# 10125623A00.net
KiCad netlist of a schematic drawn in EAGLE
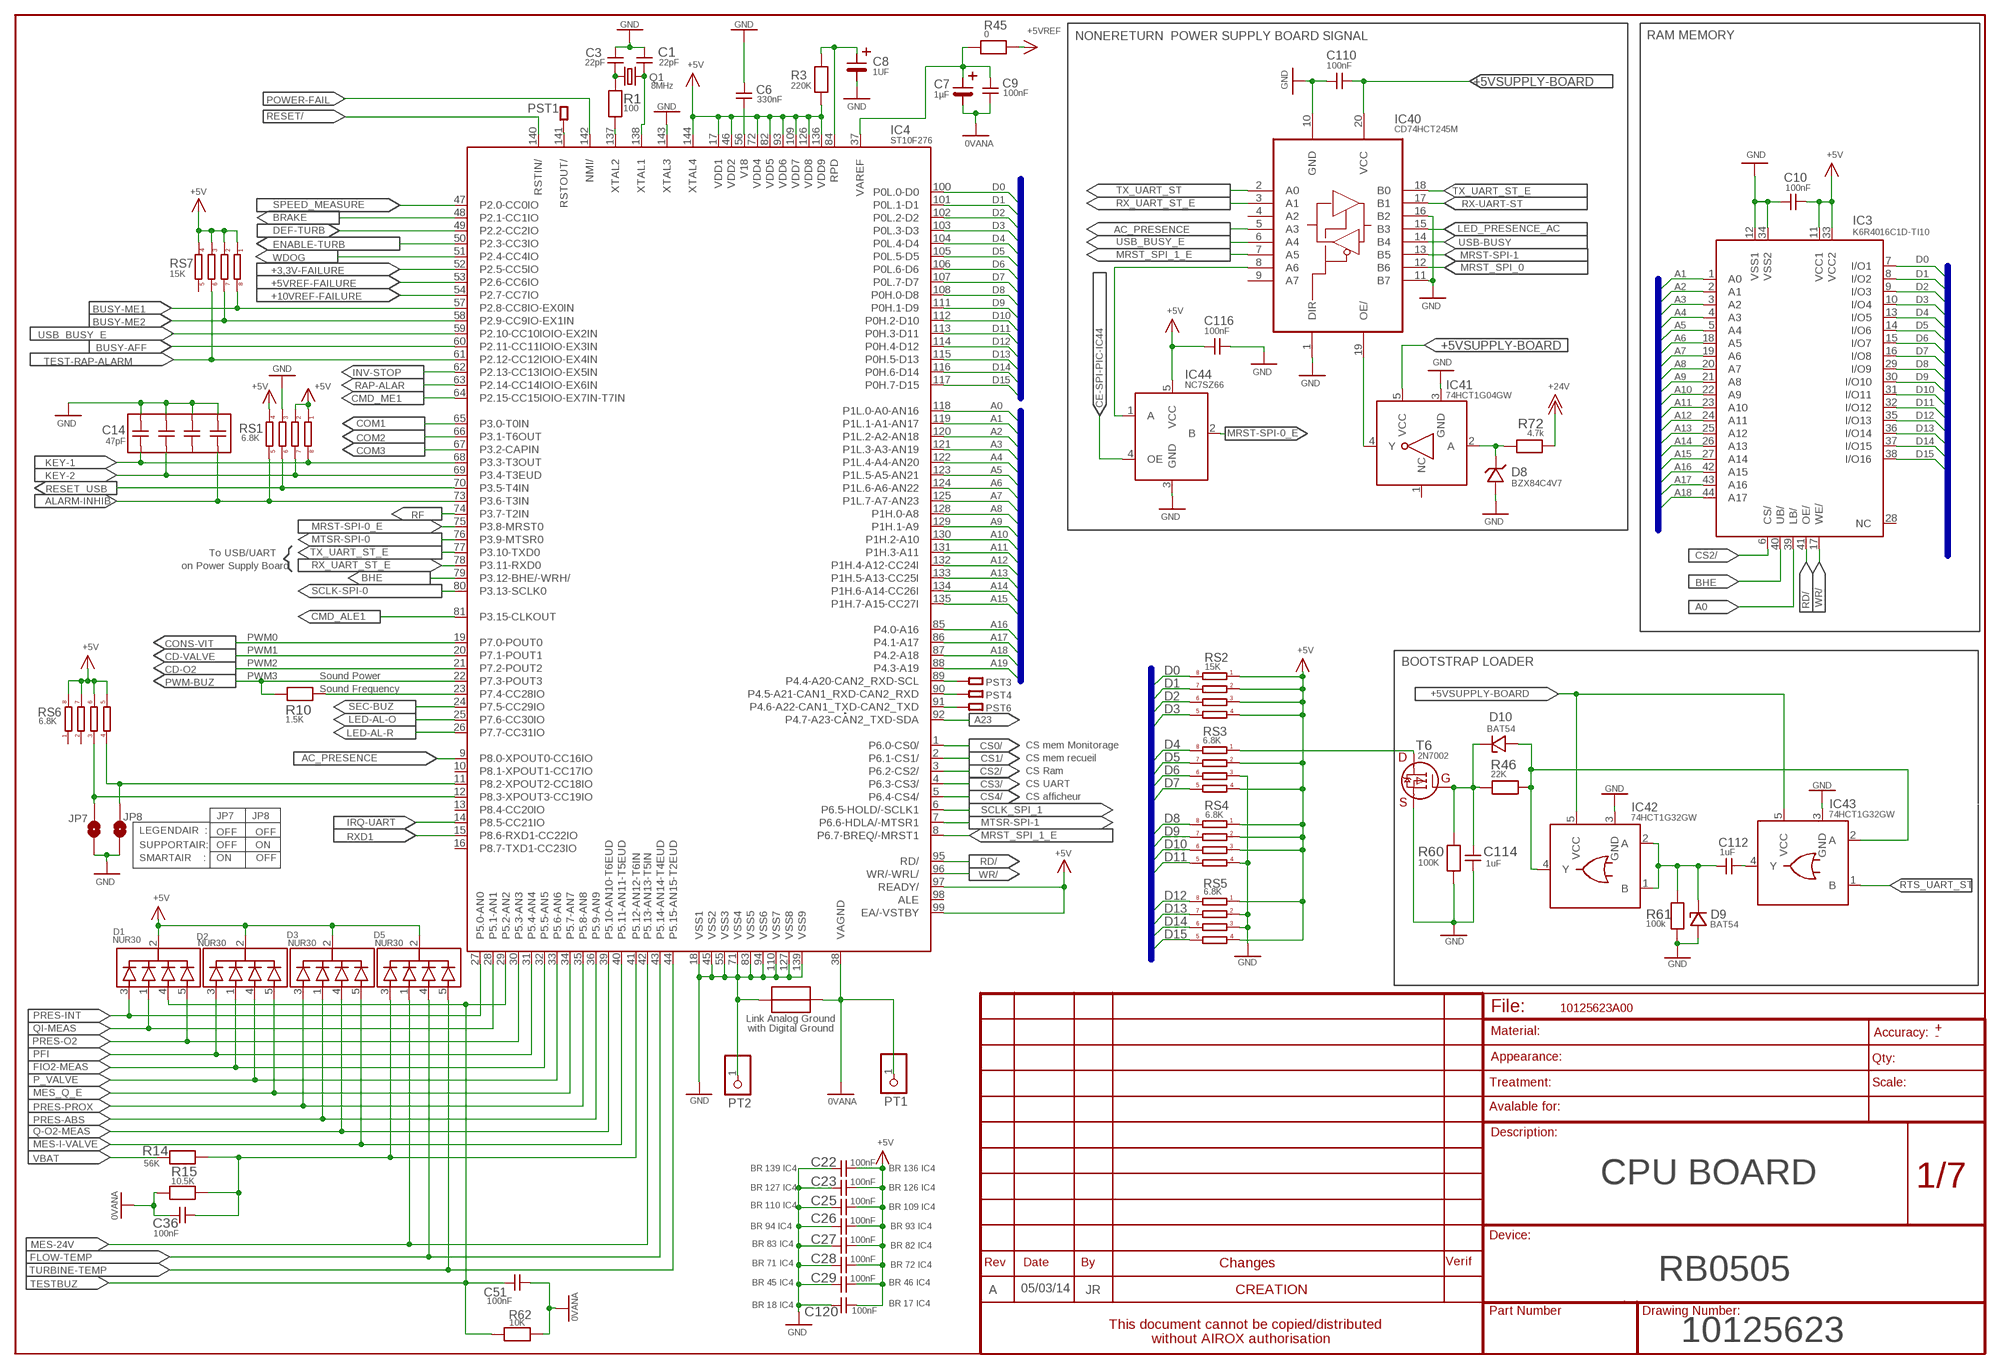
[diagram p0: schematic, sheet 1]
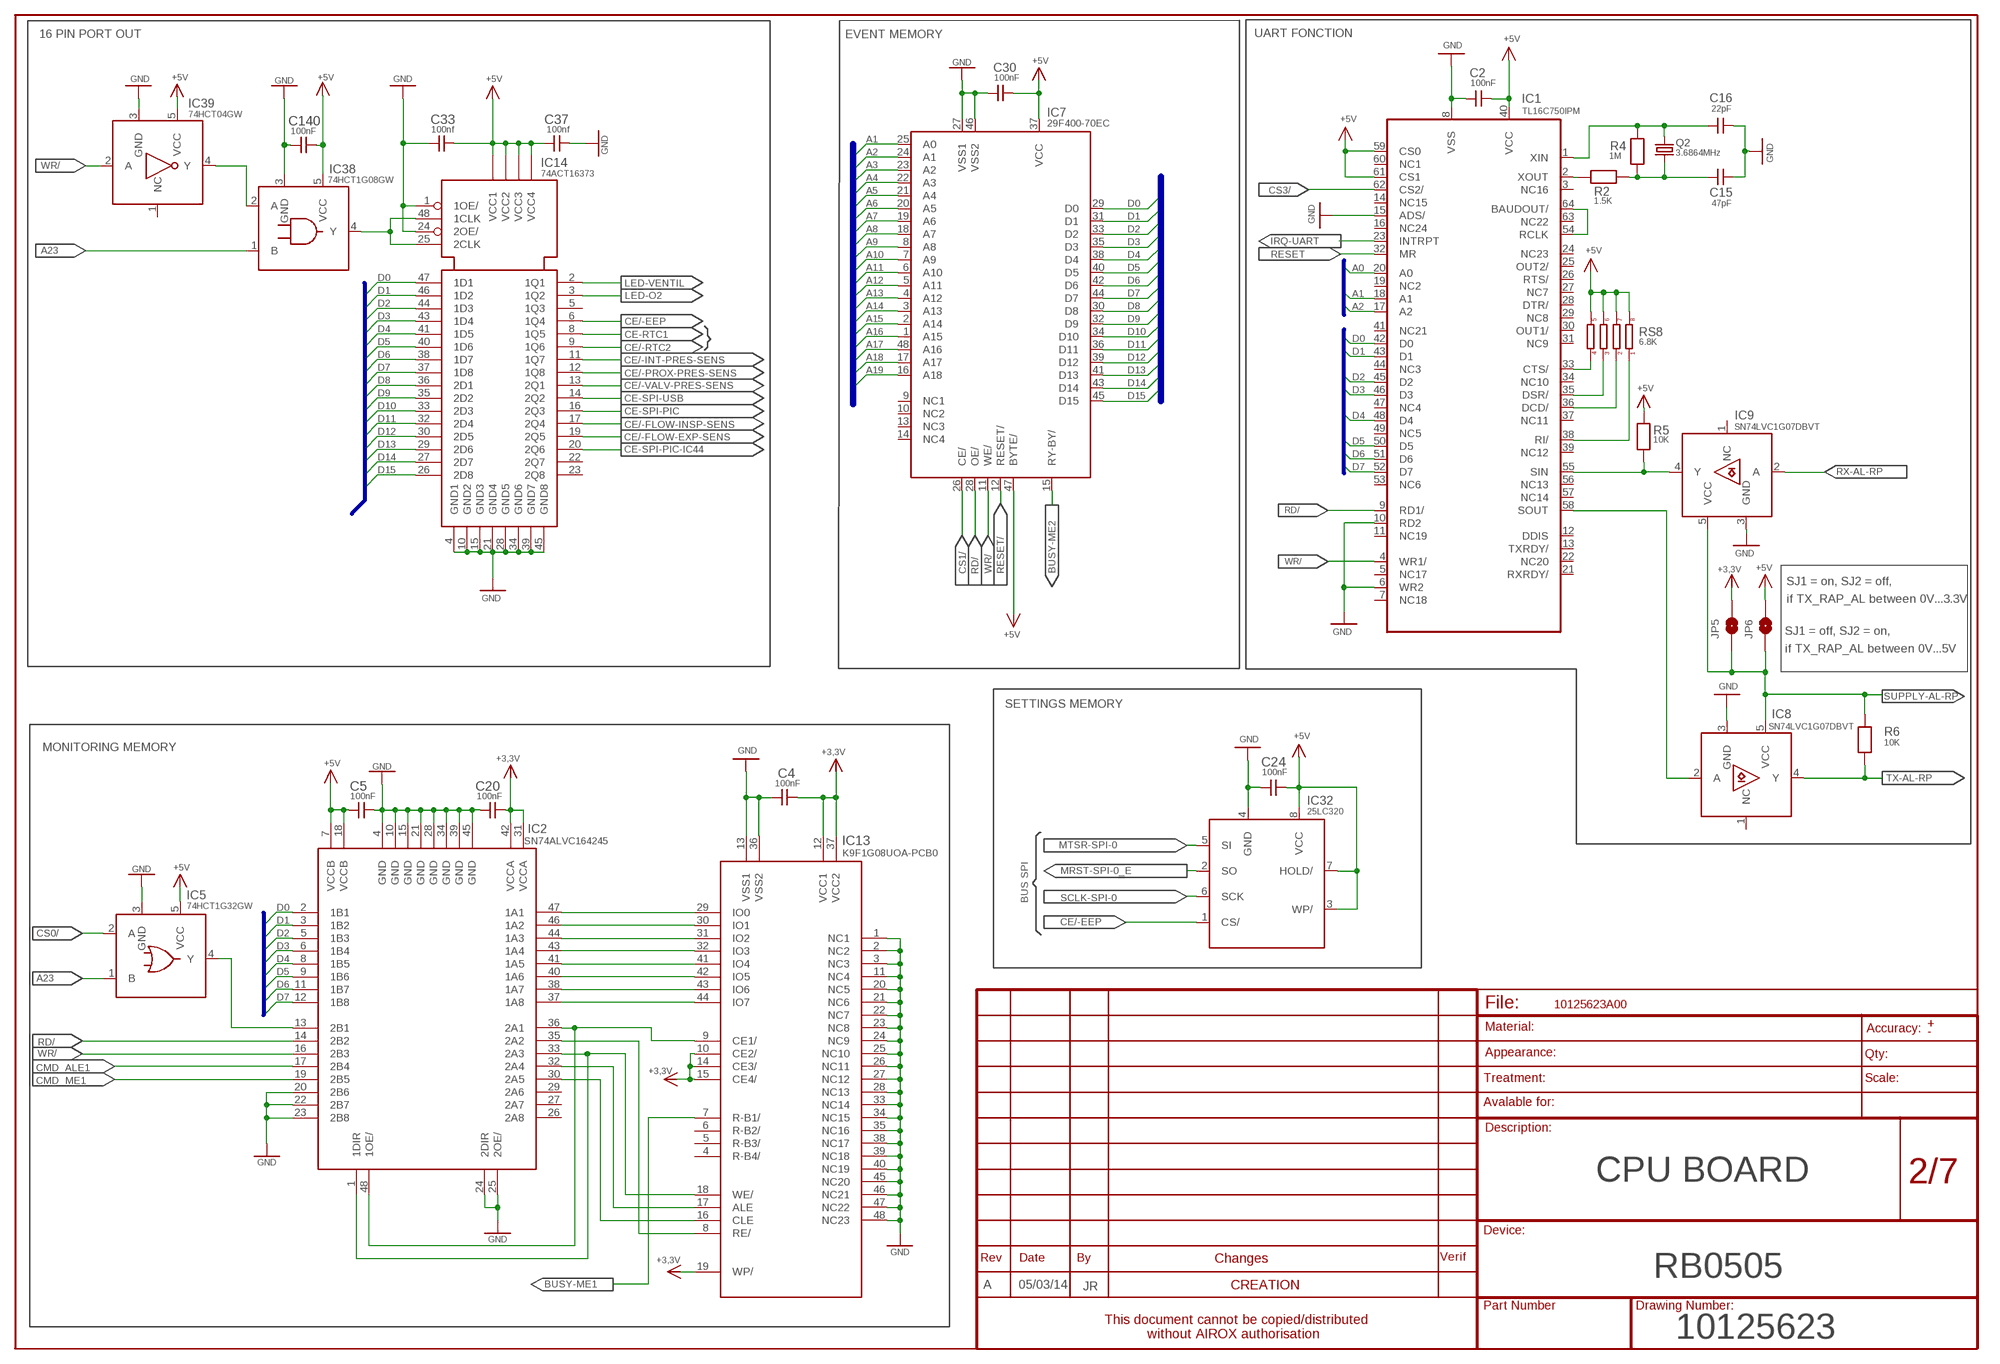
[diagram p1: schematic, sheet 2]
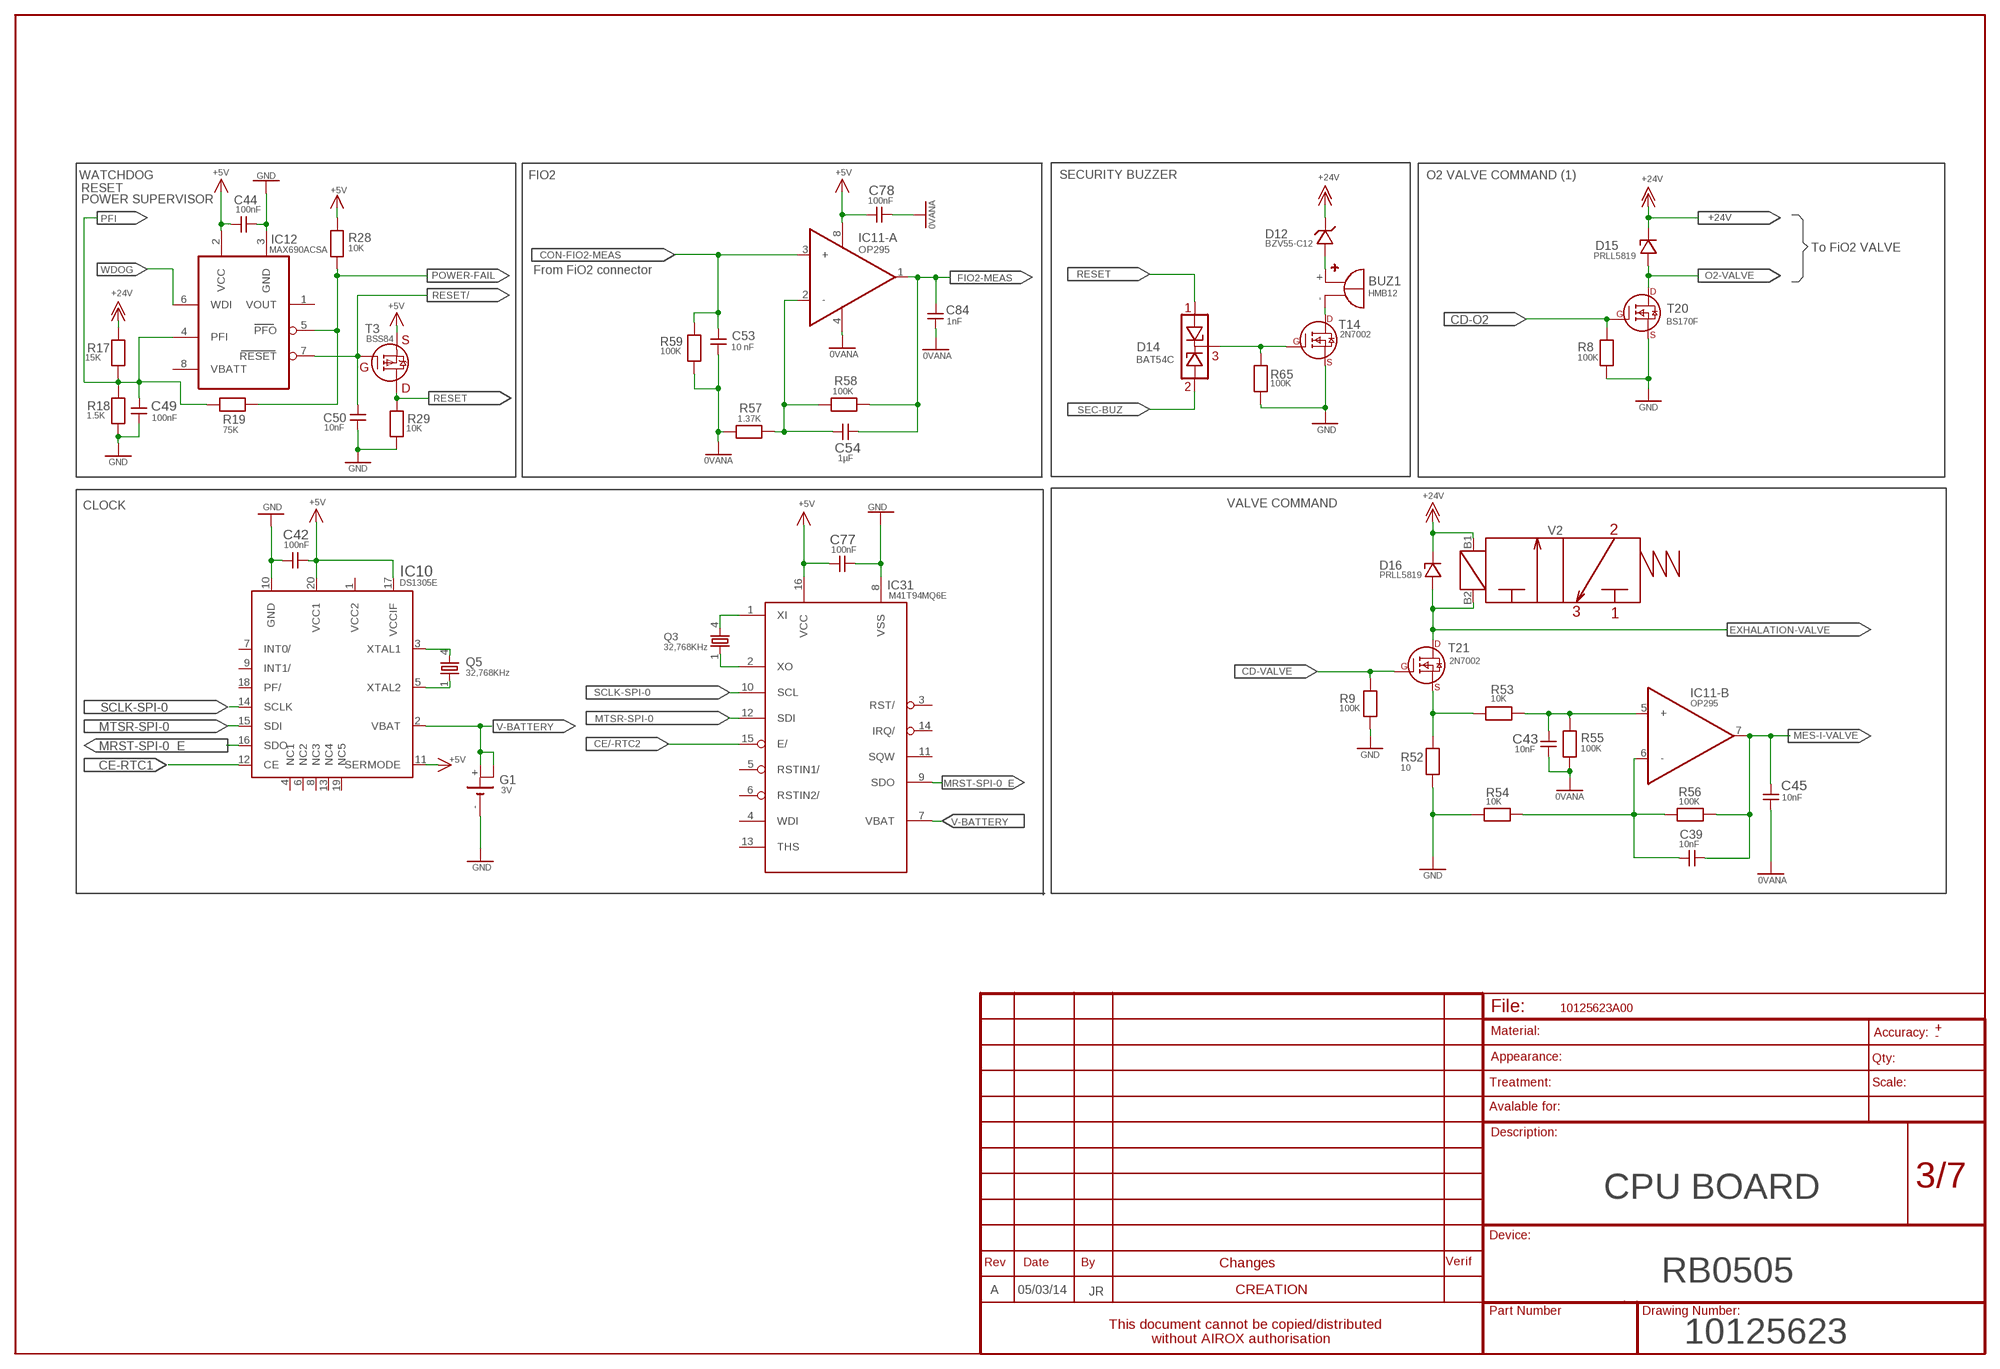
[diagram p2: schematic, sheet 3]
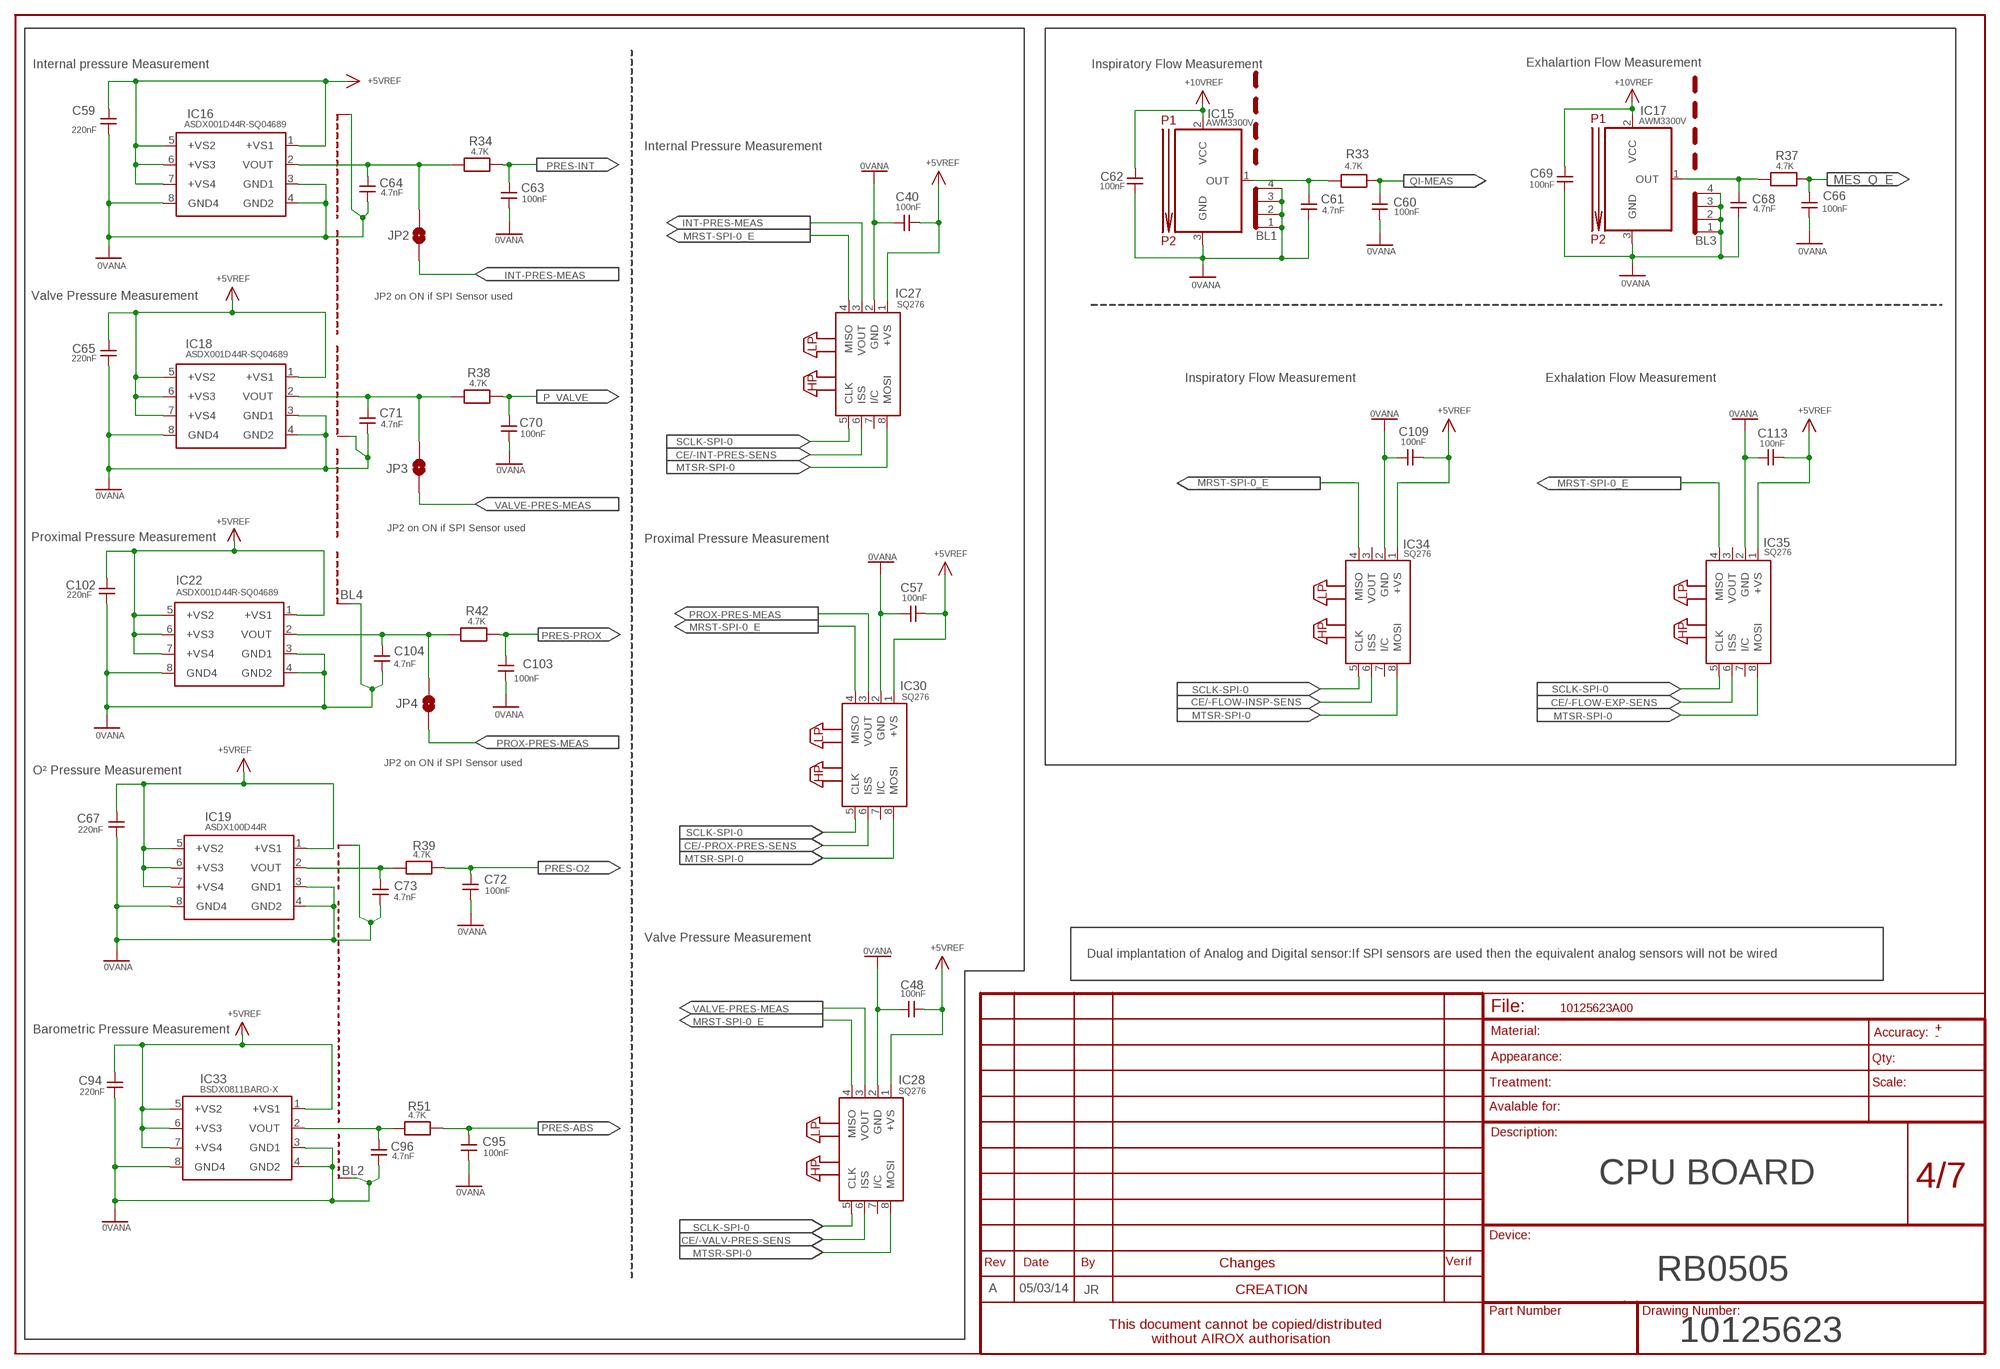
[diagram p3: schematic, sheet 4]
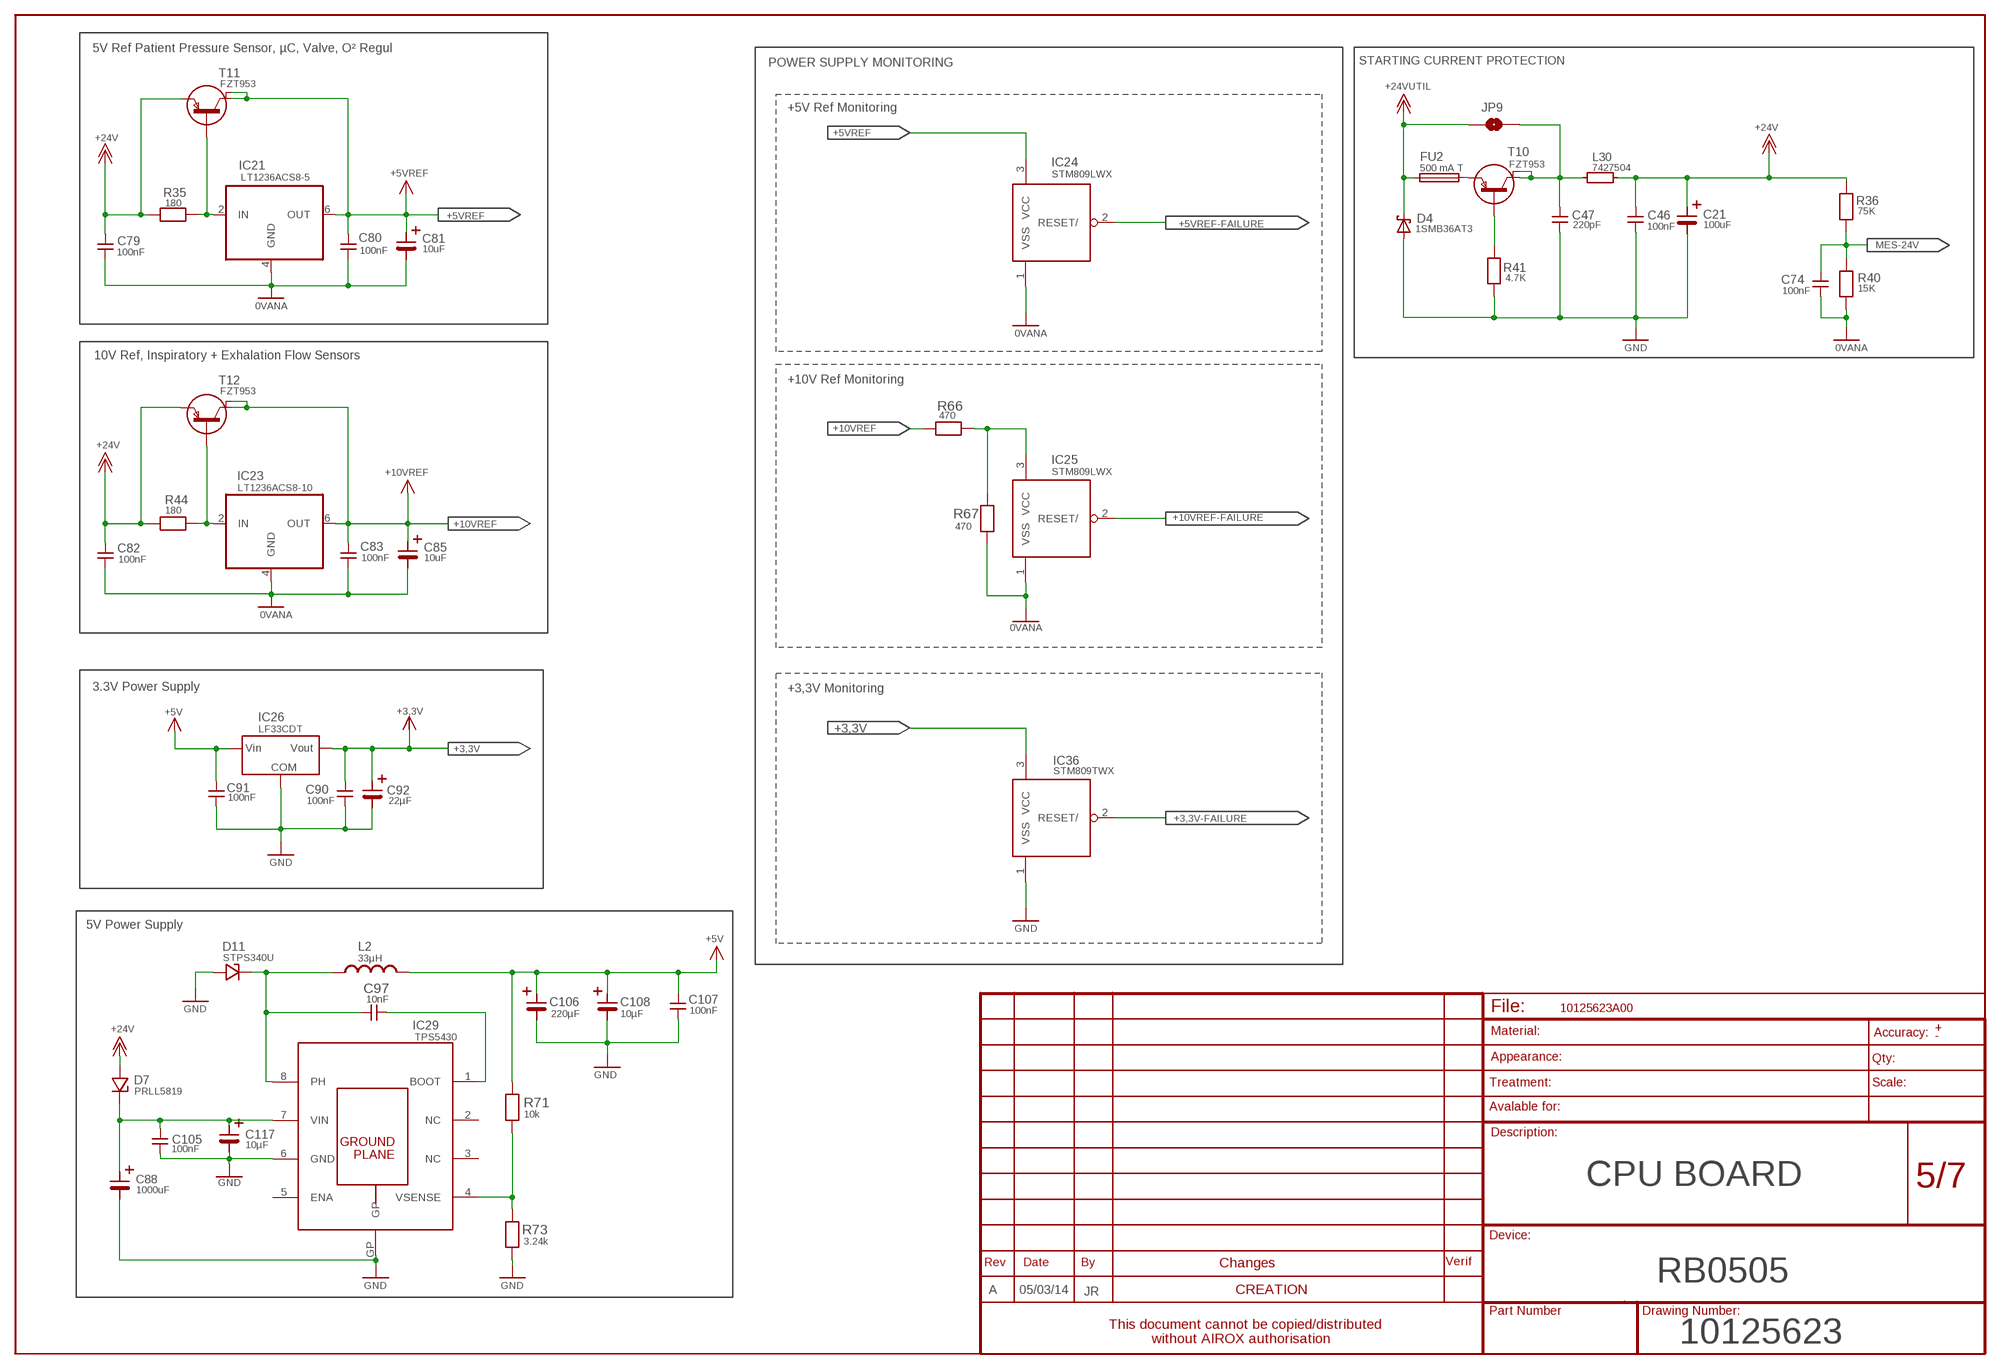
[diagram p4: schematic, sheet 5]
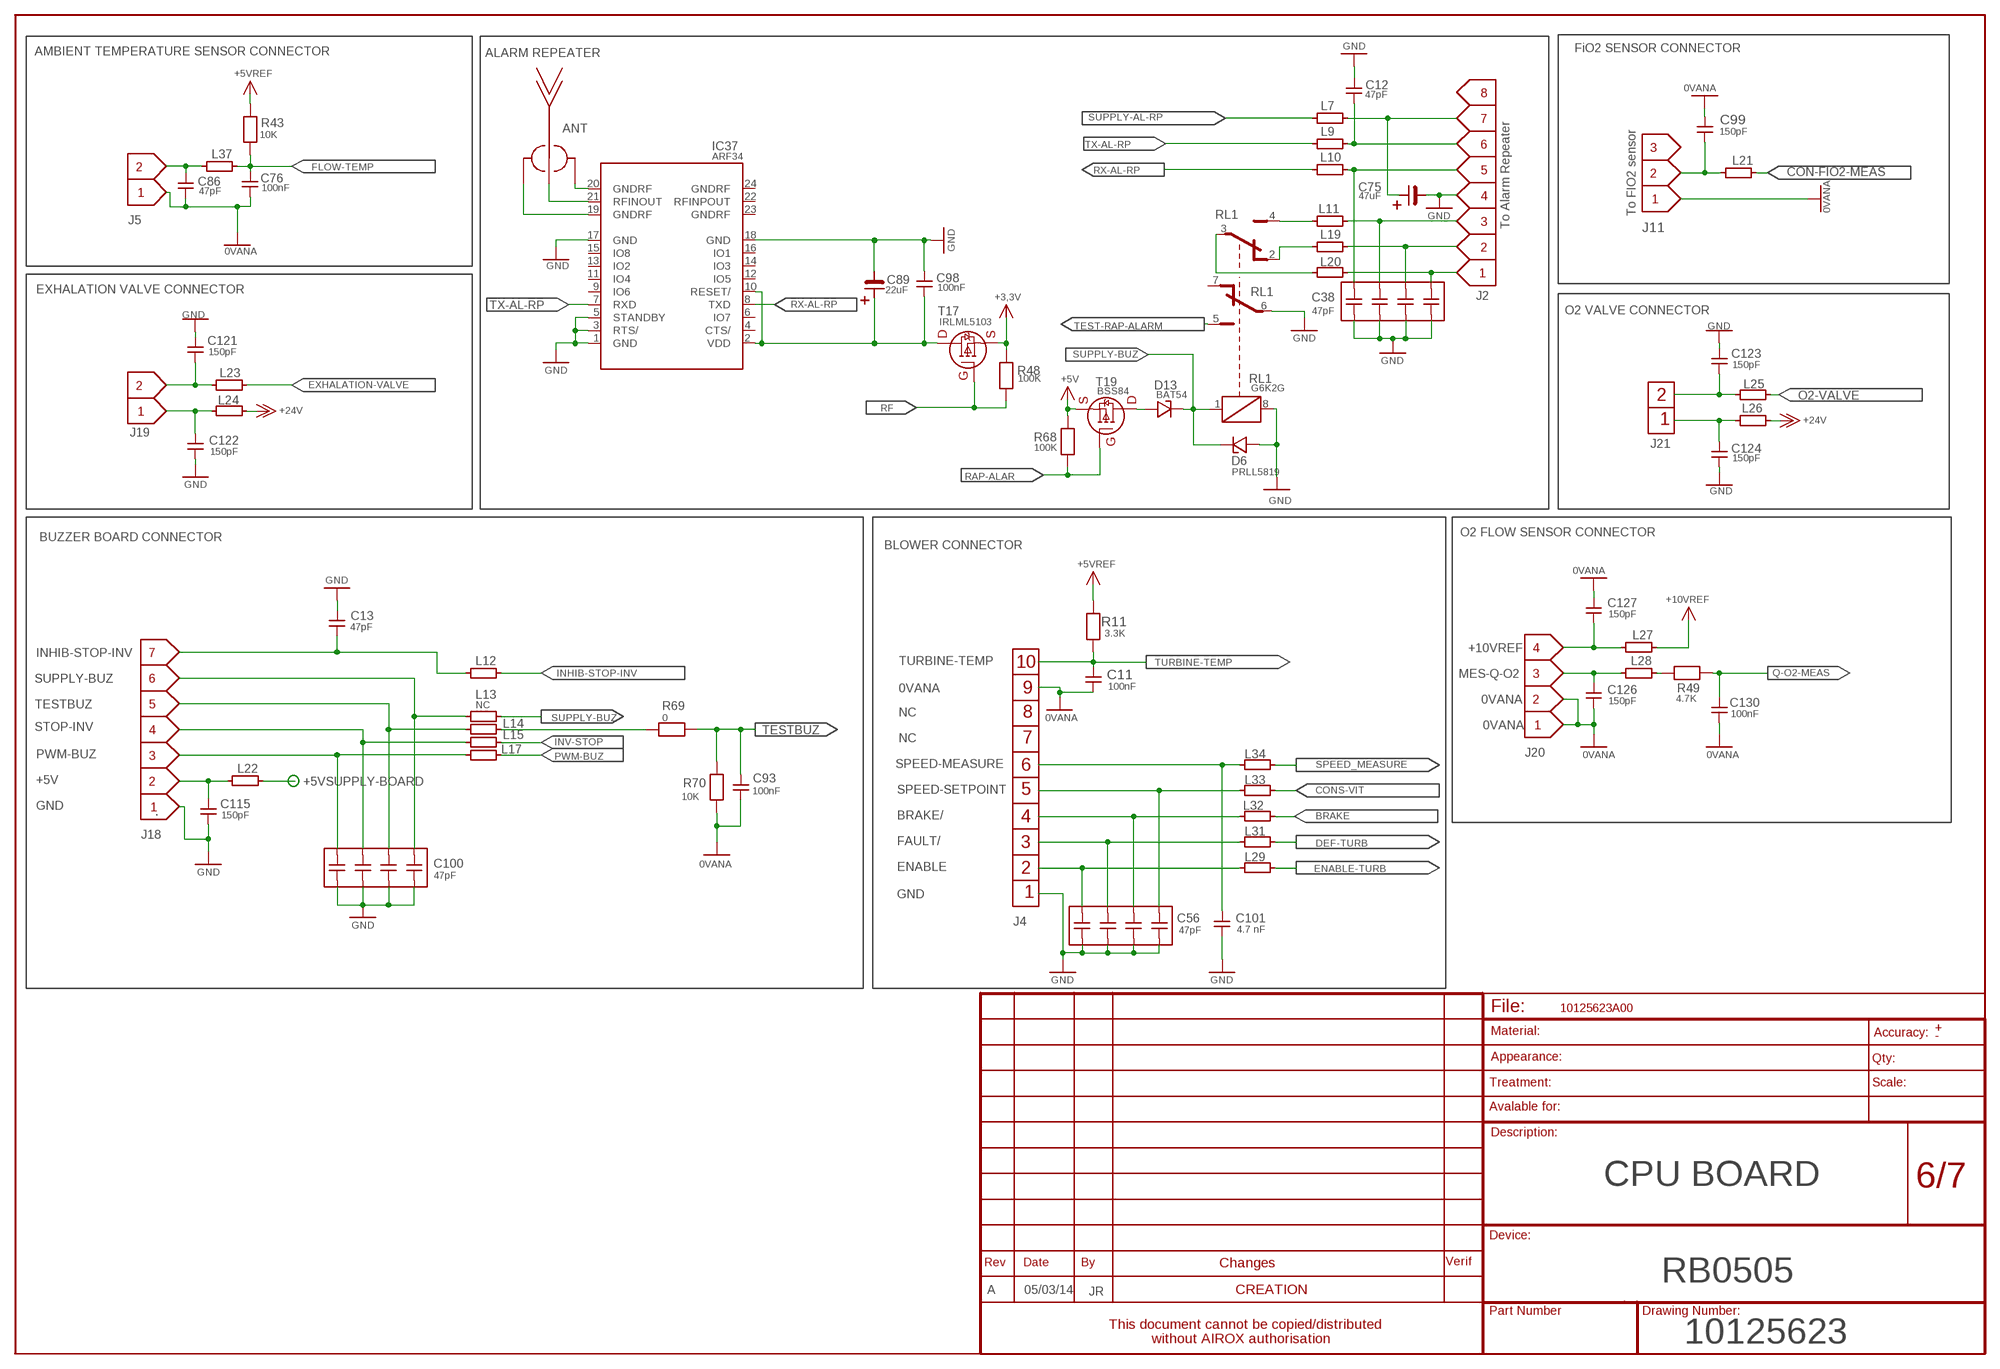
[diagram p5: schematic, sheet 6]
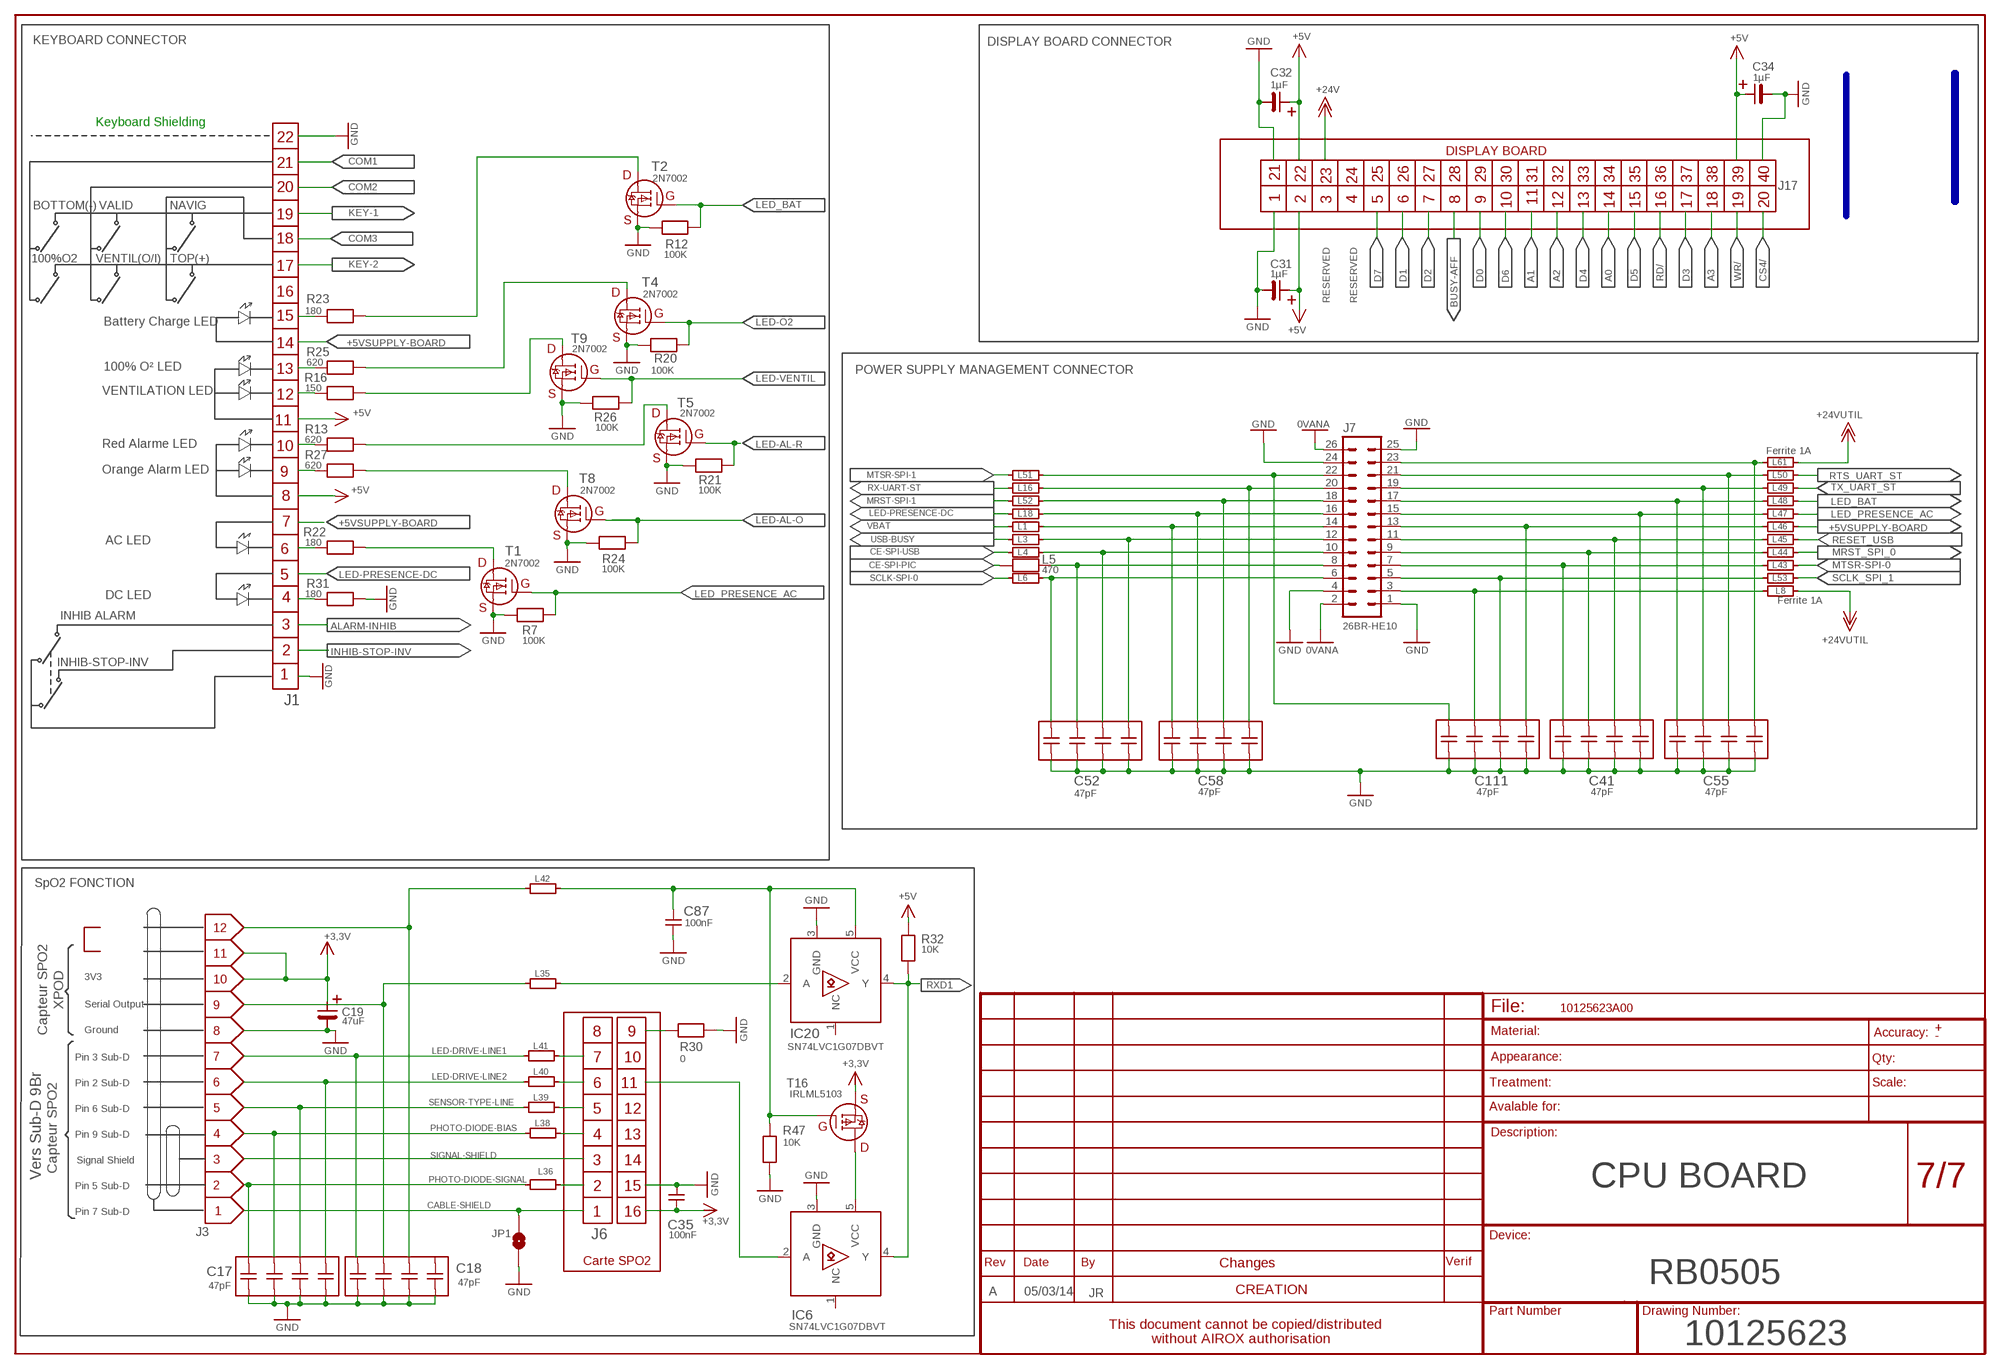
[diagram p6: schematic, sheet 7]

(export (version "E")
  (design (tool "Eeschema 10.0.6"))
  (components
    (comp (ref "C1")
      (value "22pF")
      (footprint "eagle-import:C0603")
      (libsource (lib "eagle-import") (part "CONDENSAT_CMS_C0603"))
    )
    (comp (ref "C3")
      (value "22pF")
      (footprint "eagle-import:C0603")
      (libsource (lib "eagle-import") (part "CONDENSAT_CMS_C0603"))
    )
    (comp (ref "C6")
      (value "330nF")
      (footprint "eagle-import:C0805")
      (libsource (lib "eagle-import") (part "CONDENSAT_CMS_C0805"))
    )
    (comp (ref "C7")
      (value "1µF")
      (footprint "eagle-import:TANTALB")
      (libsource (lib "eagle-import") (part "CONDENSAT_CMS_TANTALB"))
    )
    (comp (ref "C8")
      (value "1UF")
      (footprint "eagle-import:TANTALB")
      (libsource (lib "eagle-import") (part "CONDENSAT_CMS_TANTALB"))
    )
    (comp (ref "C9")
      (value "100nF")
      (footprint "eagle-import:C0805")
      (libsource (lib "eagle-import") (part "CONDENSAT_CMS_C0805"))
    )
    (comp (ref "C10")
      (value "100nF")
      (footprint "eagle-import:C0805")
      (libsource (lib "eagle-import") (part "C0805"))
    )
    (comp (ref "C14")
      (value "47pF")
      (footprint "eagle-import:RESEAU2")
      (libsource (lib "eagle-import") (part "RES_4CB"))
    )
    (comp (ref "C22")
      (value "100nF")
      (footprint "eagle-import:C0805")
      (libsource (lib "eagle-import") (part "C0805"))
    )
    (comp (ref "C23")
      (value "100nF")
      (footprint "eagle-import:C0805")
      (libsource (lib "eagle-import") (part "C0805"))
    )
    (comp (ref "C25")
      (value "100nF")
      (footprint "eagle-import:C0805")
      (libsource (lib "eagle-import") (part "C0805"))
    )
    (comp (ref "C26")
      (value "100nF")
      (footprint "eagle-import:C0805")
      (libsource (lib "eagle-import") (part "C0805"))
    )
    (comp (ref "C27")
      (value "100nF")
      (footprint "eagle-import:C0805")
      (libsource (lib "eagle-import") (part "C0805"))
    )
    (comp (ref "C28")
      (value "100nF")
      (footprint "eagle-import:C0805")
      (libsource (lib "eagle-import") (part "C0805"))
    )
    (comp (ref "C29")
      (value "100nF")
      (footprint "eagle-import:C0805")
      (libsource (lib "eagle-import") (part "C0805"))
    )
    (comp (ref "C36")
      (value "100nF")
      (footprint "eagle-import:C0805")
      (libsource (lib "eagle-import") (part "CONDENSAT_CMS_C0805"))
    )
    (comp (ref "C51")
      (value "100nF")
      (footprint "eagle-import:C0805")
      (libsource (lib "eagle-import") (part "CONDENSAT_CMS_C0805"))
    )
    (comp (ref "C110")
      (value "100nF")
      (footprint "eagle-import:C0805")
      (libsource (lib "eagle-import") (part "CONDENSAT_CMS_C0805"))
    )
    (comp (ref "C112")
      (value "1uF")
      (footprint "eagle-import:C0603")
      (libsource (lib "eagle-import") (part "CONDENSAT_CMS_C0603"))
    )
    (comp (ref "C114")
      (value "1uF")
      (footprint "eagle-import:C0603")
      (libsource (lib "eagle-import") (part "CONDENSAT_CMS_C0603"))
    )
    (comp (ref "C116")
      (value "100nF")
      (footprint "eagle-import:C0805")
      (libsource (lib "eagle-import") (part "CONDENSAT_CMS_C0805"))
    )
    (comp (ref "C120")
      (value "100nF")
      (footprint "eagle-import:C0805")
      (libsource (lib "eagle-import") (part "C0805"))
    )
    (comp (ref "D1")
      (value "NUR30")
      (footprint "eagle-import:5SOT23")
      (libsource (lib "eagle-import") (part "NUR30"))
    )
    (comp (ref "D2")
      (value "NUR30")
      (footprint "eagle-import:5SOT23")
      (libsource (lib "eagle-import") (part "NUR30"))
    )
    (comp (ref "D3")
      (value "NUR30")
      (footprint "eagle-import:5SOT23")
      (libsource (lib "eagle-import") (part "NUR30"))
    )
    (comp (ref "D5")
      (value "NUR30")
      (footprint "eagle-import:5SOT23")
      (libsource (lib "eagle-import") (part "NUR30"))
    )
    (comp (ref "D8")
      (value "BZX84C4V7")
      (footprint "eagle-import:SOT23DIO")
      (libsource (lib "eagle-import") (part "BZX84CXX"))
    )
    (comp (ref "D9")
      (value "BAT54")
      (footprint "eagle-import:SOT23DIO")
      (libsource (lib "eagle-import") (part "BAT54"))
    )
    (comp (ref "D10")
      (value "BAT54")
      (footprint "eagle-import:SOT23DIO")
      (libsource (lib "eagle-import") (part "BAT54"))
    )
    (comp (ref "IC3")
      (value "K6R4016C1D-TI10")
      (footprint "eagle-import:TSOPIIZ4")
      (libsource (lib "eagle-import") (part "K6R4016C1DTCT000(256KX16)"))
    )
    (comp (ref "IC4")
      (value "ST10F276")
      (footprint "eagle-import:TQFP144")
      (libsource (lib "eagle-import") (part "ST10F269-273-276"))
    )
    (comp (ref "IC40")
      (value "CD74HCT245M")
      (footprint "eagle-import:SO20")
      (libsource (lib "eagle-import") (part "CD74HCT245M"))
    )
    (comp (ref "IC41")
      (value "74HCT1G04GW")
      (footprint "eagle-import:SOT23-5")
      (libsource (lib "eagle-import") (part "74HCT1G04GW"))
    )
    (comp (ref "IC42")
      (value "74HCT1G32GW")
      (footprint "eagle-import:SOT23-5")
      (libsource (lib "eagle-import") (part "74HCT1G32GW"))
    )
    (comp (ref "IC43")
      (value "74HCT1G32GW")
      (footprint "eagle-import:SOT23-5")
      (libsource (lib "eagle-import") (part "74HCT1G32GW"))
    )
    (comp (ref "IC44")
      (value "NC7SZ66")
      (footprint "eagle-import:SOT23-5")
      (libsource (lib "eagle-import") (part "NC7SZ66"))
    )
    (comp (ref "JP7")
      (value "JUMP_0U")
      (footprint "eagle-import:0805")
      (libsource (lib "eagle-import") (part "JUMP_0U"))
    )
    (comp (ref "JP8")
      (value "JUMP_0U")
      (footprint "eagle-import:0805")
      (libsource (lib "eagle-import") (part "JUMP_0U"))
    )
    (comp (ref "JPL1")
      (value "LIAISON_MASSES")
      (footprint "eagle-import:LIAISONS_MASSES")
      (libsource (lib "eagle-import") (part "LIAISON_MASSES"))
    )
    (comp (ref "PST1")
      (value "PAST01")
      (footprint "eagle-import:1X01")
      (libsource (lib "eagle-import") (part "PAST01"))
    )
    (comp (ref "PST3")
      (value "PAST01")
      (footprint "eagle-import:1X01")
      (libsource (lib "eagle-import") (part "PAST01"))
    )
    (comp (ref "PST4")
      (value "PAST01")
      (footprint "eagle-import:1X01")
      (libsource (lib "eagle-import") (part "PAST01"))
    )
    (comp (ref "PST6")
      (value "PAST01")
      (footprint "eagle-import:1X01")
      (libsource (lib "eagle-import") (part "PAST01"))
    )
    (comp (ref "PT1")
      (value "PINHD-1X1")
      (footprint "eagle-import:1X01")
      (libsource (lib "eagle-import") (part "PINHD-1X1"))
    )
    (comp (ref "PT2")
      (value "PINHD-1X1")
      (footprint "eagle-import:1X01")
      (libsource (lib "eagle-import") (part "PINHD-1X1"))
    )
    (comp (ref "Q1")
      (value "8MHz")
      (footprint "eagle-import:SM49")
      (libsource (lib "eagle-import") (part "SM49"))
    )
    (comp (ref "R1")
      (value "100")
      (footprint "eagle-import:R0805")
      (libsource (lib "eagle-import") (part "RESIST_CMS_R0805"))
    )
    (comp (ref "R3")
      (value "220K")
      (footprint "eagle-import:R0805")
      (libsource (lib "eagle-import") (part "RESIST_CMS_R0805"))
    )
    (comp (ref "R10")
      (value "1.5K")
      (footprint "eagle-import:R0805")
      (libsource (lib "eagle-import") (part "RESIST_CMS_R0805"))
    )
    (comp (ref "R14")
      (value "56K")
      (footprint "eagle-import:R0805")
      (libsource (lib "eagle-import") (part "RESIST_CMS_R0805"))
    )
    (comp (ref "R15")
      (value "10.5K")
      (footprint "eagle-import:R0805")
      (libsource (lib "eagle-import") (part "RESIST_CMS_R0805"))
    )
    (comp (ref "R45")
      (value "0")
      (footprint "eagle-import:R0805")
      (libsource (lib "eagle-import") (part "RESIST_CMS_R0805"))
    )
    (comp (ref "R46")
      (value "22K")
      (footprint "eagle-import:R0805")
      (libsource (lib "eagle-import") (part "RESIST_CMS_R0805"))
    )
    (comp (ref "R60")
      (value "100K")
      (footprint "eagle-import:R0805")
      (libsource (lib "eagle-import") (part "RESIST_CMS_R0805"))
    )
    (comp (ref "R61")
      (value "100k")
      (footprint "eagle-import:R0805")
      (libsource (lib "eagle-import") (part "RESIST_CMS_R0805"))
    )
    (comp (ref "R62")
      (value "10K")
      (footprint "eagle-import:R0805")
      (libsource (lib "eagle-import") (part "RESIST_CMS_R0805"))
    )
    (comp (ref "R72")
      (value "4.7k")
      (footprint "eagle-import:R0805")
      (libsource (lib "eagle-import") (part "RESIST_CMS_R0805"))
    )
    (comp (ref "RS1")
      (value "6.8K")
      (footprint "eagle-import:BCN16_4_")
      (libsource (lib "eagle-import") (part "RESIST_CMS_RES_4R_BCN"))
    )
    (comp (ref "RS2")
      (value "15K")
      (footprint "eagle-import:BCN16_4_")
      (libsource (lib "eagle-import") (part "RES_4R_BCN"))
    )
    (comp (ref "RS3")
      (value "6.8K")
      (footprint "eagle-import:BCN16_4_")
      (libsource (lib "eagle-import") (part "RES_4R_BCN"))
    )
    (comp (ref "RS4")
      (value "6.8K")
      (footprint "eagle-import:BCN16_4_")
      (libsource (lib "eagle-import") (part "RES_4R_BCN"))
    )
    (comp (ref "RS5")
      (value "6.8K")
      (footprint "eagle-import:BCN16_4_")
      (libsource (lib "eagle-import") (part "RES_4R_BCN"))
    )
    (comp (ref "RS6")
      (value "6.8K")
      (footprint "eagle-import:BCN16_4_")
      (libsource (lib "eagle-import") (part "RESIST_CMS_RES_4R_BCN"))
    )
    (comp (ref "RS7")
      (value "15K")
      (footprint "eagle-import:BCN16_4_")
      (libsource (lib "eagle-import") (part "RESIST_CMS_RES_4R_BCN"))
    )
    (comp (ref "T6")
      (value "2N7002")
      (footprint "eagle-import:SOT23MOS")
      (libsource (lib "eagle-import") (part "2N7002"))
    )
    (comp (ref "C17")
      (value "47pF")
      (footprint "eagle-import:RESEAU_1")
      (libsource (lib "eagle-import") (part "RESEAU_4C"))
    )
    (comp (ref "C18")
      (value "47pF")
      (footprint "eagle-import:RESEAU_1")
      (libsource (lib "eagle-import") (part "RESEAU_4C"))
    )
    (comp (ref "C19")
      (value "47uF")
      (footprint "eagle-import:TANTALB")
      (libsource (lib "eagle-import") (part "CONDENSAT_CMS_TANTALB"))
    )
    (comp (ref "C31")
      (value "1µF")
      (footprint "eagle-import:TANTALB")
      (libsource (lib "eagle-import") (part "TANTALB"))
    )
    (comp (ref "C32")
      (value "1µF")
      (footprint "eagle-import:TANTALB")
      (libsource (lib "eagle-import") (part "TANTALB"))
    )
    (comp (ref "C34")
      (value "1µF")
      (footprint "eagle-import:TANTALB")
      (libsource (lib "eagle-import") (part "TANTALB"))
    )
    (comp (ref "C35")
      (value "100nF")
      (footprint "eagle-import:C0805")
      (libsource (lib "eagle-import") (part "CONDENSAT_CMS_C0805"))
    )
    (comp (ref "C41")
      (value "47pF")
      (footprint "eagle-import:RESEAU_1")
      (libsource (lib "eagle-import") (part "RESEAU_4C"))
    )
    (comp (ref "C52")
      (value "47pF")
      (footprint "eagle-import:RESEAU_1")
      (libsource (lib "eagle-import") (part "RESEAU_4C"))
    )
    (comp (ref "C55")
      (value "47pF")
      (footprint "eagle-import:RESEAU_1")
      (libsource (lib "eagle-import") (part "RESEAU_4C"))
    )
    (comp (ref "C58")
      (value "47pF")
      (footprint "eagle-import:RESEAU_1")
      (libsource (lib "eagle-import") (part "RESEAU_4C"))
    )
    (comp (ref "C87")
      (value "100nF")
      (footprint "eagle-import:C0603")
      (libsource (lib "eagle-import") (part "CONDENSAT_CMS_C0603"))
    )
    (comp (ref "C111")
      (value "47pF")
      (footprint "eagle-import:RESEAU_1")
      (libsource (lib "eagle-import") (part "RESEAU_4C"))
    )
    (comp (ref "IC6")
      (value "SN74LVC1G07DBVT")
      (footprint "eagle-import:SOT753_DBV")
      (libsource (lib "eagle-import") (part "LVC1G07DBVT"))
    )
    (comp (ref "IC20")
      (value "SN74LVC1G07DBVT")
      (footprint "eagle-import:SOT753_DBV")
      (libsource (lib "eagle-import") (part "LVC1G07DBVT"))
    )
    (comp (ref "J1")
      (value "ZIF-52610-2290")
      (footprint "eagle-import:ZIF-52610-2290")
      (libsource (lib "eagle-import") (part "ZIF-52610-2290"))
    )
    (comp (ref "J3")
      (value "B12B-ZR")
      (footprint "eagle-import:12BR")
      (libsource (lib "eagle-import") (part "B12B-ZR"))
    )
    (comp (ref "J6")
      (value "87606-408")
      (footprint "eagle-import:2X16BR")
      (libsource (lib "eagle-import") (part "87606-408"))
    )
    (comp (ref "J7")
      (value "26BR-HE10")
      (footprint "eagle-import:26BR-HE10")
      (libsource (lib "eagle-import") (part "26BR-HE10"))
    )
    (comp (ref "J17")
      (value "FH_40BR")
      (footprint "eagle-import:FH_SERIE")
      (libsource (lib "eagle-import") (part "FH_40BR"))
    )
    (comp (ref "JP1")
      (value "JUMP_0U")
      (footprint "eagle-import:0805")
      (libsource (lib "eagle-import") (part "JUMP_0U"))
    )
    (comp (ref "L1")
      (value "Ferrite 200mA")
      (footprint "eagle-import:0603")
      (libsource (lib "eagle-import") (part "74279263"))
    )
    (comp (ref "L3")
      (value "Ferrite 200mA")
      (footprint "eagle-import:0603")
      (libsource (lib "eagle-import") (part "74279263"))
    )
    (comp (ref "L4")
      (value "Ferrite 200mA")
      (footprint "eagle-import:0603")
      (libsource (lib "eagle-import") (part "74279263"))
    )
    (comp (ref "L5")
      (value "470")
      (footprint "eagle-import:R0805")
      (libsource (lib "eagle-import") (part "RESIST_CMS_R0805"))
    )
    (comp (ref "L6")
      (value "Ferrite 200mA")
      (footprint "eagle-import:0603")
      (libsource (lib "eagle-import") (part "74279263"))
    )
    (comp (ref "L8")
      (value "Ferrite 1A")
      (footprint "eagle-import:PERL-FER")
      (libsource (lib "eagle-import") (part "7427504"))
    )
    (comp (ref "L16")
      (value "Ferrite 200mA")
      (footprint "eagle-import:0603")
      (libsource (lib "eagle-import") (part "74279263"))
    )
    (comp (ref "L18")
      (value "Ferrite 200mA")
      (footprint "eagle-import:0603")
      (libsource (lib "eagle-import") (part "74279263"))
    )
    (comp (ref "L35")
      (value "Ferrite 200mA")
      (footprint "eagle-import:0603")
      (libsource (lib "eagle-import") (part "74279263"))
    )
    (comp (ref "L36")
      (value "Ferrite 200mA")
      (footprint "eagle-import:0603")
      (libsource (lib "eagle-import") (part "74279263"))
    )
    (comp (ref "L38")
      (value "Ferrite 200mA")
      (footprint "eagle-import:0603")
      (libsource (lib "eagle-import") (part "74279263"))
    )
    (comp (ref "L39")
      (value "Ferrite 200mA")
      (footprint "eagle-import:0603")
      (libsource (lib "eagle-import") (part "74279263"))
    )
    (comp (ref "L40")
      (value "Ferrite 200mA")
      (footprint "eagle-import:0603")
      (libsource (lib "eagle-import") (part "74279263"))
    )
    (comp (ref "L41")
      (value "Ferrite 200mA")
      (footprint "eagle-import:0603")
      (libsource (lib "eagle-import") (part "74279263"))
    )
    (comp (ref "L42")
      (value "Ferrite 200mA")
      (footprint "eagle-import:0603")
      (libsource (lib "eagle-import") (part "74279263"))
    )
    (comp (ref "L43")
      (value "Ferrite 200mA")
      (footprint "eagle-import:0603")
      (libsource (lib "eagle-import") (part "74279263"))
    )
    (comp (ref "L44")
      (value "Ferrite 200mA")
      (footprint "eagle-import:0603")
      (libsource (lib "eagle-import") (part "74279263"))
    )
    (comp (ref "L45")
      (value "Ferrite 200mA")
      (footprint "eagle-import:0603")
      (libsource (lib "eagle-import") (part "74279263"))
    )
    (comp (ref "L46")
      (value "Ferrite 200mA")
      (footprint "eagle-import:0603")
      (libsource (lib "eagle-import") (part "74279263"))
    )
    (comp (ref "L47")
      (value "Ferrite 200mA")
      (footprint "eagle-import:0603")
      (libsource (lib "eagle-import") (part "74279263"))
    )
    (comp (ref "L48")
      (value "Ferrite 200mA")
      (footprint "eagle-import:0603")
      (libsource (lib "eagle-import") (part "74279263"))
    )
    (comp (ref "L49")
      (value "Ferrite 200mA")
      (footprint "eagle-import:0603")
      (libsource (lib "eagle-import") (part "74279263"))
    )
    (comp (ref "L50")
      (value "Ferrite 200mA")
      (footprint "eagle-import:0603")
      (libsource (lib "eagle-import") (part "74279263"))
    )
    (comp (ref "L51")
      (value "Ferrite 200mA")
      (footprint "eagle-import:0603")
      (libsource (lib "eagle-import") (part "74279263"))
    )
    (comp (ref "L52")
      (value "Ferrite 200mA")
      (footprint "eagle-import:0603")
      (libsource (lib "eagle-import") (part "74279263"))
    )
    (comp (ref "L53")
      (value "Ferrite 200mA")
      (footprint "eagle-import:0603")
      (libsource (lib "eagle-import") (part "74279263"))
    )
    (comp (ref "L61")
      (value "Ferrite 1A")
      (footprint "eagle-import:PERL-FER")
      (libsource (lib "eagle-import") (part "7427504"))
    )
    (comp (ref "R7")
      (value "100K")
      (footprint "eagle-import:R0805")
      (libsource (lib "eagle-import") (part "R0805"))
    )
    (comp (ref "R12")
      (value "100K")
      (footprint "eagle-import:R0805")
      (libsource (lib "eagle-import") (part "R0805"))
    )
    (comp (ref "R13")
      (value "620")
      (footprint "eagle-import:R0805")
      (libsource (lib "eagle-import") (part "R0805"))
    )
    (comp (ref "R16")
      (value "150")
      (footprint "eagle-import:R1206")
      (libsource (lib "eagle-import") (part "R1206"))
    )
    (comp (ref "R20")
      (value "100K")
      (footprint "eagle-import:R0805")
      (libsource (lib "eagle-import") (part "R0805"))
    )
    (comp (ref "R21")
      (value "100K")
      (footprint "eagle-import:R0805")
      (libsource (lib "eagle-import") (part "R0805"))
    )
    (comp (ref "R22")
      (value "180")
      (footprint "eagle-import:R1206")
      (libsource (lib "eagle-import") (part "R1206"))
    )
    (comp (ref "R23")
      (value "180")
      (footprint "eagle-import:R1206")
      (libsource (lib "eagle-import") (part "R1206"))
    )
    (comp (ref "R24")
      (value "100K")
      (footprint "eagle-import:R0805")
      (libsource (lib "eagle-import") (part "R0805"))
    )
    (comp (ref "R25")
      (value "620")
      (footprint "eagle-import:R0805")
      (libsource (lib "eagle-import") (part "R0805"))
    )
    (comp (ref "R26")
      (value "100K")
      (footprint "eagle-import:R0805")
      (libsource (lib "eagle-import") (part "R0805"))
    )
    (comp (ref "R27")
      (value "620")
      (footprint "eagle-import:R0805")
      (libsource (lib "eagle-import") (part "R0805"))
    )
    (comp (ref "R30")
      (value "0")
      (footprint "eagle-import:R0805")
      (libsource (lib "eagle-import") (part "RESIST_CMS_R0805"))
    )
    (comp (ref "R31")
      (value "180")
      (footprint "eagle-import:R1206")
      (libsource (lib "eagle-import") (part "R1206"))
    )
    (comp (ref "R32")
      (value "10K")
      (footprint "eagle-import:R0805")
      (libsource (lib "eagle-import") (part "R0805"))
    )
    (comp (ref "R47")
      (value "10K")
      (footprint "eagle-import:R0805")
      (libsource (lib "eagle-import") (part "R0805"))
    )
    (comp (ref "T1")
      (value "2N7002")
      (footprint "eagle-import:SOT23MOS")
      (libsource (lib "eagle-import") (part "IRLML2803"))
    )
    (comp (ref "T2")
      (value "2N7002")
      (footprint "eagle-import:SOT23MOS")
      (libsource (lib "eagle-import") (part "IRLML2803"))
    )
    (comp (ref "T4")
      (value "2N7002")
      (footprint "eagle-import:SOT23MOS")
      (libsource (lib "eagle-import") (part "IRLML2803"))
    )
    (comp (ref "T5")
      (value "2N7002")
      (footprint "eagle-import:SOT23MOS")
      (libsource (lib "eagle-import") (part "IRLML2803"))
    )
    (comp (ref "T8")
      (value "2N7002")
      (footprint "eagle-import:SOT23MOS")
      (libsource (lib "eagle-import") (part "IRLML2803@2"))
    )
    (comp (ref "T9")
      (value "2N7002")
      (footprint "eagle-import:SOT23MOS")
      (libsource (lib "eagle-import") (part "IRLML2803@2"))
    )
    (comp (ref "T16")
      (value "IRLML5103")
      (footprint "eagle-import:SOT23MOS")
      (libsource (lib "eagle-import") (part "IRLML5103"))
    )
    (comp (ref "BUZ1")
      (value "HMB12")
      (footprint "eagle-import:F_HMB")
      (libsource (lib "eagle-import") (part "F/HMB"))
    )
    (comp (ref "C39")
      (value "10nF")
      (footprint "eagle-import:C0805")
      (libsource (lib "eagle-import") (part "CONDENSAT_CMS_C0805"))
    )
    (comp (ref "C42")
      (value "100nF")
      (footprint "eagle-import:C0805")
      (libsource (lib "eagle-import") (part "C0805"))
    )
    (comp (ref "C43")
      (value "10nF")
      (footprint "eagle-import:C0805")
      (libsource (lib "eagle-import") (part "CONDENSAT_CMS_C0805"))
    )
    (comp (ref "C44")
      (value "100nF")
      (footprint "eagle-import:C0805")
      (libsource (lib "eagle-import") (part "CONDENSA@2_C0805"))
    )
    (comp (ref "C45")
      (value "10nF")
      (footprint "eagle-import:C0805")
      (libsource (lib "eagle-import") (part "CONDENSAT_CMS_C0805"))
    )
    (comp (ref "C49")
      (value "100nF")
      (footprint "eagle-import:C0805")
      (libsource (lib "eagle-import") (part "C0805"))
    )
    (comp (ref "C50")
      (value "10nF")
      (footprint "eagle-import:C0805")
      (libsource (lib "eagle-import") (part "C0805"))
    )
    (comp (ref "C53")
      (value "10 nF")
      (footprint "eagle-import:C0805")
      (libsource (lib "eagle-import") (part "C0805"))
    )
    (comp (ref "C54")
      (value "1µF")
      (footprint "eagle-import:C0805")
      (libsource (lib "eagle-import") (part "C0805"))
    )
    (comp (ref "C77")
      (value "100nF")
      (footprint "eagle-import:C0805")
      (libsource (lib "eagle-import") (part "CONDENSAT_CMS_C0805"))
    )
    (comp (ref "C78")
      (value "100nF")
      (footprint "eagle-import:C0805")
      (libsource (lib "eagle-import") (part "C0805"))
    )
    (comp (ref "C84")
      (value "1nF")
      (footprint "eagle-import:C0805")
      (libsource (lib "eagle-import") (part "C0805"))
    )
    (comp (ref "D12")
      (value "BZV55-C12")
      (footprint "eagle-import:SOT23DIO")
      (libsource (lib "eagle-import") (part "BZX84CXX"))
    )
    (comp (ref "D14")
      (value "BAT54C")
      (footprint "eagle-import:SOT23_DI")
      (libsource (lib "eagle-import") (part "BAT54C"))
    )
    (comp (ref "D15")
      (value "PRLL5819")
      (footprint "eagle-import:SOD87")
      (libsource (lib "eagle-import") (part "PRLL5819"))
    )
    (comp (ref "D16")
      (value "PRLL5819")
      (footprint "eagle-import:SOD87")
      (libsource (lib "eagle-import") (part "PRLL5819"))
    )
    (comp (ref "G1")
      (value "3V")
      (footprint "eagle-import:KEY_3000")
      (libsource (lib "eagle-import") (part "KEY_3000"))
    )
    (comp (ref "IC10")
      (value "DS1305E")
      (footprint "eagle-import:TSSOP20")
      (libsource (lib "eagle-import") (part "DS1305E"))
    )
    (comp (ref "IC11")
      (value "OP295")
      (footprint "eagle-import:SO8")
      (libsource (lib "eagle-import") (part "LM358"))
    )
    (comp (ref "IC12")
      (value "MAX690ACSA")
      (footprint "eagle-import:SO08")
      (libsource (lib "eagle-import") (part "MAX690ACSA"))
    )
    (comp (ref "IC31")
      (value "M41T94MQ6E")
      (footprint "eagle-import:SO16")
      (libsource (lib "eagle-import") (part "M41T94MQ6E"))
    )
    (comp (ref "Q3")
      (value "32,768KHz")
      (footprint "eagle-import:86SMX")
      (libsource (lib "eagle-import") (part "86SMX"))
    )
    (comp (ref "Q5")
      (value "32,768KHz")
      (footprint "eagle-import:86SMX")
      (libsource (lib "eagle-import") (part "86SMX"))
    )
    (comp (ref "R8")
      (value "100K")
      (footprint "eagle-import:R0805")
      (libsource (lib "eagle-import") (part "R0805"))
    )
    (comp (ref "R9")
      (value "100K")
      (footprint "eagle-import:R0805")
      (libsource (lib "eagle-import") (part "R0805"))
    )
    (comp (ref "R17")
      (value "15K")
      (footprint "eagle-import:R0805")
      (libsource (lib "eagle-import") (part "R0805"))
    )
    (comp (ref "R18")
      (value "1.5K")
      (footprint "eagle-import:R0805")
      (libsource (lib "eagle-import") (part "R0805"))
    )
    (comp (ref "R19")
      (value "75K")
      (footprint "eagle-import:R0805")
      (libsource (lib "eagle-import") (part "R0805"))
    )
    (comp (ref "R28")
      (value "10K")
      (footprint "eagle-import:R0805")
      (libsource (lib "eagle-import") (part "R0805"))
    )
    (comp (ref "R29")
      (value "10K")
      (footprint "eagle-import:R0805")
      (libsource (lib "eagle-import") (part "R0805"))
    )
    (comp (ref "R52")
      (value "10")
      (footprint "eagle-import:R0805")
      (libsource (lib "eagle-import") (part "RESIST_CMS_R0805"))
    )
    (comp (ref "R53")
      (value "10K")
      (footprint "eagle-import:R0805")
      (libsource (lib "eagle-import") (part "RESIST_CMS_R0805"))
    )
    (comp (ref "R54")
      (value "10K")
      (footprint "eagle-import:R0805")
      (libsource (lib "eagle-import") (part "RESIST_CMS_R0805"))
    )
    (comp (ref "R55")
      (value "100K")
      (footprint "eagle-import:R0805")
      (libsource (lib "eagle-import") (part "RESIST_CMS_R0805"))
    )
    (comp (ref "R56")
      (value "100K")
      (footprint "eagle-import:R0805")
      (libsource (lib "eagle-import") (part "RESIST_CMS_R0805"))
    )
    (comp (ref "R57")
      (value "1.37K")
      (footprint "eagle-import:R0805")
      (libsource (lib "eagle-import") (part "R0805"))
    )
    (comp (ref "R58")
      (value "100K")
      (footprint "eagle-import:R0805")
      (libsource (lib "eagle-import") (part "R0805"))
    )
    (comp (ref "R59")
      (value "100K")
      (footprint "eagle-import:R0805")
      (libsource (lib "eagle-import") (part "R0805"))
    )
    (comp (ref "R65")
      (value "100K")
      (footprint "eagle-import:R0805")
      (libsource (lib "eagle-import") (part "R0805"))
    )
    (comp (ref "T3")
      (value "BSS84")
      (footprint "eagle-import:SOT23MOS")
      (libsource (lib "eagle-import") (part "IRLML5103"))
    )
    (comp (ref "T14")
      (value "2N7002")
      (footprint "eagle-import:DPAK")
      (libsource (lib "eagle-import") (part "MTD3055"))
    )
    (comp (ref "T20")
      (value "BS170F")
      (footprint "eagle-import:DPAK")
      (libsource (lib "eagle-import") (part "MTD3055"))
    )
    (comp (ref "T21")
      (value "2N7002")
      (footprint "eagle-import:DPAK")
      (libsource (lib "eagle-import") (part "MTD3055"))
    )
    (comp (ref "V2")
      (value "FAS-PPS-1P-3NIP-INJ")
      (footprint "eagle-import:FAS-PPS-1P-3NIP-INJ")
      (libsource (lib "eagle-import") (part "FAS-PPS-1P-3NIP-INJ"))
    )
    (comp (ref "ANT")
      (value "ANTENNE")
      (footprint "eagle-import:ANTENNE")
      (libsource (lib "eagle-import") (part "ANTENNE"))
    )
    (comp (ref "C11")
      (value "100nF")
      (footprint "eagle-import:C0805")
      (libsource (lib "eagle-import") (part "CONDENSAT_CMS_C0805"))
    )
    (comp (ref "C12")
      (value "47pF")
      (footprint "eagle-import:C0603")
      (libsource (lib "eagle-import") (part "CONDENSAT_CMS_C0603"))
    )
    (comp (ref "C13")
      (value "47pF")
      (footprint "eagle-import:C0603")
      (libsource (lib "eagle-import") (part "CONDENSAT_CMS_C0603"))
    )
    (comp (ref "C38")
      (value "47pF")
      (footprint "eagle-import:RESEAU_1")
      (libsource (lib "eagle-import") (part "RESEAU_4C"))
    )
    (comp (ref "C56")
      (value "47pF")
      (footprint "eagle-import:RESEAU_1")
      (libsource (lib "eagle-import") (part "RESEAU_4C"))
    )
    (comp (ref "C75")
      (value "47uF")
      (footprint "eagle-import:TANTALB")
      (libsource (lib "eagle-import") (part "CONDENSAT_CMS_TANTALB"))
    )
    (comp (ref "C76")
      (value "100nF")
      (footprint "eagle-import:C0603")
      (libsource (lib "eagle-import") (part "CONDENSAT_CMS_C0603"))
    )
    (comp (ref "C86")
      (value "47pF")
      (footprint "eagle-import:C0805")
      (libsource (lib "eagle-import") (part "CONDENSAT_CMS_C0805"))
    )
    (comp (ref "C89")
      (value "22uF")
      (footprint "eagle-import:TANTALB")
      (libsource (lib "eagle-import") (part "CONDENSAT_CMS_TANTALB"))
    )
    (comp (ref "C93")
      (value "100nF")
      (footprint "eagle-import:C0805")
      (libsource (lib "eagle-import") (part "CONDENSAT_CMS_C0805"))
    )
    (comp (ref "C98")
      (value "100nF")
      (footprint "eagle-import:C0805")
      (libsource (lib "eagle-import") (part "CONDENSAT_CMS_C0805"))
    )
    (comp (ref "C99")
      (value "150pF")
      (footprint "eagle-import:C0603")
      (libsource (lib "eagle-import") (part "C0603"))
    )
    (comp (ref "C100")
      (value "47pF")
      (footprint "eagle-import:RESEAU_1")
      (libsource (lib "eagle-import") (part "RESEAU_4C"))
    )
    (comp (ref "C101")
      (value "4.7 nF")
      (footprint "eagle-import:C0805")
      (libsource (lib "eagle-import") (part "CONDENSAT_CMS_C0805"))
    )
    (comp (ref "C115")
      (value "150pF")
      (footprint "eagle-import:C0603")
      (libsource (lib "eagle-import") (part "C0603"))
    )
    (comp (ref "C121")
      (value "150pF")
      (footprint "eagle-import:C0603")
      (libsource (lib "eagle-import") (part "C0603"))
    )
    (comp (ref "C122")
      (value "150pF")
      (footprint "eagle-import:C0603")
      (libsource (lib "eagle-import") (part "C0603"))
    )
    (comp (ref "C123")
      (value "150pF")
      (footprint "eagle-import:C0603")
      (libsource (lib "eagle-import") (part "C0603"))
    )
    (comp (ref "C124")
      (value "150pF")
      (footprint "eagle-import:C0603")
      (libsource (lib "eagle-import") (part "C0603"))
    )
    (comp (ref "C126")
      (value "150pF")
      (footprint "eagle-import:C0603")
      (libsource (lib "eagle-import") (part "C0603"))
    )
    (comp (ref "C127")
      (value "150pF")
      (footprint "eagle-import:C0603")
      (libsource (lib "eagle-import") (part "C0603"))
    )
    (comp (ref "C130")
      (value "100nF")
      (footprint "eagle-import:C0805")
      (libsource (lib "eagle-import") (part "CONDENSAT_CMS_C0805"))
    )
    (comp (ref "D6")
      (value "PRLL5819")
      (footprint "eagle-import:SOD87")
      (libsource (lib "eagle-import") (part "PRLL5819"))
    )
    (comp (ref "D13")
      (value "BAT54")
      (footprint "eagle-import:SOT23DIO")
      (libsource (lib "eagle-import") (part "BAT54"))
    )
    (comp (ref "IC37")
      (value "ARF34")
      (footprint "eagle-import:ARF34")
      (libsource (lib "eagle-import") (part "ARF34"))
    )
    (comp (ref "J2")
      (value "B8B_ZR")
      (footprint "eagle-import:8BR")
      (libsource (lib "eagle-import") (part "B8B_ZR"))
    )
    (comp (ref "J4")
      (value "10BRMF")
      (footprint "eagle-import:MF10BR")
      (libsource (lib "eagle-import") (part "10BRMF"))
    )
    (comp (ref "J5")
      (value "B2B_ZR")
      (footprint "eagle-import:2BR")
      (libsource (lib "eagle-import") (part "B2B_ZR"))
    )
    (comp (ref "J11")
      (value "B3B_ZR")
      (footprint "eagle-import:3BR")
      (libsource (lib "eagle-import") (part "B3B_ZR"))
    )
    (comp (ref "J18")
      (value "B7B_ZR_SM3_TF")
      (footprint "eagle-import:7B_ZR_SM3_TF")
      (libsource (lib "eagle-import") (part "B7B_ZR_SM3_TF"))
    )
    (comp (ref "J19")
      (value "B2B_ZR")
      (footprint "eagle-import:2BR")
      (libsource (lib "eagle-import") (part "B2B_ZR"))
    )
    (comp (ref "J20")
      (value "B4B_ZR")
      (footprint "eagle-import:4BR")
      (libsource (lib "eagle-import") (part "B4B_ZR"))
    )
    (comp (ref "J21")
      (value "2BR254C")
      (footprint "eagle-import:2BR254C")
      (libsource (lib "eagle-import") (part "2BR254C"))
    )
    (comp (ref "L7")
      (value "74279263")
      (footprint "eagle-import:0603")
      (libsource (lib "eagle-import") (part "74279263"))
    )
    (comp (ref "L9")
      (value "74279263")
      (footprint "eagle-import:0603")
      (libsource (lib "eagle-import") (part "74279263"))
    )
    (comp (ref "L10")
      (value "74279263")
      (footprint "eagle-import:0603")
      (libsource (lib "eagle-import") (part "74279263"))
    )
    (comp (ref "L11")
      (value "74279263")
      (footprint "eagle-import:0603")
      (libsource (lib "eagle-import") (part "74279263"))
    )
    (comp (ref "L12")
      (value "74279263")
      (footprint "eagle-import:0603")
      (libsource (lib "eagle-import") (part "74279263"))
    )
    (comp (ref "L13")
      (value "74279263")
      (footprint "eagle-import:0603")
      (libsource (lib "eagle-import") (part "74279263"))
    )
    (comp (ref "L14")
      (value "74279263")
      (footprint "eagle-import:0603")
      (libsource (lib "eagle-import") (part "74279263"))
    )
    (comp (ref "L15")
      (value "74279263")
      (footprint "eagle-import:0603")
      (libsource (lib "eagle-import") (part "74279263"))
    )
    (comp (ref "L17")
      (value "74279263")
      (footprint "eagle-import:0603")
      (libsource (lib "eagle-import") (part "74279263"))
    )
    (comp (ref "L19")
      (value "74279263")
      (footprint "eagle-import:0603")
      (libsource (lib "eagle-import") (part "74279263"))
    )
    (comp (ref "L20")
      (value "74279263")
      (footprint "eagle-import:0603")
      (libsource (lib "eagle-import") (part "74279263"))
    )
    (comp (ref "L21")
      (value "74279263")
      (footprint "eagle-import:0603")
      (libsource (lib "eagle-import") (part "74279263"))
    )
    (comp (ref "L22")
      (value "74279263")
      (footprint "eagle-import:0603")
      (libsource (lib "eagle-import") (part "74279263"))
    )
    (comp (ref "L23")
      (value "74279263")
      (footprint "eagle-import:0603")
      (libsource (lib "eagle-import") (part "74279263"))
    )
    (comp (ref "L24")
      (value "74279263")
      (footprint "eagle-import:0603")
      (libsource (lib "eagle-import") (part "74279263"))
    )
    (comp (ref "L25")
      (value "74279263")
      (footprint "eagle-import:0603")
      (libsource (lib "eagle-import") (part "74279263"))
    )
    (comp (ref "L26")
      (value "74279263")
      (footprint "eagle-import:0603")
      (libsource (lib "eagle-import") (part "74279263"))
    )
    (comp (ref "L27")
      (value "74279263")
      (footprint "eagle-import:0603")
      (libsource (lib "eagle-import") (part "74279263"))
    )
    (comp (ref "L28")
      (value "74279263")
      (footprint "eagle-import:0603")
      (libsource (lib "eagle-import") (part "74279263"))
    )
    (comp (ref "L29")
      (value "74279263")
      (footprint "eagle-import:0603")
      (libsource (lib "eagle-import") (part "74279263"))
    )
    (comp (ref "L31")
      (value "74279263")
      (footprint "eagle-import:0603")
      (libsource (lib "eagle-import") (part "74279263"))
    )
    (comp (ref "L32")
      (value "74279263")
      (footprint "eagle-import:0603")
      (libsource (lib "eagle-import") (part "74279263"))
    )
    (comp (ref "L33")
      (value "74279263")
      (footprint "eagle-import:0603")
      (libsource (lib "eagle-import") (part "74279263"))
    )
    (comp (ref "L34")
      (value "74279263")
      (footprint "eagle-import:0603")
      (libsource (lib "eagle-import") (part "74279263"))
    )
    (comp (ref "L37")
      (value "74279263")
      (footprint "eagle-import:0603")
      (libsource (lib "eagle-import") (part "74279263"))
    )
    (comp (ref "R11")
      (value "3.3K")
      (footprint "eagle-import:R0805")
      (libsource (lib "eagle-import") (part "RESIST_CMS_R0805"))
    )
    (comp (ref "R43")
      (value "10K")
      (footprint "eagle-import:R0805")
      (libsource (lib "eagle-import") (part "RESIST_CMS_R0805"))
    )
    (comp (ref "R48")
      (value "100K")
      (footprint "eagle-import:R0805")
      (libsource (lib "eagle-import") (part "RESIST_CMS_R0805"))
    )
    (comp (ref "R49")
      (value "4.7K")
      (footprint "eagle-import:R0805")
      (libsource (lib "eagle-import") (part "R0805"))
    )
    (comp (ref "R68")
      (value "100K")
      (footprint "eagle-import:R0805")
      (libsource (lib "eagle-import") (part "RESIST_CMS_R0805"))
    )
    (comp (ref "R69")
      (value "0")
      (footprint "eagle-import:R0805")
      (libsource (lib "eagle-import") (part "RESIST_CMS_R0805"))
    )
    (comp (ref "R70")
      (value "10K")
      (footprint "eagle-import:R0805")
      (libsource (lib "eagle-import") (part "RESIST_CMS_R0805"))
    )
    (comp (ref "RL1")
      (value "G6K2G")
      (footprint "eagle-import:G6K2G")
      (libsource (lib "eagle-import") (part "G6K2G"))
    )
    (comp (ref "T17")
      (value "IRLML5103")
      (footprint "eagle-import:SOT23MOS")
      (libsource (lib "eagle-import") (part "IRLML5103"))
    )
    (comp (ref "T19")
      (value "BSS84")
      (footprint "eagle-import:SOT23MOS")
      (libsource (lib "eagle-import") (part "IRLML5103"))
    )
    (comp (ref "C21")
      (value "100uF")
      (footprint "eagle-import:MV100_F")
      (libsource (lib "eagle-import") (part "MV100?F50V"))
    )
    (comp (ref "C46")
      (value "100nF")
      (footprint "eagle-import:C0805")
      (libsource (lib "eagle-import") (part "CONDENSAT_CMS_C0805"))
    )
    (comp (ref "C47")
      (value "220pF")
      (footprint "eagle-import:C0805")
      (libsource (lib "eagle-import") (part "CONDENSAT_CMS_C0805"))
    )
    (comp (ref "C74")
      (value "100nF")
      (footprint "eagle-import:C0805")
      (libsource (lib "eagle-import") (part "CONDENSAT_CMS_C0805"))
    )
    (comp (ref "C79")
      (value "100nF")
      (footprint "eagle-import:C0805")
      (libsource (lib "eagle-import") (part "C0805"))
    )
    (comp (ref "C80")
      (value "100nF")
      (footprint "eagle-import:C0805")
      (libsource (lib "eagle-import") (part "C0805"))
    )
    (comp (ref "C81")
      (value "10uF")
      (footprint "eagle-import:TANTALD")
      (libsource (lib "eagle-import") (part "TANTALD"))
    )
    (comp (ref "C82")
      (value "100nF")
      (footprint "eagle-import:C0805")
      (libsource (lib "eagle-import") (part "C0805"))
    )
    (comp (ref "C83")
      (value "100nF")
      (footprint "eagle-import:C0805")
      (libsource (lib "eagle-import") (part "C0805"))
    )
    (comp (ref "C85")
      (value "10uF")
      (footprint "eagle-import:TANTALD")
      (libsource (lib "eagle-import") (part "TANTALD"))
    )
    (comp (ref "C88")
      (value "1000uF")
      (footprint "eagle-import:MV100_F")
      (libsource (lib "eagle-import") (part "MV100?F50V"))
    )
    (comp (ref "C90")
      (value "100nF")
      (footprint "eagle-import:C0805")
      (libsource (lib "eagle-import") (part "CONDENSAT_CMS_C0805"))
    )
    (comp (ref "C91")
      (value "100nF")
      (footprint "eagle-import:C0805")
      (libsource (lib "eagle-import") (part "CONDENSAT_CMS_C0805"))
    )
    (comp (ref "C92")
      (value "22µF")
      (footprint "eagle-import:TANTALB")
      (libsource (lib "eagle-import") (part "CONDENSAT_CMS_TANTALB"))
    )
    (comp (ref "C97")
      (value "10nF")
      (footprint "eagle-import:C0805")
      (libsource (lib "eagle-import") (part "CONDENSAT_CMS_C0805"))
    )
    (comp (ref "C105")
      (value "100nF")
      (footprint "eagle-import:C0805")
      (libsource (lib "eagle-import") (part "CONDENSAT_CMS_C0805"))
    )
    (comp (ref "C106")
      (value "220µF")
      (footprint "eagle-import:CHCMS_D8")
      (libsource (lib "eagle-import") (part "CHCMS_D8"))
    )
    (comp (ref "C107")
      (value "100nF")
      (footprint "eagle-import:C0805")
      (libsource (lib "eagle-import") (part "CONDENSAT_CMS_C0805"))
    )
    (comp (ref "C108")
      (value "10µF")
      (footprint "eagle-import:TANTALB")
      (libsource (lib "eagle-import") (part "CONDENSAT_CMS_TANTALB"))
    )
    (comp (ref "C117")
      (value "10µF")
      (footprint "eagle-import:TANTALB")
      (libsource (lib "eagle-import") (part "CONDENSAT_CMS_TANTALB"))
    )
    (comp (ref "D4")
      (value "1SMB36AT3")
      (footprint "eagle-import:C4111-15")
      (libsource (lib "eagle-import") (part "ICTE5"))
    )
    (comp (ref "D7")
      (value "PRLL5819")
      (footprint "eagle-import:SOD87")
      (libsource (lib "eagle-import") (part "TRANSIST_DIOD_CMS_PRLL5819"))
    )
    (comp (ref "D11")
      (value "STPS340U")
      (footprint "eagle-import:SOT23DIO")
      (libsource (lib "eagle-import") (part "BAT54"))
    )
    (comp (ref "FU2")
      (value "500 mA T")
      (footprint "eagle-import:SLOBLO")
      (libsource (lib "eagle-import") (part "SLOBLO"))
    )
    (comp (ref "IC21")
      (value "LT1236ACS8-5")
      (footprint "eagle-import:SO8")
      (libsource (lib "eagle-import") (part "LT1236"))
    )
    (comp (ref "IC23")
      (value "LT1236ACS8-10")
      (footprint "eagle-import:SO8")
      (libsource (lib "eagle-import") (part "LT1236"))
    )
    (comp (ref "IC24")
      (value "STM809LWX")
      (footprint "eagle-import:SOT23")
      (libsource (lib "eagle-import") (part "STM809"))
    )
    (comp (ref "IC25")
      (value "STM809LWX")
      (footprint "eagle-import:SOT23")
      (libsource (lib "eagle-import") (part "STM809"))
    )
    (comp (ref "IC26")
      (value "LF33CDT")
      (footprint "eagle-import:REGUL-DPAK")
      (libsource (lib "eagle-import") (part "LF33CDT"))
    )
    (comp (ref "IC29")
      (value "TPS5430")
      (footprint "eagle-import:SO8POWERPAD")
      (libsource (lib "eagle-import") (part "TPS5430DDA"))
    )
    (comp (ref "IC36")
      (value "STM809TWX")
      (footprint "eagle-import:SOT23")
      (libsource (lib "eagle-import") (part "STM809"))
    )
    (comp (ref "JP9")
      (value "JUMP_0U")
      (footprint "eagle-import:0805")
      (libsource (lib "eagle-import") (part "JUMP_0U"))
    )
    (comp (ref "L2")
      (value "33µH")
      (footprint "eagle-import:WE-TPC-MH")
      (libsource (lib "eagle-import") (part "WE-TPC-MH"))
    )
    (comp (ref "L30")
      (value "7427504")
      (footprint "eagle-import:PERL-FER")
      (libsource (lib "eagle-import") (part "7427504"))
    )
    (comp (ref "R35")
      (value "180")
      (footprint "eagle-import:R0805")
      (libsource (lib "eagle-import") (part "RESIST_CMS_R0805"))
    )
    (comp (ref "R36")
      (value "75K")
      (footprint "eagle-import:R0805")
      (libsource (lib "eagle-import") (part "RESIST_CMS_R0805"))
    )
    (comp (ref "R40")
      (value "15K")
      (footprint "eagle-import:R0805")
      (libsource (lib "eagle-import") (part "RESIST_CMS_R0805"))
    )
    (comp (ref "R41")
      (value "4.7K")
      (footprint "eagle-import:R1206")
      (libsource (lib "eagle-import") (part "RESIST_CMS_R1206"))
    )
    (comp (ref "R44")
      (value "180")
      (footprint "eagle-import:R0805")
      (libsource (lib "eagle-import") (part "RESIST_CMS_R0805"))
    )
    (comp (ref "R66")
      (value "470")
      (footprint "eagle-import:R0805")
      (libsource (lib "eagle-import") (part "RESIST_CMS_R0805"))
    )
    (comp (ref "R67")
      (value "470")
      (footprint "eagle-import:R0805")
      (libsource (lib "eagle-import") (part "RESIST_CMS_R0805"))
    )
    (comp (ref "R71")
      (value "10k")
      (footprint "eagle-import:R0805")
      (libsource (lib "eagle-import") (part "RESIST_CMS_R0805"))
    )
    (comp (ref "R73")
      (value "3.24k")
      (footprint "eagle-import:R0805")
      (libsource (lib "eagle-import") (part "RESIST_CMS_R0805"))
    )
    (comp (ref "T10")
      (value "FZT953")
      (footprint "eagle-import:SOT223")
      (libsource (lib "eagle-import") (part "BCP51"))
    )
    (comp (ref "T11")
      (value "FZT953")
      (footprint "eagle-import:SOT223")
      (libsource (lib "eagle-import") (part "BCP51"))
    )
    (comp (ref "T12")
      (value "FZT953")
      (footprint "eagle-import:SOT223")
      (libsource (lib "eagle-import") (part "BCP51"))
    )
    (comp (ref "BL1")
      (value "BLIN-AWM33")
      (footprint "eagle-import:BLIN-AWM")
      (libsource (lib "eagle-import") (part "BLIN-AWM33"))
    )
    (comp (ref "BL2")
      (value "2XBL-AWM")
      (footprint "eagle-import:2XBL-AWM")
      (libsource (lib "eagle-import") (part "2XBL-AWM"))
    )
    (comp (ref "BL3")
      (value "BLIN-AWM33")
      (footprint "eagle-import:BLIN-AWM")
      (libsource (lib "eagle-import") (part "BLIN-AWM33"))
    )
    (comp (ref "BL4")
      (value "3XBL-ADSX")
      (footprint "eagle-import:3XBL-AWM")
      (libsource (lib "eagle-import") (part "3XBL-ADSX"))
    )
    (comp (ref "C40")
      (value "100nF")
      (footprint "eagle-import:C0805")
      (libsource (lib "eagle-import") (part "C0805"))
    )
    (comp (ref "C48")
      (value "100nF")
      (footprint "eagle-import:C0805")
      (libsource (lib "eagle-import") (part "C0805"))
    )
    (comp (ref "C57")
      (value "100nF")
      (footprint "eagle-import:C0805")
      (libsource (lib "eagle-import") (part "C0805"))
    )
    (comp (ref "C59")
      (value "220nF")
      (footprint "eagle-import:C1206")
      (libsource (lib "eagle-import") (part "C1206"))
    )
    (comp (ref "C60")
      (value "100nF")
      (footprint "eagle-import:C0805")
      (libsource (lib "eagle-import") (part "C0805"))
    )
    (comp (ref "C61")
      (value "4.7nF")
      (footprint "eagle-import:C0805")
      (libsource (lib "eagle-import") (part "C0805"))
    )
    (comp (ref "C62")
      (value "100nF")
      (footprint "eagle-import:C0805")
      (libsource (lib "eagle-import") (part "C0805"))
    )
    (comp (ref "C63")
      (value "100nF")
      (footprint "eagle-import:C0805")
      (libsource (lib "eagle-import") (part "C0805"))
    )
    (comp (ref "C64")
      (value "4.7nF")
      (footprint "eagle-import:C0805")
      (libsource (lib "eagle-import") (part "C0805"))
    )
    (comp (ref "C65")
      (value "220nF")
      (footprint "eagle-import:C1206")
      (libsource (lib "eagle-import") (part "C1206"))
    )
    (comp (ref "C66")
      (value "100nF")
      (footprint "eagle-import:C0805")
      (libsource (lib "eagle-import") (part "C0805"))
    )
    (comp (ref "C67")
      (value "220nF")
      (footprint "eagle-import:C1206")
      (libsource (lib "eagle-import") (part "C1206"))
    )
    (comp (ref "C68")
      (value "4.7nF")
      (footprint "eagle-import:C0805")
      (libsource (lib "eagle-import") (part "C0805"))
    )
    (comp (ref "C69")
      (value "100nF")
      (footprint "eagle-import:C0805")
      (libsource (lib "eagle-import") (part "C0805"))
    )
    (comp (ref "C70")
      (value "100nF")
      (footprint "eagle-import:C0805")
      (libsource (lib "eagle-import") (part "C0805"))
    )
    (comp (ref "C71")
      (value "4.7nF")
      (footprint "eagle-import:C0805")
      (libsource (lib "eagle-import") (part "C0805"))
    )
    (comp (ref "C72")
      (value "100nF")
      (footprint "eagle-import:C0805")
      (libsource (lib "eagle-import") (part "C0805"))
    )
    (comp (ref "C73")
      (value "4.7nF")
      (footprint "eagle-import:C0805")
      (libsource (lib "eagle-import") (part "C0805"))
    )
    (comp (ref "C94")
      (value "220nF")
      (footprint "eagle-import:C1206")
      (libsource (lib "eagle-import") (part "C1206"))
    )
    (comp (ref "C95")
      (value "100nF")
      (footprint "eagle-import:C0805")
      (libsource (lib "eagle-import") (part "C0805"))
    )
    (comp (ref "C96")
      (value "4.7nF")
      (footprint "eagle-import:C0805")
      (libsource (lib "eagle-import") (part "C0805"))
    )
    (comp (ref "C102")
      (value "220nF")
      (footprint "eagle-import:C1206")
      (libsource (lib "eagle-import") (part "C1206"))
    )
    (comp (ref "C103")
      (value "100nF")
      (footprint "eagle-import:C0805")
      (libsource (lib "eagle-import") (part "C0805"))
    )
    (comp (ref "C104")
      (value "4.7nF")
      (footprint "eagle-import:C0805")
      (libsource (lib "eagle-import") (part "C0805"))
    )
    (comp (ref "C109")
      (value "100nF")
      (footprint "eagle-import:C0805")
      (libsource (lib "eagle-import") (part "C0805"))
    )
    (comp (ref "C113")
      (value "100nF")
      (footprint "eagle-import:C0805")
      (libsource (lib "eagle-import") (part "C0805"))
    )
    (comp (ref "IC15")
      (value "AWM3300V")
      (footprint "eagle-import:AWM3300V")
      (libsource (lib "eagle-import") (part "AWM3300V"))
    )
    (comp (ref "IC16")
      (value "ASDX001D44R-SQ04689")
      (footprint "eagle-import:ASDX")
      (libsource (lib "eagle-import") (part "ASDX"))
    )
    (comp (ref "IC17")
      (value "AWM3300V")
      (footprint "eagle-import:AWM3300V")
      (libsource (lib "eagle-import") (part "AWM3300V"))
    )
    (comp (ref "IC18")
      (value "ASDX001D44R-SQ04689")
      (footprint "eagle-import:ASDX")
      (libsource (lib "eagle-import") (part "ASDX"))
    )
    (comp (ref "IC19")
      (value "ASDX100D44R")
      (footprint "eagle-import:ASDX")
      (libsource (lib "eagle-import") (part "ASDX"))
    )
    (comp (ref "IC22")
      (value "ASDX001D44R-SQ04689")
      (footprint "eagle-import:ASDX")
      (libsource (lib "eagle-import") (part "ASDX"))
    )
    (comp (ref "IC27")
      (value "SQ276")
      (footprint "eagle-import:SQ276")
      (libsource (lib "eagle-import") (part "SQ276"))
    )
    (comp (ref "IC28")
      (value "SQ276")
      (footprint "eagle-import:SQ276")
      (libsource (lib "eagle-import") (part "SQ276"))
    )
    (comp (ref "IC30")
      (value "SQ276")
      (footprint "eagle-import:SQ276")
      (libsource (lib "eagle-import") (part "SQ276"))
    )
    (comp (ref "IC33")
      (value "BSDX0811BARO-X")
      (footprint "eagle-import:ASDX")
      (libsource (lib "eagle-import") (part "ASDX"))
    )
    (comp (ref "IC34")
      (value "SQ276")
      (footprint "eagle-import:SQ276")
      (libsource (lib "eagle-import") (part "SQ276"))
    )
    (comp (ref "IC35")
      (value "SQ276")
      (footprint "eagle-import:SQ276")
      (libsource (lib "eagle-import") (part "SQ276"))
    )
    (comp (ref "JP2")
      (value "JUMP_0U")
      (footprint "eagle-import:0805")
      (libsource (lib "eagle-import") (part "JUMP_0U"))
    )
    (comp (ref "JP3")
      (value "JUMP_0U")
      (footprint "eagle-import:0805")
      (libsource (lib "eagle-import") (part "JUMP_0U"))
    )
    (comp (ref "JP4")
      (value "JUMP_0U")
      (footprint "eagle-import:0805")
      (libsource (lib "eagle-import") (part "JUMP_0U"))
    )
    (comp (ref "R33")
      (value "4.7K")
      (footprint "eagle-import:R0805")
      (libsource (lib "eagle-import") (part "R0805"))
    )
    (comp (ref "R34")
      (value "4.7K")
      (footprint "eagle-import:R0805")
      (libsource (lib "eagle-import") (part "R0805"))
    )
    (comp (ref "R37")
      (value "4.7K")
      (footprint "eagle-import:R0805")
      (libsource (lib "eagle-import") (part "R0805"))
    )
    (comp (ref "R38")
      (value "4.7K")
      (footprint "eagle-import:R0805")
      (libsource (lib "eagle-import") (part "R0805"))
    )
    (comp (ref "R39")
      (value "4.7K")
      (footprint "eagle-import:R0805")
      (libsource (lib "eagle-import") (part "R0805"))
    )
    (comp (ref "R42")
      (value "4.7K")
      (footprint "eagle-import:R0805")
      (libsource (lib "eagle-import") (part "R0805"))
    )
    (comp (ref "R51")
      (value "4.7K")
      (footprint "eagle-import:R0805")
      (libsource (lib "eagle-import") (part "R0805"))
    )
    (comp (ref "C2")
      (value "100nF")
      (footprint "eagle-import:C0805")
      (libsource (lib "eagle-import") (part "C0805"))
    )
    (comp (ref "C4")
      (value "100nF")
      (footprint "eagle-import:C0805")
      (libsource (lib "eagle-import") (part "CONDENSAT_CMS_C0805"))
    )
    (comp (ref "C5")
      (value "100nF")
      (footprint "eagle-import:C0603")
      (libsource (lib "eagle-import") (part "CONDENSAT_CMS_C0603"))
    )
    (comp (ref "C15")
      (value "47pF")
      (footprint "eagle-import:C0805")
      (libsource (lib "eagle-import") (part "CONDENSAT_CMS_C0805"))
    )
    (comp (ref "C16")
      (value "22pF")
      (footprint "eagle-import:C0805")
      (libsource (lib "eagle-import") (part "CONDENSAT_CMS_C0805"))
    )
    (comp (ref "C20")
      (value "100nF")
      (footprint "eagle-import:C0603")
      (libsource (lib "eagle-import") (part "CONDENSAT_CMS_C0603"))
    )
    (comp (ref "C24")
      (value "100nF")
      (footprint "eagle-import:C0805")
      (libsource (lib "eagle-import") (part "C0805"))
    )
    (comp (ref "C30")
      (value "100nF")
      (footprint "eagle-import:C0805")
      (libsource (lib "eagle-import") (part "C0805"))
    )
    (comp (ref "C33")
      (value "100nf")
      (footprint "eagle-import:C0805")
      (libsource (lib "eagle-import") (part "CONDENSAT_CMS_C0805"))
    )
    (comp (ref "C37")
      (value "100nf")
      (footprint "eagle-import:C0805")
      (libsource (lib "eagle-import") (part "CONDENSAT_CMS_C0805"))
    )
    (comp (ref "C140")
      (value "100nF")
      (footprint "eagle-import:C0805")
      (libsource (lib "eagle-import") (part "CONDENSAT_CMS_C0805"))
    )
    (comp (ref "IC1")
      (value "TL16C750IPM")
      (footprint "eagle-import:TQFP64")
      (libsource (lib "eagle-import") (part "TL16C750IPM"))
    )
    (comp (ref "IC2")
      (value "SN74ALVC164245")
      (footprint "eagle-import:TSSOP48")
      (libsource (lib "eagle-import") (part "SN74ALVC164245"))
    )
    (comp (ref "IC5")
      (value "74HCT1G32GW")
      (footprint "eagle-import:SOT23-5")
      (libsource (lib "eagle-import") (part "74HCT1G32GW"))
    )
    (comp (ref "IC7")
      (value "Am29F400-EC")
      (footprint "eagle-import:TS048")
      (libsource (lib "eagle-import") (part "29F800"))
    )
    (comp (ref "IC8")
      (value "SN74LVC1G07DBVT")
      (footprint "eagle-import:SOT753_DBV")
      (libsource (lib "eagle-import") (part "LVC1G07DBVT"))
    )
    (comp (ref "IC9")
      (value "SN74LVC1G07DBVT")
      (footprint "eagle-import:SOT753_DBV")
      (libsource (lib "eagle-import") (part "LVC1G07DBVT"))
    )
    (comp (ref "IC13")
      (value "K9F1G08UOA-PCB0")
      (footprint "eagle-import:TS048")
      (libsource (lib "eagle-import") (part "K9F4G08U0M-PCB000"))
    )
    (comp (ref "IC14")
      (value "74ACT16373")
      (footprint "eagle-import:TSSOP48")
      (libsource (lib "eagle-import") (part "74ACT16373"))
    )
    (comp (ref "IC32")
      (value "25LC320")
      (footprint "eagle-import:SOIC8")
      (libsource (lib "eagle-import") (part "AT25---"))
    )
    (comp (ref "IC38")
      (value "74HCT1G08GW")
      (footprint "eagle-import:SOT23-5")
      (libsource (lib "eagle-import") (part "74HCT1G08GW"))
    )
    (comp (ref "IC39")
      (value "74HCT04GW")
      (footprint "eagle-import:SOT23-5")
      (libsource (lib "eagle-import") (part "74HCT1G04GW"))
    )
    (comp (ref "JP5")
      (value "JUMP_0U")
      (footprint "eagle-import:0805")
      (libsource (lib "eagle-import") (part "JUMP_0U"))
    )
    (comp (ref "JP6")
      (value "JUMP_0U")
      (footprint "eagle-import:0805")
      (libsource (lib "eagle-import") (part "JUMP_0U"))
    )
    (comp (ref "Q2")
      (value "3.6864MHz")
      (footprint "eagle-import:HC49UP")
      (libsource (lib "eagle-import") (part "HC49UP"))
    )
    (comp (ref "R2")
      (value "1.5K")
      (footprint "eagle-import:R0805")
      (libsource (lib "eagle-import") (part "R0805"))
    )
    (comp (ref "R4")
      (value "1M")
      (footprint "eagle-import:R0805")
      (libsource (lib "eagle-import") (part "R0805"))
    )
    (comp (ref "R5")
      (value "10K")
      (footprint "eagle-import:R0805")
      (libsource (lib "eagle-import") (part "R0805"))
    )
    (comp (ref "R6")
      (value "10K")
      (footprint "eagle-import:R0805")
      (libsource (lib "eagle-import") (part "R0805"))
    )
    (comp (ref "RS8")
      (value "6.8K")
      (footprint "eagle-import:BCN16_4_")
      (libsource (lib "eagle-import") (part "RESIST_CMS_RES_4R_BCN"))
    )
  )
  (nets
    (net (code "15") (name "+3,3V") (class "Default")
      (node (ref "C19") (pin "+") (pinfunction "+_+") (pintype "passive"))
      (node (ref "C20") (pin "1") (pinfunction "1_1") (pintype "passive"))
      (node (ref "C35") (pin "1") (pinfunction "1_1") (pintype "passive"))
      (node (ref "C4") (pin "1") (pinfunction "1_1") (pintype "passive"))
      (node (ref "C90") (pin "2") (pinfunction "2_2") (pintype "passive"))
      (node (ref "C92") (pin "+") (pinfunction "+_+") (pintype "passive"))
      (node (ref "IC13") (pin "10") (pinfunction "CE2/_10") (pintype "bidirectional"))
      (node (ref "IC13") (pin "12") (pinfunction "VCC1_12") (pintype "bidirectional"))
      (node (ref "IC13") (pin "14") (pinfunction "CE3/_14") (pintype "bidirectional"))
      (node (ref "IC13") (pin "15") (pinfunction "CE4/_15") (pintype "bidirectional"))
      (node (ref "IC13") (pin "19") (pinfunction "WP/_19") (pintype "bidirectional"))
      (node (ref "IC13") (pin "37") (pinfunction "VCC2_37") (pintype "bidirectional"))
      (node (ref "IC2") (pin "31") (pinfunction "VCCA_31") (pintype "bidirectional"))
      (node (ref "IC2") (pin "42") (pinfunction "VCCA_42") (pintype "bidirectional"))
      (node (ref "IC26") (pin "OUTPUT") (pinfunction "VOUT_OUTPUT") (pintype "bidirectional"))
      (node (ref "IC36") (pin "3") (pinfunction "VCC_3") (pintype "bidirectional"))
      (node (ref "J3") (pin "10") (pinfunction "10_10") (pintype "bidirectional"))
      (node (ref "J3") (pin "11") (pinfunction "11_11") (pintype "bidirectional"))
      (node (ref "J6") (pin "16") (pinfunction "16_16") (pintype "bidirectional"))
      (node (ref "JP5") (pin "2") (pinfunction "2_2") (pintype "passive"))
      (node (ref "R48") (pin "1") (pinfunction "1_1") (pintype "bidirectional"))
      (node (ref "T16") (pin "S") (pinfunction "S_S") (pintype "passive"))
      (node (ref "T17") (pin "S") (pinfunction "S_S") (pintype "passive"))
    )
    (net (code "16") (name "+3,3V-FAILURE") (class "Default")
      (node (ref "IC36") (pin "2") (pinfunction "RESET/_2") (pintype "bidirectional"))
      (node (ref "IC4") (pin "52") (pinfunction "P2.5-CC5IO_52") (pintype "bidirectional"))
    )
    (net (code "17") (name "+5V") (class "Default")
      (node (ref "C10") (pin "1") (pinfunction "1_1") (pintype "passive"))
      (node (ref "C106") (pin "+") (pinfunction "+_+") (pintype "passive"))
      (node (ref "C107") (pin "2") (pinfunction "2_2") (pintype "passive"))
      (node (ref "C108") (pin "+") (pinfunction "+_+") (pintype "passive"))
      (node (ref "C116") (pin "2") (pinfunction "2_2") (pintype "passive"))
      (node (ref "C120") (pin "2") (pinfunction "2_2") (pintype "passive"))
      (node (ref "C140") (pin "2") (pinfunction "2_2") (pintype "passive"))
      (node (ref "C2") (pin "1") (pinfunction "1_1") (pintype "passive"))
      (node (ref "C22") (pin "2") (pinfunction "2_2") (pintype "passive"))
      (node (ref "C23") (pin "2") (pinfunction "2_2") (pintype "passive"))
      (node (ref "C24") (pin "1") (pinfunction "1_1") (pintype "passive"))
      (node (ref "C25") (pin "2") (pinfunction "2_2") (pintype "passive"))
      (node (ref "C26") (pin "2") (pinfunction "2_2") (pintype "passive"))
      (node (ref "C27") (pin "2") (pinfunction "2_2") (pintype "passive"))
      (node (ref "C28") (pin "2") (pinfunction "2_2") (pintype "passive"))
      (node (ref "C29") (pin "2") (pinfunction "2_2") (pintype "passive"))
      (node (ref "C30") (pin "1") (pinfunction "1_1") (pintype "passive"))
      (node (ref "C31") (pin "+") (pinfunction "+_+") (pintype "passive"))
      (node (ref "C32") (pin "+") (pinfunction "+_+") (pintype "passive"))
      (node (ref "C33") (pin "1") (pinfunction "1_1") (pintype "passive"))
      (node (ref "C34") (pin "+") (pinfunction "+_+") (pintype "passive"))
      (node (ref "C37") (pin "2") (pinfunction "2_2") (pintype "passive"))
      (node (ref "C42") (pin "1") (pinfunction "1_1") (pintype "passive"))
      (node (ref "C44") (pin "1") (pinfunction "1_1") (pintype "passive"))
      (node (ref "C5") (pin "2") (pinfunction "2_2") (pintype "passive"))
      (node (ref "C77") (pin "2") (pinfunction "2_2") (pintype "passive"))
      (node (ref "C78") (pin "2") (pinfunction "2_2") (pintype "passive"))
      (node (ref "C91") (pin "2") (pinfunction "2_2") (pintype "passive"))
      (node (ref "D1") (pin "2") (pinfunction "2_2") (pintype "bidirectional"))
      (node (ref "D2") (pin "2") (pinfunction "2_2") (pintype "bidirectional"))
      (node (ref "D3") (pin "2") (pinfunction "2_2") (pintype "bidirectional"))
      (node (ref "D5") (pin "2") (pinfunction "2_2") (pintype "bidirectional"))
      (node (ref "IC1") (pin "40") (pinfunction "VCC_40") (pintype "bidirectional"))
      (node (ref "IC1") (pin "59") (pinfunction "CS0_59") (pintype "input"))
      (node (ref "IC1") (pin "61") (pinfunction "CS1_61") (pintype "input"))
      (node (ref "IC10") (pin "11") (pinfunction "SERMODE_11") (pintype "input"))
      (node (ref "IC10") (pin "17") (pinfunction "VCCIF_17") (pintype "bidirectional"))
      (node (ref "IC10") (pin "20") (pinfunction "VCC1_20") (pintype "bidirectional"))
      (node (ref "IC11") (pin "8") (pinfunction "VCC_8") (pintype "bidirectional"))
      (node (ref "IC12") (pin "2") (pinfunction "VCC_2") (pintype "bidirectional"))
      (node (ref "IC14") (pin "18") (pinfunction "VCC2_18") (pintype "bidirectional"))
      (node (ref "IC14") (pin "31") (pinfunction "VCC3_31") (pintype "bidirectional"))
      (node (ref "IC14") (pin "42") (pinfunction "VCC4_42") (pintype "bidirectional"))
      (node (ref "IC14") (pin "7") (pinfunction "VCC1_7") (pintype "bidirectional"))
      (node (ref "IC2") (pin "18") (pinfunction "VCCB_18") (pintype "bidirectional"))
      (node (ref "IC2") (pin "7") (pinfunction "VCCB_7") (pintype "bidirectional"))
      (node (ref "IC26") (pin "INPUT") (pinfunction "VIN_INPUT") (pintype "bidirectional"))
      (node (ref "IC3") (pin "11") (pinfunction "VCC1_11") (pintype "bidirectional"))
      (node (ref "IC3") (pin "33") (pinfunction "VCC2_33") (pintype "bidirectional"))
      (node (ref "IC31") (pin "16") (pinfunction "VCC_16") (pintype "bidirectional"))
      (node (ref "IC32") (pin "3") (pinfunction "WP/_3") (pintype "input"))
      (node (ref "IC32") (pin "7") (pinfunction "HOLD/_7") (pintype "input"))
      (node (ref "IC32") (pin "8") (pinfunction "VCC_8") (pintype "bidirectional"))
      (node (ref "IC38") (pin "5") (pinfunction "VCC_5") (pintype "bidirectional"))
      (node (ref "IC39") (pin "5") (pinfunction "VCC_5") (pintype "bidirectional"))
      (node (ref "IC4") (pin "109") (pinfunction "VDD7_109") (pintype "bidirectional"))
      (node (ref "IC4") (pin "126") (pinfunction "VDD8_126") (pintype "bidirectional"))
      (node (ref "IC4") (pin "136") (pinfunction "VDD9_136") (pintype "bidirectional"))
      (node (ref "IC4") (pin "144") (pinfunction "XTAL4_144") (pintype "bidirectional"))
      (node (ref "IC4") (pin "17") (pinfunction "VDD1_17") (pintype "bidirectional"))
      (node (ref "IC4") (pin "46") (pinfunction "VDD2_46") (pintype "bidirectional"))
      (node (ref "IC4") (pin "72") (pinfunction "VDD4_72") (pintype "bidirectional"))
      (node (ref "IC4") (pin "82") (pinfunction "VDD5_82") (pintype "bidirectional"))
      (node (ref "IC4") (pin "93") (pinfunction "VDD6_93") (pintype "bidirectional"))
      (node (ref "IC4") (pin "97") (pinfunction "READY/_97") (pintype "bidirectional"))
      (node (ref "IC4") (pin "99") (pinfunction "EA/-VSTBY_99") (pintype "input"))
      (node (ref "IC44") (pin "5") (pinfunction "VCC_5") (pintype "bidirectional"))
      (node (ref "IC5") (pin "5") (pinfunction "VCC_5") (pintype "bidirectional"))
      (node (ref "IC7") (pin "37") (pinfunction "VCC_37") (pintype "bidirectional"))
      (node (ref "IC7") (pin "47") (pinfunction "BYTE/_47") (pintype "input"))
      (node (ref "J1") (pin "11B") (pinfunction "11B_11B") (pintype "bidirectional"))
      (node (ref "J1") (pin "8B") (pinfunction "8B_8B") (pintype "bidirectional"))
      (node (ref "J17") (pin "2") (pinfunction "P$2_2") (pintype "bidirectional"))
      (node (ref "J17") (pin "22") (pinfunction "P$22_22") (pintype "bidirectional"))
      (node (ref "J17") (pin "39") (pinfunction "P$39_39") (pintype "bidirectional"))
      (node (ref "JP6") (pin "2") (pinfunction "2_2") (pintype "passive"))
      (node (ref "L2") (pin "1") (pinfunction "1_1") (pintype "bidirectional"))
      (node (ref "R28") (pin "2") (pinfunction "2_2") (pintype "bidirectional"))
      (node (ref "R3") (pin "2") (pinfunction "2_2") (pintype "bidirectional"))
      (node (ref "R32") (pin "2") (pinfunction "2_2") (pintype "bidirectional"))
      (node (ref "R5") (pin "2") (pinfunction "2_2") (pintype "bidirectional"))
      (node (ref "R68") (pin "2") (pinfunction "2_2") (pintype "bidirectional"))
      (node (ref "R71") (pin "1") (pinfunction "1_1") (pintype "bidirectional"))
      (node (ref "RS1") (pin "1") (pinfunction "1_1") (pintype "bidirectional"))
      (node (ref "RS1") (pin "2") (pinfunction "2_2") (pintype "bidirectional"))
      (node (ref "RS1") (pin "4") (pinfunction "4_4") (pintype "bidirectional"))
      (node (ref "RS2") (pin "1") (pinfunction "1_1") (pintype "bidirectional"))
      (node (ref "RS2") (pin "2") (pinfunction "2_2") (pintype "bidirectional"))
      (node (ref "RS2") (pin "3") (pinfunction "3_3") (pintype "bidirectional"))
      (node (ref "RS2") (pin "4") (pinfunction "4_4") (pintype "bidirectional"))
      (node (ref "RS3") (pin "2") (pinfunction "2_2") (pintype "bidirectional"))
      (node (ref "RS3") (pin "4") (pinfunction "4_4") (pintype "bidirectional"))
      (node (ref "RS4") (pin "1") (pinfunction "1_1") (pintype "bidirectional"))
      (node (ref "RS4") (pin "2") (pinfunction "2_2") (pintype "bidirectional"))
      (node (ref "RS4") (pin "3") (pinfunction "3_3") (pintype "bidirectional"))
      (node (ref "RS5") (pin "1") (pinfunction "1_1") (pintype "bidirectional"))
      (node (ref "RS5") (pin "4") (pinfunction "4_4") (pintype "bidirectional"))
      (node (ref "RS6") (pin "5") (pinfunction "5_5") (pintype "bidirectional"))
      (node (ref "RS6") (pin "6") (pinfunction "6_6") (pintype "bidirectional"))
      (node (ref "RS6") (pin "7") (pinfunction "7_7") (pintype "bidirectional"))
      (node (ref "RS6") (pin "8") (pinfunction "8_8") (pintype "bidirectional"))
      (node (ref "RS7") (pin "1") (pinfunction "1_1") (pintype "bidirectional"))
      (node (ref "RS7") (pin "2") (pinfunction "2_2") (pintype "bidirectional"))
      (node (ref "RS7") (pin "3") (pinfunction "3_3") (pintype "bidirectional"))
      (node (ref "RS7") (pin "4") (pinfunction "4_4") (pintype "bidirectional"))
      (node (ref "RS8") (pin "5") (pinfunction "5_5") (pintype "bidirectional"))
      (node (ref "RS8") (pin "6") (pinfunction "6_6") (pintype "bidirectional"))
      (node (ref "RS8") (pin "7") (pinfunction "7_7") (pintype "bidirectional"))
      (node (ref "RS8") (pin "8") (pinfunction "8_8") (pintype "bidirectional"))
      (node (ref "T19") (pin "S") (pinfunction "S_S") (pintype "passive"))
      (node (ref "T3") (pin "S") (pinfunction "S_S") (pintype "passive"))
    )
    (net (code "18") (name "+5VREF") (class "Default")
      (node (ref "C102") (pin "2") (pinfunction "2_2") (pintype "passive"))
      (node (ref "C109") (pin "1") (pinfunction "1_1") (pintype "passive"))
      (node (ref "C113") (pin "1") (pinfunction "1_1") (pintype "passive"))
      (node (ref "C40") (pin "1") (pinfunction "1_1") (pintype "passive"))
      (node (ref "C48") (pin "1") (pinfunction "1_1") (pintype "passive"))
      (node (ref "C57") (pin "1") (pinfunction "1_1") (pintype "passive"))
      (node (ref "C59") (pin "2") (pinfunction "2_2") (pintype "passive"))
      (node (ref "C65") (pin "2") (pinfunction "2_2") (pintype "passive"))
      (node (ref "C67") (pin "2") (pinfunction "2_2") (pintype "passive"))
      (node (ref "C80") (pin "2") (pinfunction "2_2") (pintype "passive"))
      (node (ref "C81") (pin "+") (pinfunction "+_+") (pintype "passive"))
      (node (ref "C94") (pin "2") (pinfunction "2_2") (pintype "passive"))
      (node (ref "IC16") (pin "1") (pinfunction "+VS1_1") (pintype "bidirectional"))
      (node (ref "IC16") (pin "5") (pinfunction "+VS2_5") (pintype "bidirectional"))
      (node (ref "IC16") (pin "6") (pinfunction "+VS3_6") (pintype "bidirectional"))
      (node (ref "IC16") (pin "7") (pinfunction "+VS4_7") (pintype "bidirectional"))
      (node (ref "IC18") (pin "1") (pinfunction "+VS1_1") (pintype "bidirectional"))
      (node (ref "IC18") (pin "5") (pinfunction "+VS2_5") (pintype "bidirectional"))
      (node (ref "IC18") (pin "6") (pinfunction "+VS3_6") (pintype "bidirectional"))
      (node (ref "IC18") (pin "7") (pinfunction "+VS4_7") (pintype "bidirectional"))
      (node (ref "IC19") (pin "1") (pinfunction "+VS1_1") (pintype "bidirectional"))
      (node (ref "IC19") (pin "5") (pinfunction "+VS2_5") (pintype "bidirectional"))
      (node (ref "IC19") (pin "6") (pinfunction "+VS3_6") (pintype "bidirectional"))
      (node (ref "IC19") (pin "7") (pinfunction "+VS4_7") (pintype "bidirectional"))
      (node (ref "IC21") (pin "6") (pinfunction "OUT_6") (pintype "bidirectional"))
      (node (ref "IC22") (pin "1") (pinfunction "+VS1_1") (pintype "bidirectional"))
      (node (ref "IC22") (pin "5") (pinfunction "+VS2_5") (pintype "bidirectional"))
      (node (ref "IC22") (pin "6") (pinfunction "+VS3_6") (pintype "bidirectional"))
      (node (ref "IC22") (pin "7") (pinfunction "+VS4_7") (pintype "bidirectional"))
      (node (ref "IC24") (pin "3") (pinfunction "VCC_3") (pintype "bidirectional"))
      (node (ref "IC27") (pin "1") (pinfunction "+VS_1") (pintype "bidirectional"))
      (node (ref "IC28") (pin "1") (pinfunction "+VS_1") (pintype "bidirectional"))
      (node (ref "IC30") (pin "1") (pinfunction "+VS_1") (pintype "bidirectional"))
      (node (ref "IC33") (pin "1") (pinfunction "+VS1_1") (pintype "bidirectional"))
      (node (ref "IC33") (pin "5") (pinfunction "+VS2_5") (pintype "bidirectional"))
      (node (ref "IC33") (pin "6") (pinfunction "+VS3_6") (pintype "bidirectional"))
      (node (ref "IC33") (pin "7") (pinfunction "+VS4_7") (pintype "bidirectional"))
      (node (ref "IC34") (pin "1") (pinfunction "+VS_1") (pintype "bidirectional"))
      (node (ref "IC35") (pin "1") (pinfunction "+VS_1") (pintype "bidirectional"))
      (node (ref "R11") (pin "2") (pinfunction "2_2") (pintype "bidirectional"))
      (node (ref "R43") (pin "2") (pinfunction "2_2") (pintype "bidirectional"))
      (node (ref "R45") (pin "2") (pinfunction "2_2") (pintype "bidirectional"))
      (node (ref "T11") (pin "2") (pinfunction "C_2") (pintype "passive"))
      (node (ref "T11") (pin "4") (pinfunction "C2_4") (pintype "passive"))
    )
    (net (code "19") (name "+5VREF-FAILURE") (class "Default")
      (node (ref "IC24") (pin "2") (pinfunction "RESET/_2") (pintype "bidirectional"))
      (node (ref "IC4") (pin "53") (pinfunction "P2.6-CC6IO_53") (pintype "bidirectional"))
    )
    (net (code "20") (name "+5VSUPPLY-BOARD") (class "Default")
      (node (ref "C110") (pin "1") (pinfunction "1_1") (pintype "passive"))
      (node (ref "IC40") (pin "20") (pinfunction "VCC_20") (pintype "bidirectional"))
      (node (ref "IC41") (pin "5") (pinfunction "VCC_5") (pintype "bidirectional"))
      (node (ref "IC42") (pin "5") (pinfunction "VCC_5") (pintype "bidirectional"))
      (node (ref "IC43") (pin "5") (pinfunction "VCC_5") (pintype "bidirectional"))
      (node (ref "J1") (pin "14B") (pinfunction "14B_14B") (pintype "bidirectional"))
      (node (ref "J1") (pin "7B") (pinfunction "7B_7B") (pintype "bidirectional"))
      (node (ref "L22") (pin "2") (pinfunction "2_2") (pintype "bidirectional"))
      (node (ref "L46") (pin "2") (pinfunction "2_2") (pintype "bidirectional"))
    )
    (net (code "21") (name "+10VREF") (class "Default")
      (node (ref "C62") (pin "2") (pinfunction "2_2") (pintype "passive"))
      (node (ref "C69") (pin "2") (pinfunction "2_2") (pintype "passive"))
      (node (ref "C83") (pin "2") (pinfunction "2_2") (pintype "passive"))
      (node (ref "C85") (pin "+") (pinfunction "+_+") (pintype "passive"))
      (node (ref "IC15") (pin "2") (pinfunction "VCC_2") (pintype "bidirectional"))
      (node (ref "IC17") (pin "2") (pinfunction "VCC_2") (pintype "bidirectional"))
      (node (ref "IC23") (pin "6") (pinfunction "OUT_6") (pintype "bidirectional"))
      (node (ref "L27") (pin "2") (pinfunction "2_2") (pintype "bidirectional"))
      (node (ref "R66") (pin "1") (pinfunction "1_1") (pintype "bidirectional"))
      (node (ref "T12") (pin "2") (pinfunction "C_2") (pintype "passive"))
      (node (ref "T12") (pin "4") (pinfunction "C2_4") (pintype "passive"))
    )
    (net (code "22") (name "+10VREF-FAILURE") (class "Default")
      (node (ref "IC25") (pin "2") (pinfunction "RESET/_2") (pintype "bidirectional"))
      (node (ref "IC4") (pin "54") (pinfunction "P2.7-CC7IO_54") (pintype "bidirectional"))
    )
    (net (code "23") (name "+24V") (class "Default")
      (node (ref "C21") (pin "+") (pinfunction "+_+") (pintype "passive"))
      (node (ref "C46") (pin "2") (pinfunction "2_2") (pintype "passive"))
      (node (ref "C79") (pin "2") (pinfunction "2_2") (pintype "passive"))
      (node (ref "C82") (pin "2") (pinfunction "2_2") (pintype "passive"))
      (node (ref "D12") (pin "3") (pinfunction "K_3") (pintype "passive"))
      (node (ref "D15") (pin "K") (pinfunction "K_K") (pintype "passive"))
      (node (ref "D16") (pin "K") (pinfunction "K_K") (pintype "passive"))
      (node (ref "D7") (pin "A") (pinfunction "A_A") (pintype "passive"))
      (node (ref "J17") (pin "23") (pinfunction "P$23_23") (pintype "bidirectional"))
      (node (ref "L24") (pin "2") (pinfunction "2_2") (pintype "bidirectional"))
      (node (ref "L26") (pin "2") (pinfunction "2_2") (pintype "bidirectional"))
      (node (ref "L30") (pin "2") (pinfunction "2_2") (pintype "bidirectional"))
      (node (ref "R17") (pin "2") (pinfunction "2_2") (pintype "bidirectional"))
      (node (ref "R35") (pin "1") (pinfunction "1_1") (pintype "bidirectional"))
      (node (ref "R36") (pin "1") (pinfunction "1_1") (pintype "bidirectional"))
      (node (ref "R44") (pin "1") (pinfunction "1_1") (pintype "bidirectional"))
      (node (ref "R72") (pin "1") (pinfunction "1_1") (pintype "bidirectional"))
      (node (ref "T11") (pin "3") (pinfunction "E_3") (pintype "passive"))
      (node (ref "T12") (pin "3") (pinfunction "E_3") (pintype "passive"))
      (node (ref "V2") (pin "B1") (pinfunction "B1_B1") (pintype "bidirectional"))
    )
    (net (code "24") (name "+24VUTIL") (class "Default")
      (node (ref "D4") (pin "K") (pinfunction "K_K") (pintype "passive"))
      (node (ref "FU2") (pin "1") (pinfunction "1_1") (pintype "bidirectional"))
      (node (ref "JP9") (pin "1") (pinfunction "1_1") (pintype "passive"))
      (node (ref "L61") (pin "2") (pinfunction "2_2") (pintype "bidirectional"))
      (node (ref "L8") (pin "2") (pinfunction "2_2") (pintype "bidirectional"))
    )
    (net (code "30") (name "0VANA") (class "Default")
      (node (ref "BL1") (pin "1") (pinfunction "1_1") (pintype "bidirectional"))
      (node (ref "BL1") (pin "2") (pinfunction "2_2") (pintype "bidirectional"))
      (node (ref "BL1") (pin "3") (pinfunction "3_3") (pintype "bidirectional"))
      (node (ref "BL1") (pin "4") (pinfunction "4_4") (pintype "bidirectional"))
      (node (ref "BL2") (pin "1") (pinfunction "OUT1_1") (pintype "bidirectional"))
      (node (ref "BL2") (pin "2") (pinfunction "OUT2_2") (pintype "bidirectional"))
      (node (ref "BL3") (pin "1") (pinfunction "1_1") (pintype "bidirectional"))
      (node (ref "BL3") (pin "2") (pinfunction "2_2") (pintype "bidirectional"))
      (node (ref "BL3") (pin "3") (pinfunction "3_3") (pintype "bidirectional"))
      (node (ref "BL3") (pin "4") (pinfunction "4_4") (pintype "bidirectional"))
      (node (ref "BL4") (pin "1") (pinfunction "P$1_1") (pintype "bidirectional"))
      (node (ref "BL4") (pin "3") (pinfunction "P$4_3") (pintype "bidirectional"))
      (node (ref "BL4") (pin "4") (pinfunction "P$5_4") (pintype "bidirectional"))
      (node (ref "C102") (pin "1") (pinfunction "1_1") (pintype "passive"))
      (node (ref "C103") (pin "1") (pinfunction "1_1") (pintype "passive"))
      (node (ref "C104") (pin "1") (pinfunction "1_1") (pintype "passive"))
      (node (ref "C109") (pin "2") (pinfunction "2_2") (pintype "passive"))
      (node (ref "C11") (pin "1") (pinfunction "1_1") (pintype "passive"))
      (node (ref "C113") (pin "2") (pinfunction "2_2") (pintype "passive"))
      (node (ref "C126") (pin "1") (pinfunction "1_1") (pintype "passive"))
      (node (ref "C127") (pin "2") (pinfunction "2_2") (pintype "passive"))
      (node (ref "C130") (pin "1") (pinfunction "1_1") (pintype "passive"))
      (node (ref "C36") (pin "2") (pinfunction "2_2") (pintype "passive"))
      (node (ref "C40") (pin "2") (pinfunction "2_2") (pintype "passive"))
      (node (ref "C43") (pin "1") (pinfunction "1_1") (pintype "passive"))
      (node (ref "C45") (pin "1") (pinfunction "1_1") (pintype "passive"))
      (node (ref "C48") (pin "2") (pinfunction "2_2") (pintype "passive"))
      (node (ref "C51") (pin "2") (pinfunction "2_2") (pintype "passive"))
      (node (ref "C53") (pin "1") (pinfunction "1_1") (pintype "passive"))
      (node (ref "C57") (pin "2") (pinfunction "2_2") (pintype "passive"))
      (node (ref "C59") (pin "1") (pinfunction "1_1") (pintype "passive"))
      (node (ref "C60") (pin "1") (pinfunction "1_1") (pintype "passive"))
      (node (ref "C61") (pin "1") (pinfunction "1_1") (pintype "passive"))
      (node (ref "C62") (pin "1") (pinfunction "1_1") (pintype "passive"))
      (node (ref "C63") (pin "1") (pinfunction "1_1") (pintype "passive"))
      (node (ref "C64") (pin "1") (pinfunction "1_1") (pintype "passive"))
      (node (ref "C65") (pin "1") (pinfunction "1_1") (pintype "passive"))
      (node (ref "C66") (pin "1") (pinfunction "1_1") (pintype "passive"))
      (node (ref "C67") (pin "1") (pinfunction "1_1") (pintype "passive"))
      (node (ref "C68") (pin "1") (pinfunction "1_1") (pintype "passive"))
      (node (ref "C69") (pin "1") (pinfunction "1_1") (pintype "passive"))
      (node (ref "C7") (pin "-") (pinfunction "-_-") (pintype "passive"))
      (node (ref "C70") (pin "1") (pinfunction "1_1") (pintype "passive"))
      (node (ref "C71") (pin "1") (pinfunction "1_1") (pintype "passive"))
      (node (ref "C72") (pin "1") (pinfunction "1_1") (pintype "passive"))
      (node (ref "C73") (pin "1") (pinfunction "1_1") (pintype "passive"))
      (node (ref "C74") (pin "1") (pinfunction "1_1") (pintype "passive"))
      (node (ref "C76") (pin "1") (pinfunction "1_1") (pintype "passive"))
      (node (ref "C78") (pin "1") (pinfunction "1_1") (pintype "passive"))
      (node (ref "C79") (pin "1") (pinfunction "1_1") (pintype "passive"))
      (node (ref "C80") (pin "1") (pinfunction "1_1") (pintype "passive"))
      (node (ref "C81") (pin "-") (pinfunction "-_-") (pintype "passive"))
      (node (ref "C82") (pin "1") (pinfunction "1_1") (pintype "passive"))
      (node (ref "C83") (pin "1") (pinfunction "1_1") (pintype "passive"))
      (node (ref "C84") (pin "1") (pinfunction "1_1") (pintype "passive"))
      (node (ref "C85") (pin "-") (pinfunction "-_-") (pintype "passive"))
      (node (ref "C86") (pin "1") (pinfunction "1_1") (pintype "passive"))
      (node (ref "C9") (pin "1") (pinfunction "1_1") (pintype "passive"))
      (node (ref "C93") (pin "1") (pinfunction "1_1") (pintype "passive"))
      (node (ref "C94") (pin "1") (pinfunction "1_1") (pintype "passive"))
      (node (ref "C95") (pin "1") (pinfunction "1_1") (pintype "passive"))
      (node (ref "C96") (pin "1") (pinfunction "1_1") (pintype "passive"))
      (node (ref "C99") (pin "2") (pinfunction "2_2") (pintype "passive"))
      (node (ref "IC11") (pin "4") (pinfunction "GND_4") (pintype "bidirectional"))
      (node (ref "IC15") (pin "3") (pinfunction "GND_3") (pintype "bidirectional"))
      (node (ref "IC16") (pin "3") (pinfunction "GND1_3") (pintype "bidirectional"))
      (node (ref "IC16") (pin "4") (pinfunction "GND2_4") (pintype "bidirectional"))
      (node (ref "IC16") (pin "8") (pinfunction "GND4_8") (pintype "bidirectional"))
      (node (ref "IC17") (pin "3") (pinfunction "GND_3") (pintype "bidirectional"))
      (node (ref "IC18") (pin "3") (pinfunction "GND1_3") (pintype "bidirectional"))
      (node (ref "IC18") (pin "4") (pinfunction "GND2_4") (pintype "bidirectional"))
      (node (ref "IC18") (pin "8") (pinfunction "GND4_8") (pintype "bidirectional"))
      (node (ref "IC19") (pin "3") (pinfunction "GND1_3") (pintype "bidirectional"))
      (node (ref "IC19") (pin "4") (pinfunction "GND2_4") (pintype "bidirectional"))
      (node (ref "IC19") (pin "8") (pinfunction "GND4_8") (pintype "bidirectional"))
      (node (ref "IC21") (pin "4") (pinfunction "GND_4") (pintype "bidirectional"))
      (node (ref "IC22") (pin "3") (pinfunction "GND1_3") (pintype "bidirectional"))
      (node (ref "IC22") (pin "4") (pinfunction "GND2_4") (pintype "bidirectional"))
      (node (ref "IC22") (pin "8") (pinfunction "GND4_8") (pintype "bidirectional"))
      (node (ref "IC23") (pin "4") (pinfunction "GND_4") (pintype "bidirectional"))
      (node (ref "IC24") (pin "1") (pinfunction "VSS_1") (pintype "bidirectional"))
      (node (ref "IC25") (pin "1") (pinfunction "VSS_1") (pintype "bidirectional"))
      (node (ref "IC27") (pin "2") (pinfunction "GND_2") (pintype "bidirectional"))
      (node (ref "IC28") (pin "2") (pinfunction "GND_2") (pintype "bidirectional"))
      (node (ref "IC30") (pin "2") (pinfunction "GND_2") (pintype "bidirectional"))
      (node (ref "IC33") (pin "3") (pinfunction "GND1_3") (pintype "bidirectional"))
      (node (ref "IC33") (pin "4") (pinfunction "GND2_4") (pintype "bidirectional"))
      (node (ref "IC33") (pin "8") (pinfunction "GND4_8") (pintype "bidirectional"))
      (node (ref "IC34") (pin "2") (pinfunction "GND_2") (pintype "bidirectional"))
      (node (ref "IC35") (pin "2") (pinfunction "GND_2") (pintype "bidirectional"))
      (node (ref "IC4") (pin "38") (pinfunction "VAGND_38") (pintype "bidirectional"))
      (node (ref "J11") (pin "1") (pinfunction "1_1") (pintype "bidirectional"))
      (node (ref "J20") (pin "1") (pinfunction "1_1") (pintype "bidirectional"))
      (node (ref "J20") (pin "2") (pinfunction "2_2") (pintype "bidirectional"))
      (node (ref "J4") (pin "9") (pinfunction "9_9") (pintype "bidirectional"))
      (node (ref "J5") (pin "1") (pinfunction "1_1") (pintype "bidirectional"))
      (node (ref "J7") (pin "2") (pinfunction "2_2") (pintype "passive"))
      (node (ref "J7") (pin "26") (pinfunction "26_26") (pintype "passive"))
      (node (ref "JPL1") (pin "2") (pinfunction "2_2") (pintype "passive"))
      (node (ref "PT1") (pin "1") (pinfunction "1_1") (pintype "passive"))
      (node (ref "R15") (pin "1") (pinfunction "1_1") (pintype "bidirectional"))
      (node (ref "R40") (pin "2") (pinfunction "2_2") (pintype "bidirectional"))
      (node (ref "R55") (pin "1") (pinfunction "1_1") (pintype "bidirectional"))
      (node (ref "R57") (pin "1") (pinfunction "1_1") (pintype "bidirectional"))
      (node (ref "R59") (pin "1") (pinfunction "1_1") (pintype "bidirectional"))
      (node (ref "R62") (pin "1") (pinfunction "1_1") (pintype "bidirectional"))
      (node (ref "R67") (pin "1") (pinfunction "1_1") (pintype "bidirectional"))
      (node (ref "R70") (pin "1") (pinfunction "1_1") (pintype "bidirectional"))
    )
    (net (code "31") (name "A0") (class "Default")
      (node (ref "IC1") (pin "20") (pinfunction "A0_20") (pintype "input"))
      (node (ref "IC3") (pin "39") (pinfunction "LB/_39") (pintype "bidirectional"))
      (node (ref "IC4") (pin "118") (pinfunction "P1L.0-A0-AN16_118") (pintype "bidirectional"))
      (node (ref "J17") (pin "14") (pinfunction "P$14_14") (pintype "bidirectional"))
    )
    (net (code "32") (name "A1") (class "Default")
      (node (ref "IC1") (pin "18") (pinfunction "A1_18") (pintype "input"))
      (node (ref "IC3") (pin "1") (pinfunction "A0_1") (pintype "input"))
      (node (ref "IC4") (pin "119") (pinfunction "P1L.1-A1-AN17_119") (pintype "bidirectional"))
      (node (ref "IC7") (pin "25") (pinfunction "A0_25") (pintype "input"))
      (node (ref "J17") (pin "11") (pinfunction "P$11_11") (pintype "bidirectional"))
    )
    (net (code "33") (name "A2") (class "Default")
      (node (ref "IC1") (pin "17") (pinfunction "A2_17") (pintype "input"))
      (node (ref "IC3") (pin "2") (pinfunction "A1_2") (pintype "input"))
      (node (ref "IC4") (pin "120") (pinfunction "P1L.2-A2-AN18_120") (pintype "bidirectional"))
      (node (ref "IC7") (pin "24") (pinfunction "A1_24") (pintype "input"))
      (node (ref "J17") (pin "12") (pinfunction "P$12_12") (pintype "bidirectional"))
    )
    (net (code "34") (name "A3") (class "Default")
      (node (ref "IC3") (pin "3") (pinfunction "A2_3") (pintype "input"))
      (node (ref "IC4") (pin "121") (pinfunction "P1L.3-A3-AN19_121") (pintype "bidirectional"))
      (node (ref "IC7") (pin "23") (pinfunction "A2_23") (pintype "input"))
      (node (ref "J17") (pin "18") (pinfunction "P$18_18") (pintype "bidirectional"))
    )
    (net (code "35") (name "A4") (class "Default")
      (node (ref "IC3") (pin "4") (pinfunction "A3_4") (pintype "input"))
      (node (ref "IC4") (pin "122") (pinfunction "P1L.4-A4-AN20_122") (pintype "bidirectional"))
      (node (ref "IC7") (pin "22") (pinfunction "A3_22") (pintype "input"))
    )
    (net (code "36") (name "A5") (class "Default")
      (node (ref "IC3") (pin "5") (pinfunction "A4_5") (pintype "input"))
      (node (ref "IC4") (pin "123") (pinfunction "P1L.5-A5-AN21_123") (pintype "bidirectional"))
      (node (ref "IC7") (pin "21") (pinfunction "A4_21") (pintype "input"))
    )
    (net (code "37") (name "A6") (class "Default")
      (node (ref "IC3") (pin "18") (pinfunction "A5_18") (pintype "input"))
      (node (ref "IC4") (pin "124") (pinfunction "P1L.6-A6-AN22_124") (pintype "bidirectional"))
      (node (ref "IC7") (pin "20") (pinfunction "A5_20") (pintype "input"))
    )
    (net (code "38") (name "A7") (class "Default")
      (node (ref "IC3") (pin "19") (pinfunction "A6_19") (pintype "input"))
      (node (ref "IC4") (pin "125") (pinfunction "P1L.7-A7-AN23_125") (pintype "bidirectional"))
      (node (ref "IC7") (pin "19") (pinfunction "A6_19") (pintype "input"))
    )
    (net (code "39") (name "A8") (class "Default")
      (node (ref "IC3") (pin "20") (pinfunction "A7_20") (pintype "input"))
      (node (ref "IC4") (pin "128") (pinfunction "P1H.0-A8_128") (pintype "bidirectional"))
      (node (ref "IC7") (pin "18") (pinfunction "A7_18") (pintype "input"))
    )
    (net (code "40") (name "A9") (class "Default")
      (node (ref "IC3") (pin "21") (pinfunction "A8_21") (pintype "input"))
      (node (ref "IC4") (pin "129") (pinfunction "P1H.1-A9_129") (pintype "bidirectional"))
      (node (ref "IC7") (pin "8") (pinfunction "A8_8") (pintype "input"))
    )
    (net (code "41") (name "A10") (class "Default")
      (node (ref "IC3") (pin "22") (pinfunction "A9_22") (pintype "input"))
      (node (ref "IC4") (pin "130") (pinfunction "P1H.2-A10_130") (pintype "bidirectional"))
      (node (ref "IC7") (pin "7") (pinfunction "A9_7") (pintype "input"))
    )
    (net (code "42") (name "A11") (class "Default")
      (node (ref "IC3") (pin "23") (pinfunction "A10_23") (pintype "input"))
      (node (ref "IC4") (pin "131") (pinfunction "P1H.3-A11_131") (pintype "bidirectional"))
      (node (ref "IC7") (pin "6") (pinfunction "A10_6") (pintype "input"))
    )
    (net (code "43") (name "A12") (class "Default")
      (node (ref "IC3") (pin "24") (pinfunction "A11_24") (pintype "input"))
      (node (ref "IC4") (pin "132") (pinfunction "P1H.4-A12-CC24I_132") (pintype "bidirectional"))
      (node (ref "IC7") (pin "5") (pinfunction "A11_5") (pintype "input"))
    )
    (net (code "44") (name "A13") (class "Default")
      (node (ref "IC3") (pin "25") (pinfunction "A12_25") (pintype "input"))
      (node (ref "IC4") (pin "133") (pinfunction "P1H.5-A13-CC25I_133") (pintype "bidirectional"))
      (node (ref "IC7") (pin "4") (pinfunction "A12_4") (pintype "input"))
    )
    (net (code "45") (name "A14") (class "Default")
      (node (ref "IC3") (pin "26") (pinfunction "A13_26") (pintype "input"))
      (node (ref "IC4") (pin "134") (pinfunction "P1H.6-A14-CC26I_134") (pintype "bidirectional"))
      (node (ref "IC7") (pin "3") (pinfunction "A13_3") (pintype "input"))
    )
    (net (code "46") (name "A15") (class "Default")
      (node (ref "IC3") (pin "27") (pinfunction "A14_27") (pintype "input"))
      (node (ref "IC4") (pin "135") (pinfunction "P1H.7-A15-CC27I_135") (pintype "bidirectional"))
      (node (ref "IC7") (pin "2") (pinfunction "A14_2") (pintype "input"))
    )
    (net (code "47") (name "A16") (class "Default")
      (node (ref "IC3") (pin "42") (pinfunction "A15_42") (pintype "input"))
      (node (ref "IC4") (pin "85") (pinfunction "P4.0-A16_85") (pintype "bidirectional"))
      (node (ref "IC7") (pin "1") (pinfunction "A15_1") (pintype "input"))
    )
    (net (code "48") (name "A17") (class "Default")
      (node (ref "IC3") (pin "43") (pinfunction "A16_43") (pintype "input"))
      (node (ref "IC4") (pin "86") (pinfunction "P4.1-A17_86") (pintype "bidirectional"))
      (node (ref "IC7") (pin "48") (pinfunction "A16_48") (pintype "input"))
    )
    (net (code "49") (name "A18") (class "Default")
      (node (ref "IC3") (pin "44") (pinfunction "A17_44") (pintype "input"))
      (node (ref "IC4") (pin "87") (pinfunction "P4.2-A18_87") (pintype "bidirectional"))
      (node (ref "IC7") (pin "17") (pinfunction "A17_17") (pintype "input"))
    )
    (net (code "50") (name "A19") (class "Default")
      (node (ref "IC4") (pin "88") (pinfunction "P4.3-A19_88") (pintype "bidirectional"))
      (node (ref "IC7") (pin "16") (pinfunction "A18_16") (pintype "input"))
    )
    (net (code "51") (name "A23") (class "Default")
      (node (ref "IC38") (pin "1") (pinfunction "B_1") (pintype "input"))
      (node (ref "IC4") (pin "92") (pinfunction "P4.7-A23-CAN2_TXD-SDA_92") (pintype "bidirectional"))
      (node (ref "IC5") (pin "1") (pinfunction "B_1") (pintype "input"))
    )
    (net (code "52") (name "AC_PRESENCE") (class "Default")
      (node (ref "IC4") (pin "9") (pinfunction "P8.0-XPOUT0-CC16IO_9") (pintype "bidirectional"))
      (node (ref "IC40") (pin "5") (pinfunction "A3_5") (pintype "bidirectional"))
    )
    (net (code "53") (name "ALARM-INHIB") (class "Default")
      (node (ref "C14") (pin "8") (pinfunction "8_8") (pintype "passive"))
      (node (ref "IC4") (pin "73") (pinfunction "P3.6-T3IN_73") (pintype "bidirectional"))
      (node (ref "J1") (pin "3B") (pinfunction "3B_3B") (pintype "bidirectional"))
      (node (ref "RS1") (pin "5") (pinfunction "5_5") (pintype "bidirectional"))
    )
    (net (code "54") (name "BHE") (class "Default")
      (node (ref "IC3") (pin "40") (pinfunction "UB/_40") (pintype "bidirectional"))
      (node (ref "IC4") (pin "79") (pinfunction "P3.12-BHE/-WRH/_79") (pintype "bidirectional"))
    )
    (net (code "55") (name "BRAKE") (class "Default")
      (node (ref "IC4") (pin "48") (pinfunction "P2.1-CC1IO_48") (pintype "bidirectional"))
      (node (ref "L32") (pin "2") (pinfunction "2_2") (pintype "bidirectional"))
    )
    (net (code "56") (name "BRAKE{slash}") (class "Default")
      (node (ref "C56") (pin "6") (pinfunction "6_6") (pintype "passive"))
      (node (ref "J4") (pin "4") (pinfunction "4_4") (pintype "bidirectional"))
      (node (ref "L32") (pin "1") (pinfunction "1_1") (pintype "bidirectional"))
    )
    (net (code "57") (name "BUSY-AFF") (class "Default")
      (node (ref "IC4") (pin "60") (pinfunction "P2.11-CC11IOIO-EX3IN_60") (pintype "bidirectional"))
      (node (ref "J17") (pin "8") (pinfunction "P$8_8") (pintype "bidirectional"))
    )
    (net (code "58") (name "BUSY-ME1") (class "Default")
      (node (ref "IC13") (pin "7") (pinfunction "R-B1/_7") (pintype "bidirectional"))
      (node (ref "IC4") (pin "57") (pinfunction "P2.8-CC8IO-EX0IN_57") (pintype "bidirectional"))
      (node (ref "RS7") (pin "8") (pinfunction "8_8") (pintype "bidirectional"))
    )
    (net (code "59") (name "BUSY-ME2") (class "Default")
      (node (ref "IC4") (pin "58") (pinfunction "P2.9-CC9IO-EX1IN_58") (pintype "bidirectional"))
      (node (ref "IC7") (pin "15") (pinfunction "RY-BY/_15") (pintype "output"))
      (node (ref "RS7") (pin "7") (pinfunction "7_7") (pintype "bidirectional"))
    )
    (net (code "60") (name "CABLE-SHIELD") (class "Default")
      (node (ref "J3") (pin "1") (pinfunction "1_1") (pintype "bidirectional"))
      (node (ref "J6") (pin "1") (pinfunction "1_1") (pintype "bidirectional"))
      (node (ref "JP1") (pin "2") (pinfunction "2_2") (pintype "passive"))
    )
    (net (code "61") (name "CD-O2") (class "Default")
      (node (ref "IC4") (pin "21") (pinfunction "P7.2-POUT2_21") (pintype "bidirectional"))
      (node (ref "R8") (pin "2") (pinfunction "2_2") (pintype "bidirectional"))
      (node (ref "T20") (pin "G") (pinfunction "GATE_G") (pintype "passive"))
    )
    (net (code "62") (name "CD-VALVE") (class "Default")
      (node (ref "IC4") (pin "20") (pinfunction "P7.1-POUT1_20") (pintype "bidirectional"))
      (node (ref "R9") (pin "2") (pinfunction "2_2") (pintype "bidirectional"))
      (node (ref "T21") (pin "G") (pinfunction "GATE_G") (pintype "passive"))
    )
    (net (code "63") (name "CE-RTC1") (class "Default")
      (node (ref "IC10") (pin "12") (pinfunction "CE_12") (pintype "bidirectional"))
      (node (ref "IC14") (pin "8") (pinfunction "1Q5_8") (pintype "bidirectional"))
    )
    (net (code "64") (name "CE-SPI-PIC") (class "Default")
      (node (ref "IC14") (pin "16") (pinfunction "2Q3_16") (pintype "bidirectional"))
      (node (ref "L5") (pin "1") (pinfunction "1_1") (pintype "bidirectional"))
    )
    (net (code "65") (name "CE-SPI-PIC-IC44") (class "Default")
      (node (ref "IC14") (pin "20") (pinfunction "2Q6_20") (pintype "bidirectional"))
      (node (ref "IC44") (pin "4") (pinfunction "OE_4") (pintype "bidirectional"))
    )
    (net (code "66") (name "CE-SPI-USB") (class "Default")
      (node (ref "IC14") (pin "14") (pinfunction "2Q2_14") (pintype "bidirectional"))
      (node (ref "L4") (pin "1") (pinfunction "1_1") (pintype "bidirectional"))
    )
    (net (code "67") (name "CE{slash}-EEP") (class "Default")
      (node (ref "IC14") (pin "6") (pinfunction "1Q4_6") (pintype "bidirectional"))
      (node (ref "IC32") (pin "1") (pinfunction "CS/_1") (pintype "input"))
    )
    (net (code "68") (name "CE{slash}-FLOW-EXP-SENS") (class "Default")
      (node (ref "IC14") (pin "19") (pinfunction "2Q5_19") (pintype "bidirectional"))
      (node (ref "IC35") (pin "6") (pinfunction "ISS_6") (pintype "bidirectional"))
    )
    (net (code "69") (name "CE{slash}-FLOW-INSP-SENS") (class "Default")
      (node (ref "IC14") (pin "17") (pinfunction "2Q4_17") (pintype "bidirectional"))
      (node (ref "IC34") (pin "6") (pinfunction "ISS_6") (pintype "bidirectional"))
    )
    (net (code "70") (name "CE{slash}-INT-PRES-SENS") (class "Default")
      (node (ref "IC14") (pin "11") (pinfunction "1Q7_11") (pintype "bidirectional"))
      (node (ref "IC27") (pin "6") (pinfunction "ISS_6") (pintype "bidirectional"))
    )
    (net (code "71") (name "CE{slash}-PROX-PRES-SENS") (class "Default")
      (node (ref "IC14") (pin "12") (pinfunction "1Q8_12") (pintype "bidirectional"))
      (node (ref "IC30") (pin "6") (pinfunction "ISS_6") (pintype "bidirectional"))
    )
    (net (code "72") (name "CE{slash}-RTC2") (class "Default")
      (node (ref "IC14") (pin "9") (pinfunction "1Q6_9") (pintype "bidirectional"))
      (node (ref "IC31") (pin "15") (pinfunction "E/_15") (pintype "bidirectional"))
    )
    (net (code "73") (name "CE{slash}-VALV-PRES-SENS") (class "Default")
      (node (ref "IC14") (pin "13") (pinfunction "2Q1_13") (pintype "bidirectional"))
      (node (ref "IC28") (pin "6") (pinfunction "ISS_6") (pintype "bidirectional"))
    )
    (net (code "74") (name "CMD_ALE1") (class "Default")
      (node (ref "IC2") (pin "17") (pinfunction "2B4_17") (pintype "bidirectional"))
      (node (ref "IC4") (pin "81") (pinfunction "P3.15-CLKOUT_81") (pintype "bidirectional"))
    )
    (net (code "75") (name "CMD_ME1") (class "Default")
      (node (ref "IC2") (pin "19") (pinfunction "2B5_19") (pintype "bidirectional"))
      (node (ref "IC4") (pin "64") (pinfunction "P2.15-CC15IOIO-EX7IN-T7IN_64") (pintype "bidirectional"))
    )
    (net (code "76") (name "COM1") (class "Default")
      (node (ref "IC4") (pin "65") (pinfunction "P3.0-T0IN_65") (pintype "bidirectional"))
      (node (ref "J1") (pin "21B") (pinfunction "21B_21B") (pintype "bidirectional"))
    )
    (net (code "77") (name "COM2") (class "Default")
      (node (ref "IC4") (pin "66") (pinfunction "P3.1-T6OUT_66") (pintype "bidirectional"))
      (node (ref "J1") (pin "20B") (pinfunction "20B_20B") (pintype "bidirectional"))
    )
    (net (code "78") (name "COM3") (class "Default")
      (node (ref "IC4") (pin "67") (pinfunction "P3.2-CAPIN_67") (pintype "bidirectional"))
      (node (ref "J1") (pin "18B") (pinfunction "18B_18B") (pintype "bidirectional"))
    )
    (net (code "79") (name "CON-FIO2-MEAS") (class "Default")
      (node (ref "C53") (pin "2") (pinfunction "2_2") (pintype "passive"))
      (node (ref "IC11") (pin "3") (pinfunction "+_3") (pintype "input"))
      (node (ref "L21") (pin "2") (pinfunction "2_2") (pintype "bidirectional"))
      (node (ref "R59") (pin "2") (pinfunction "2_2") (pintype "bidirectional"))
    )
    (net (code "80") (name "CONS-VIT") (class "Default")
      (node (ref "IC4") (pin "19") (pinfunction "P7.0-POUT0_19") (pintype "bidirectional"))
      (node (ref "L33") (pin "2") (pinfunction "2_2") (pintype "bidirectional"))
    )
    (net (code "81") (name "CS0{slash}") (class "Default")
      (node (ref "IC4") (pin "1") (pinfunction "P6.0-CS0/_1") (pintype "bidirectional"))
      (node (ref "IC5") (pin "2") (pinfunction "A_2") (pintype "input"))
    )
    (net (code "82") (name "CS1{slash}") (class "Default")
      (node (ref "IC4") (pin "2") (pinfunction "P6.1-CS1/_2") (pintype "bidirectional"))
      (node (ref "IC7") (pin "26") (pinfunction "CE/_26") (pintype "input"))
    )
    (net (code "83") (name "CS2{slash}") (class "Default")
      (node (ref "IC3") (pin "6") (pinfunction "CS/_6") (pintype "bidirectional"))
      (node (ref "IC4") (pin "3") (pinfunction "P6.2-CS2/_3") (pintype "bidirectional"))
    )
    (net (code "84") (name "CS3{slash}") (class "Default")
      (node (ref "IC1") (pin "62") (pinfunction "CS2/_62") (pintype "input"))
      (node (ref "IC4") (pin "4") (pinfunction "P6.3-CS3/_4") (pintype "bidirectional"))
    )
    (net (code "85") (name "CS4{slash}") (class "Default")
      (node (ref "IC4") (pin "5") (pinfunction "P6.4-CS4/_5") (pintype "bidirectional"))
      (node (ref "J17") (pin "20") (pinfunction "P$20_20") (pintype "bidirectional"))
    )
    (net (code "86") (name "D0") (class "Default")
      (node (ref "IC1") (pin "42") (pinfunction "D0_42") (pintype "bidirectional"))
      (node (ref "IC14") (pin "47") (pinfunction "1D1_47") (pintype "bidirectional"))
      (node (ref "IC2") (pin "2") (pinfunction "1B1_2") (pintype "bidirectional"))
      (node (ref "IC3") (pin "7") (pinfunction "I/O1_7") (pintype "bidirectional"))
      (node (ref "IC4") (pin "100") (pinfunction "P0L.0-D0_100") (pintype "bidirectional"))
      (node (ref "IC7") (pin "29") (pinfunction "D0_29") (pintype "bidirectional"))
      (node (ref "J17") (pin "9") (pinfunction "P$9_9") (pintype "bidirectional"))
      (node (ref "RS2") (pin "8") (pinfunction "8_8") (pintype "bidirectional"))
    )
    (net (code "87") (name "D1") (class "Default")
      (node (ref "IC1") (pin "43") (pinfunction "D1_43") (pintype "bidirectional"))
      (node (ref "IC14") (pin "46") (pinfunction "1D2_46") (pintype "bidirectional"))
      (node (ref "IC2") (pin "3") (pinfunction "1B2_3") (pintype "bidirectional"))
      (node (ref "IC3") (pin "8") (pinfunction "I/O2_8") (pintype "bidirectional"))
      (node (ref "IC4") (pin "101") (pinfunction "P0L.1-D1_101") (pintype "bidirectional"))
      (node (ref "IC7") (pin "31") (pinfunction "D1_31") (pintype "bidirectional"))
      (node (ref "J17") (pin "6") (pinfunction "P$6_6") (pintype "bidirectional"))
      (node (ref "RS2") (pin "7") (pinfunction "7_7") (pintype "bidirectional"))
    )
    (net (code "88") (name "D2") (class "Default")
      (node (ref "IC1") (pin "45") (pinfunction "D2_45") (pintype "bidirectional"))
      (node (ref "IC14") (pin "44") (pinfunction "1D3_44") (pintype "bidirectional"))
      (node (ref "IC2") (pin "5") (pinfunction "1B3_5") (pintype "bidirectional"))
      (node (ref "IC3") (pin "9") (pinfunction "I/O3_9") (pintype "bidirectional"))
      (node (ref "IC4") (pin "102") (pinfunction "P0L.2-D2_102") (pintype "bidirectional"))
      (node (ref "IC7") (pin "33") (pinfunction "D2_33") (pintype "bidirectional"))
      (node (ref "J17") (pin "7") (pinfunction "P$7_7") (pintype "bidirectional"))
      (node (ref "RS2") (pin "6") (pinfunction "6_6") (pintype "bidirectional"))
    )
    (net (code "89") (name "D3") (class "Default")
      (node (ref "IC1") (pin "46") (pinfunction "D3_46") (pintype "bidirectional"))
      (node (ref "IC14") (pin "43") (pinfunction "1D4_43") (pintype "bidirectional"))
      (node (ref "IC2") (pin "6") (pinfunction "1B4_6") (pintype "bidirectional"))
      (node (ref "IC3") (pin "10") (pinfunction "I/O4_10") (pintype "bidirectional"))
      (node (ref "IC4") (pin "103") (pinfunction "P0L.3-D3_103") (pintype "bidirectional"))
      (node (ref "IC7") (pin "35") (pinfunction "D3_35") (pintype "bidirectional"))
      (node (ref "J17") (pin "17") (pinfunction "P$17_17") (pintype "bidirectional"))
      (node (ref "RS2") (pin "5") (pinfunction "5_5") (pintype "bidirectional"))
    )
    (net (code "90") (name "D4") (class "Default")
      (node (ref "IC1") (pin "48") (pinfunction "D4_48") (pintype "bidirectional"))
      (node (ref "IC14") (pin "41") (pinfunction "1D5_41") (pintype "bidirectional"))
      (node (ref "IC2") (pin "8") (pinfunction "1B5_8") (pintype "bidirectional"))
      (node (ref "IC3") (pin "13") (pinfunction "I/O5_13") (pintype "bidirectional"))
      (node (ref "IC4") (pin "104") (pinfunction "P0L.4-D4_104") (pintype "bidirectional"))
      (node (ref "IC7") (pin "38") (pinfunction "D4_38") (pintype "bidirectional"))
      (node (ref "J17") (pin "13") (pinfunction "P$13_13") (pintype "bidirectional"))
      (node (ref "RS3") (pin "8") (pinfunction "8_8") (pintype "bidirectional"))
    )
    (net (code "91") (name "D5") (class "Default")
      (node (ref "IC1") (pin "50") (pinfunction "D5_50") (pintype "bidirectional"))
      (node (ref "IC14") (pin "40") (pinfunction "1D6_40") (pintype "bidirectional"))
      (node (ref "IC2") (pin "9") (pinfunction "1B6_9") (pintype "bidirectional"))
      (node (ref "IC3") (pin "14") (pinfunction "I/O6_14") (pintype "bidirectional"))
      (node (ref "IC4") (pin "105") (pinfunction "P0L.5-D5_105") (pintype "bidirectional"))
      (node (ref "IC7") (pin "40") (pinfunction "D5_40") (pintype "bidirectional"))
      (node (ref "J17") (pin "15") (pinfunction "P$15_15") (pintype "bidirectional"))
      (node (ref "RS3") (pin "7") (pinfunction "7_7") (pintype "bidirectional"))
    )
    (net (code "92") (name "D6") (class "Default")
      (node (ref "IC1") (pin "51") (pinfunction "D6_51") (pintype "bidirectional"))
      (node (ref "IC14") (pin "38") (pinfunction "1D7_38") (pintype "bidirectional"))
      (node (ref "IC2") (pin "11") (pinfunction "1B7_11") (pintype "bidirectional"))
      (node (ref "IC3") (pin "15") (pinfunction "I/O7_15") (pintype "bidirectional"))
      (node (ref "IC4") (pin "106") (pinfunction "P0L.6-D6_106") (pintype "bidirectional"))
      (node (ref "IC7") (pin "42") (pinfunction "D6_42") (pintype "bidirectional"))
      (node (ref "J17") (pin "10") (pinfunction "P$10_10") (pintype "bidirectional"))
      (node (ref "RS3") (pin "6") (pinfunction "6_6") (pintype "bidirectional"))
    )
    (net (code "93") (name "D7") (class "Default")
      (node (ref "IC1") (pin "52") (pinfunction "D7_52") (pintype "bidirectional"))
      (node (ref "IC14") (pin "37") (pinfunction "1D8_37") (pintype "bidirectional"))
      (node (ref "IC2") (pin "12") (pinfunction "1B8_12") (pintype "bidirectional"))
      (node (ref "IC3") (pin "16") (pinfunction "I/O8_16") (pintype "bidirectional"))
      (node (ref "IC4") (pin "107") (pinfunction "P0L.7-D7_107") (pintype "bidirectional"))
      (node (ref "IC7") (pin "44") (pinfunction "D7_44") (pintype "bidirectional"))
      (node (ref "J17") (pin "5") (pinfunction "P$5_5") (pintype "bidirectional"))
      (node (ref "RS3") (pin "5") (pinfunction "5_5") (pintype "bidirectional"))
    )
    (net (code "94") (name "D8") (class "Default")
      (node (ref "IC14") (pin "36") (pinfunction "2D1_36") (pintype "bidirectional"))
      (node (ref "IC3") (pin "29") (pinfunction "I/O9_29") (pintype "bidirectional"))
      (node (ref "IC4") (pin "108") (pinfunction "P0H.0-D8_108") (pintype "bidirectional"))
      (node (ref "IC7") (pin "30") (pinfunction "D8_30") (pintype "bidirectional"))
      (node (ref "RS4") (pin "8") (pinfunction "8_8") (pintype "bidirectional"))
    )
    (net (code "95") (name "D9") (class "Default")
      (node (ref "IC14") (pin "35") (pinfunction "2D2_35") (pintype "bidirectional"))
      (node (ref "IC3") (pin "30") (pinfunction "I/O10_30") (pintype "bidirectional"))
      (node (ref "IC4") (pin "111") (pinfunction "P0H.1-D9_111") (pintype "bidirectional"))
      (node (ref "IC7") (pin "32") (pinfunction "D9_32") (pintype "bidirectional"))
      (node (ref "RS4") (pin "7") (pinfunction "7_7") (pintype "bidirectional"))
    )
    (net (code "96") (name "D10") (class "Default")
      (node (ref "IC14") (pin "33") (pinfunction "2D3_33") (pintype "bidirectional"))
      (node (ref "IC3") (pin "31") (pinfunction "I/O11_31") (pintype "bidirectional"))
      (node (ref "IC4") (pin "112") (pinfunction "P0H.2-D10_112") (pintype "bidirectional"))
      (node (ref "IC7") (pin "34") (pinfunction "D10_34") (pintype "bidirectional"))
      (node (ref "RS4") (pin "6") (pinfunction "6_6") (pintype "bidirectional"))
    )
    (net (code "97") (name "D11") (class "Default")
      (node (ref "IC14") (pin "32") (pinfunction "2D4_32") (pintype "bidirectional"))
      (node (ref "IC3") (pin "32") (pinfunction "I/O12_32") (pintype "bidirectional"))
      (node (ref "IC4") (pin "113") (pinfunction "P0H.3-D11_113") (pintype "bidirectional"))
      (node (ref "IC7") (pin "36") (pinfunction "D11_36") (pintype "bidirectional"))
      (node (ref "RS4") (pin "5") (pinfunction "5_5") (pintype "bidirectional"))
    )
    (net (code "98") (name "D12") (class "Default")
      (node (ref "IC14") (pin "30") (pinfunction "2D5_30") (pintype "bidirectional"))
      (node (ref "IC3") (pin "35") (pinfunction "I/O13_35") (pintype "bidirectional"))
      (node (ref "IC4") (pin "114") (pinfunction "P0H.4-D12_114") (pintype "bidirectional"))
      (node (ref "IC7") (pin "39") (pinfunction "D12_39") (pintype "bidirectional"))
      (node (ref "RS5") (pin "8") (pinfunction "8_8") (pintype "bidirectional"))
    )
    (net (code "99") (name "D13") (class "Default")
      (node (ref "IC14") (pin "29") (pinfunction "2D6_29") (pintype "bidirectional"))
      (node (ref "IC3") (pin "36") (pinfunction "I/O14_36") (pintype "bidirectional"))
      (node (ref "IC4") (pin "115") (pinfunction "P0H.5-D13_115") (pintype "bidirectional"))
      (node (ref "IC7") (pin "41") (pinfunction "D13_41") (pintype "bidirectional"))
      (node (ref "RS5") (pin "7") (pinfunction "7_7") (pintype "bidirectional"))
    )
    (net (code "100") (name "D14") (class "Default")
      (node (ref "IC14") (pin "27") (pinfunction "2D7_27") (pintype "bidirectional"))
      (node (ref "IC3") (pin "37") (pinfunction "I/O15_37") (pintype "bidirectional"))
      (node (ref "IC4") (pin "116") (pinfunction "P0H.6-D14_116") (pintype "bidirectional"))
      (node (ref "IC7") (pin "43") (pinfunction "D14_43") (pintype "bidirectional"))
      (node (ref "RS5") (pin "6") (pinfunction "6_6") (pintype "bidirectional"))
    )
    (net (code "101") (name "D15") (class "Default")
      (node (ref "IC14") (pin "26") (pinfunction "2D8_26") (pintype "bidirectional"))
      (node (ref "IC3") (pin "38") (pinfunction "I/O16_38") (pintype "bidirectional"))
      (node (ref "IC4") (pin "117") (pinfunction "P0H.7-D15_117") (pintype "bidirectional"))
      (node (ref "IC7") (pin "45") (pinfunction "D15_45") (pintype "bidirectional"))
      (node (ref "RS5") (pin "5") (pinfunction "5_5") (pintype "bidirectional"))
    )
    (net (code "102") (name "DEF-TURB") (class "Default")
      (node (ref "IC4") (pin "49") (pinfunction "P2.2-CC2IO_49") (pintype "bidirectional"))
      (node (ref "L31") (pin "2") (pinfunction "2_2") (pintype "bidirectional"))
    )
    (net (code "103") (name "ENABLE") (class "Default")
      (node (ref "C56") (pin "8") (pinfunction "8_8") (pintype "passive"))
      (node (ref "J4") (pin "2") (pinfunction "2_2") (pintype "bidirectional"))
      (node (ref "L29") (pin "1") (pinfunction "1_1") (pintype "bidirectional"))
    )
    (net (code "104") (name "ENABLE-TURB") (class "Default")
      (node (ref "IC4") (pin "50") (pinfunction "P2.3-CC3IO_50") (pintype "bidirectional"))
      (node (ref "L29") (pin "2") (pinfunction "2_2") (pintype "bidirectional"))
    )
    (net (code "105") (name "EXHALATION-VALVE") (class "Default")
      (node (ref "D16") (pin "A") (pinfunction "A_A") (pintype "passive"))
      (node (ref "L23") (pin "2") (pinfunction "2_2") (pintype "bidirectional"))
      (node (ref "T21") (pin "D") (pinfunction "DRAIN_D") (pintype "passive"))
      (node (ref "V2") (pin "B2") (pinfunction "B2_B2") (pintype "bidirectional"))
    )
    (net (code "106") (name "FAULT{slash}") (class "Default")
      (node (ref "C56") (pin "7") (pinfunction "7_7") (pintype "passive"))
      (node (ref "J4") (pin "3") (pinfunction "3_3") (pintype "bidirectional"))
      (node (ref "L31") (pin "1") (pinfunction "1_1") (pintype "bidirectional"))
    )
    (net (code "107") (name "FIO2-MEAS") (class "Default")
      (node (ref "C54") (pin "2") (pinfunction "2_2") (pintype "passive"))
      (node (ref "C84") (pin "2") (pinfunction "2_2") (pintype "passive"))
      (node (ref "D2") (pin "1") (pinfunction "3_1") (pintype "bidirectional"))
      (node (ref "IC11") (pin "1") (pinfunction "OUT_1") (pintype "output"))
      (node (ref "IC4") (pin "32") (pinfunction "P5.5-AN5_32") (pintype "bidirectional"))
      (node (ref "R58") (pin "2") (pinfunction "2_2") (pintype "bidirectional"))
    )
    (net (code "108") (name "FLOW-TEMP") (class "Default")
      (node (ref "C76") (pin "2") (pinfunction "2_2") (pintype "passive"))
      (node (ref "D5") (pin "4") (pinfunction "4_4") (pintype "bidirectional"))
      (node (ref "IC4") (pin "43") (pinfunction "P5.14-AN14-T4EUD_43") (pintype "bidirectional"))
      (node (ref "L37") (pin "2") (pinfunction "2_2") (pintype "bidirectional"))
      (node (ref "R43") (pin "1") (pinfunction "1_1") (pintype "bidirectional"))
    )
    (net (code "109") (name "GND") (class "Default")
      (node (ref "C1") (pin "2") (pinfunction "2_2") (pintype "passive"))
      (node (ref "C10") (pin "2") (pinfunction "2_2") (pintype "passive"))
      (node (ref "C100") (pin "1") (pinfunction "1_1") (pintype "passive"))
      (node (ref "C100") (pin "2") (pinfunction "2_2") (pintype "passive"))
      (node (ref "C100") (pin "3") (pinfunction "3_3") (pintype "passive"))
      (node (ref "C100") (pin "4") (pinfunction "4_4") (pintype "passive"))
      (node (ref "C101") (pin "1") (pinfunction "1_1") (pintype "passive"))
      (node (ref "C105") (pin "1") (pinfunction "1_1") (pintype "passive"))
      (node (ref "C106") (pin "-") (pinfunction "-_-") (pintype "passive"))
      (node (ref "C107") (pin "1") (pinfunction "1_1") (pintype "passive"))
      (node (ref "C108") (pin "-") (pinfunction "-_-") (pintype "passive"))
      (node (ref "C110") (pin "2") (pinfunction "2_2") (pintype "passive"))
      (node (ref "C111") (pin "1") (pinfunction "1_1") (pintype "passive"))
      (node (ref "C111") (pin "2") (pinfunction "2_2") (pintype "passive"))
      (node (ref "C111") (pin "3") (pinfunction "3_3") (pintype "passive"))
      (node (ref "C111") (pin "4") (pinfunction "4_4") (pintype "passive"))
      (node (ref "C114") (pin "1") (pinfunction "1_1") (pintype "passive"))
      (node (ref "C115") (pin "1") (pinfunction "1_1") (pintype "passive"))
      (node (ref "C116") (pin "1") (pinfunction "1_1") (pintype "passive"))
      (node (ref "C117") (pin "-") (pinfunction "-_-") (pintype "passive"))
      (node (ref "C12") (pin "2") (pinfunction "2_2") (pintype "passive"))
      (node (ref "C120") (pin "1") (pinfunction "1_1") (pintype "passive"))
      (node (ref "C121") (pin "2") (pinfunction "2_2") (pintype "passive"))
      (node (ref "C122") (pin "1") (pinfunction "1_1") (pintype "passive"))
      (node (ref "C123") (pin "2") (pinfunction "2_2") (pintype "passive"))
      (node (ref "C124") (pin "1") (pinfunction "1_1") (pintype "passive"))
      (node (ref "C13") (pin "2") (pinfunction "2_2") (pintype "passive"))
      (node (ref "C14") (pin "1") (pinfunction "1_1") (pintype "passive"))
      (node (ref "C14") (pin "2") (pinfunction "2_2") (pintype "passive"))
      (node (ref "C14") (pin "3") (pinfunction "3_3") (pintype "passive"))
      (node (ref "C14") (pin "4") (pinfunction "4_4") (pintype "passive"))
      (node (ref "C140") (pin "1") (pinfunction "1_1") (pintype "passive"))
      (node (ref "C15") (pin "2") (pinfunction "2_2") (pintype "passive"))
      (node (ref "C16") (pin "1") (pinfunction "1_1") (pintype "passive"))
      (node (ref "C17") (pin "1") (pinfunction "1_1") (pintype "passive"))
      (node (ref "C17") (pin "2") (pinfunction "2_2") (pintype "passive"))
      (node (ref "C17") (pin "3") (pinfunction "3_3") (pintype "passive"))
      (node (ref "C17") (pin "4") (pinfunction "4_4") (pintype "passive"))
      (node (ref "C18") (pin "1") (pinfunction "1_1") (pintype "passive"))
      (node (ref "C18") (pin "2") (pinfunction "2_2") (pintype "passive"))
      (node (ref "C18") (pin "3") (pinfunction "3_3") (pintype "passive"))
      (node (ref "C18") (pin "4") (pinfunction "4_4") (pintype "passive"))
      (node (ref "C19") (pin "-") (pinfunction "-_-") (pintype "passive"))
      (node (ref "C2") (pin "2") (pinfunction "2_2") (pintype "passive"))
      (node (ref "C20") (pin "2") (pinfunction "2_2") (pintype "passive"))
      (node (ref "C21") (pin "-") (pinfunction "-_-") (pintype "passive"))
      (node (ref "C22") (pin "1") (pinfunction "1_1") (pintype "passive"))
      (node (ref "C23") (pin "1") (pinfunction "1_1") (pintype "passive"))
      (node (ref "C24") (pin "2") (pinfunction "2_2") (pintype "passive"))
      (node (ref "C25") (pin "1") (pinfunction "1_1") (pintype "passive"))
      (node (ref "C26") (pin "1") (pinfunction "1_1") (pintype "passive"))
      (node (ref "C27") (pin "1") (pinfunction "1_1") (pintype "passive"))
      (node (ref "C28") (pin "1") (pinfunction "1_1") (pintype "passive"))
      (node (ref "C29") (pin "1") (pinfunction "1_1") (pintype "passive"))
      (node (ref "C3") (pin "2") (pinfunction "2_2") (pintype "passive"))
      (node (ref "C30") (pin "2") (pinfunction "2_2") (pintype "passive"))
      (node (ref "C31") (pin "-") (pinfunction "-_-") (pintype "passive"))
      (node (ref "C32") (pin "-") (pinfunction "-_-") (pintype "passive"))
      (node (ref "C33") (pin "2") (pinfunction "2_2") (pintype "passive"))
      (node (ref "C34") (pin "-") (pinfunction "-_-") (pintype "passive"))
      (node (ref "C35") (pin "2") (pinfunction "2_2") (pintype "passive"))
      (node (ref "C37") (pin "1") (pinfunction "1_1") (pintype "passive"))
      (node (ref "C38") (pin "1") (pinfunction "1_1") (pintype "passive"))
      (node (ref "C38") (pin "2") (pinfunction "2_2") (pintype "passive"))
      (node (ref "C38") (pin "3") (pinfunction "3_3") (pintype "passive"))
      (node (ref "C38") (pin "4") (pinfunction "4_4") (pintype "passive"))
      (node (ref "C4") (pin "2") (pinfunction "2_2") (pintype "passive"))
      (node (ref "C41") (pin "1") (pinfunction "1_1") (pintype "passive"))
      (node (ref "C41") (pin "2") (pinfunction "2_2") (pintype "passive"))
      (node (ref "C41") (pin "3") (pinfunction "3_3") (pintype "passive"))
      (node (ref "C41") (pin "4") (pinfunction "4_4") (pintype "passive"))
      (node (ref "C42") (pin "2") (pinfunction "2_2") (pintype "passive"))
      (node (ref "C44") (pin "2") (pinfunction "2_2") (pintype "passive"))
      (node (ref "C46") (pin "1") (pinfunction "1_1") (pintype "passive"))
      (node (ref "C47") (pin "1") (pinfunction "1_1") (pintype "passive"))
      (node (ref "C49") (pin "1") (pinfunction "1_1") (pintype "passive"))
      (node (ref "C5") (pin "1") (pinfunction "1_1") (pintype "passive"))
      (node (ref "C50") (pin "1") (pinfunction "1_1") (pintype "passive"))
      (node (ref "C52") (pin "1") (pinfunction "1_1") (pintype "passive"))
      (node (ref "C52") (pin "2") (pinfunction "2_2") (pintype "passive"))
      (node (ref "C52") (pin "3") (pinfunction "3_3") (pintype "passive"))
      (node (ref "C52") (pin "4") (pinfunction "4_4") (pintype "passive"))
      (node (ref "C55") (pin "1") (pinfunction "1_1") (pintype "passive"))
      (node (ref "C55") (pin "2") (pinfunction "2_2") (pintype "passive"))
      (node (ref "C55") (pin "3") (pinfunction "3_3") (pintype "passive"))
      (node (ref "C55") (pin "4") (pinfunction "4_4") (pintype "passive"))
      (node (ref "C56") (pin "1") (pinfunction "1_1") (pintype "passive"))
      (node (ref "C56") (pin "2") (pinfunction "2_2") (pintype "passive"))
      (node (ref "C56") (pin "3") (pinfunction "3_3") (pintype "passive"))
      (node (ref "C56") (pin "4") (pinfunction "4_4") (pintype "passive"))
      (node (ref "C58") (pin "1") (pinfunction "1_1") (pintype "passive"))
      (node (ref "C58") (pin "2") (pinfunction "2_2") (pintype "passive"))
      (node (ref "C58") (pin "3") (pinfunction "3_3") (pintype "passive"))
      (node (ref "C58") (pin "4") (pinfunction "4_4") (pintype "passive"))
      (node (ref "C6") (pin "2") (pinfunction "2_2") (pintype "passive"))
      (node (ref "C75") (pin "-") (pinfunction "-_-") (pintype "passive"))
      (node (ref "C77") (pin "1") (pinfunction "1_1") (pintype "passive"))
      (node (ref "C8") (pin "-") (pinfunction "-_-") (pintype "passive"))
      (node (ref "C87") (pin "1") (pinfunction "1_1") (pintype "passive"))
      (node (ref "C88") (pin "-") (pinfunction "-_-") (pintype "passive"))
      (node (ref "C89") (pin "-") (pinfunction "-_-") (pintype "passive"))
      (node (ref "C90") (pin "1") (pinfunction "1_1") (pintype "passive"))
      (node (ref "C91") (pin "1") (pinfunction "1_1") (pintype "passive"))
      (node (ref "C92") (pin "-") (pinfunction "-_-") (pintype "passive"))
      (node (ref "C98") (pin "2") (pinfunction "2_2") (pintype "passive"))
      (node (ref "D11") (pin "1") (pinfunction "A_1") (pintype "passive"))
      (node (ref "D4") (pin "A") (pinfunction "A_A") (pintype "passive"))
      (node (ref "D6") (pin "A") (pinfunction "A_A") (pintype "passive"))
      (node (ref "D8") (pin "1") (pinfunction "A_1") (pintype "passive"))
      (node (ref "D9") (pin "1") (pinfunction "A_1") (pintype "passive"))
      (node (ref "G1") (pin "-") (pinfunction "-_-") (pintype "bidirectional"))
      (node (ref "IC1") (pin "10") (pinfunction "RD2_10") (pintype "input"))
      (node (ref "IC1") (pin "15") (pinfunction "ADS/_15") (pintype "bidirectional"))
      (node (ref "IC1") (pin "6") (pinfunction "WR2_6") (pintype "bidirectional"))
      (node (ref "IC1") (pin "8") (pinfunction "VSS_8") (pintype "bidirectional"))
      (node (ref "IC10") (pin "10") (pinfunction "GND_10") (pintype "bidirectional"))
      (node (ref "IC12") (pin "3") (pinfunction "GND_3") (pintype "power_in"))
      (node (ref "IC13") (pin "1") (pinfunction "NC1_1") (pintype "bidirectional"))
      (node (ref "IC13") (pin "11") (pinfunction "NC4_11") (pintype "bidirectional"))
      (node (ref "IC13") (pin "13") (pinfunction "VSS1_13") (pintype "bidirectional"))
      (node (ref "IC13") (pin "2") (pinfunction "NC2_2") (pintype "bidirectional"))
      (node (ref "IC13") (pin "20") (pinfunction "NC5_20") (pintype "bidirectional"))
      (node (ref "IC13") (pin "21") (pinfunction "NC6_21") (pintype "bidirectional"))
      (node (ref "IC13") (pin "22") (pinfunction "NC7_22") (pintype "bidirectional"))
      (node (ref "IC13") (pin "23") (pinfunction "NC8_23") (pintype "bidirectional"))
      (node (ref "IC13") (pin "24") (pinfunction "NC9_24") (pintype "bidirectional"))
      (node (ref "IC13") (pin "25") (pinfunction "NC10_25") (pintype "bidirectional"))
      (node (ref "IC13") (pin "26") (pinfunction "NC11_26") (pintype "bidirectional"))
      (node (ref "IC13") (pin "27") (pinfunction "NC12_27") (pintype "bidirectional"))
      (node (ref "IC13") (pin "28") (pinfunction "NC13_28") (pintype "bidirectional"))
      (node (ref "IC13") (pin "3") (pinfunction "NC3_3") (pintype "bidirectional"))
      (node (ref "IC13") (pin "33") (pinfunction "NC14_33") (pintype "bidirectional"))
      (node (ref "IC13") (pin "34") (pinfunction "NC15_34") (pintype "bidirectional"))
      (node (ref "IC13") (pin "35") (pinfunction "NC16_35") (pintype "bidirectional"))
      (node (ref "IC13") (pin "36") (pinfunction "VSS2_36") (pintype "bidirectional"))
      (node (ref "IC13") (pin "38") (pinfunction "NC17_38") (pintype "bidirectional"))
      (node (ref "IC13") (pin "39") (pinfunction "NC18_39") (pintype "bidirectional"))
      (node (ref "IC13") (pin "40") (pinfunction "NC19_40") (pintype "bidirectional"))
      (node (ref "IC13") (pin "45") (pinfunction "NC20_45") (pintype "bidirectional"))
      (node (ref "IC13") (pin "46") (pinfunction "NC21_46") (pintype "bidirectional"))
      (node (ref "IC13") (pin "47") (pinfunction "NC22_47") (pintype "bidirectional"))
      (node (ref "IC13") (pin "48") (pinfunction "NC23_48") (pintype "bidirectional"))
      (node (ref "IC14") (pin "1") (pinfunction "1OE/_1") (pintype "bidirectional"))
      (node (ref "IC14") (pin "10") (pinfunction "GND2_10") (pintype "bidirectional"))
      (node (ref "IC14") (pin "15") (pinfunction "GND3_15") (pintype "bidirectional"))
      (node (ref "IC14") (pin "21") (pinfunction "GND4_21") (pintype "bidirectional"))
      (node (ref "IC14") (pin "24") (pinfunction "2OE/_24") (pintype "bidirectional"))
      (node (ref "IC14") (pin "28") (pinfunction "GND5_28") (pintype "bidirectional"))
      (node (ref "IC14") (pin "34") (pinfunction "GND6_34") (pintype "bidirectional"))
      (node (ref "IC14") (pin "39") (pinfunction "GND7_39") (pintype "bidirectional"))
      (node (ref "IC14") (pin "4") (pinfunction "GND1_4") (pintype "bidirectional"))
      (node (ref "IC14") (pin "45") (pinfunction "GND8_45") (pintype "bidirectional"))
      (node (ref "IC2") (pin "10") (pinfunction "GND_10") (pintype "bidirectional"))
      (node (ref "IC2") (pin "15") (pinfunction "GND_15") (pintype "bidirectional"))
      (node (ref "IC2") (pin "20") (pinfunction "2B6_20") (pintype "bidirectional"))
      (node (ref "IC2") (pin "21") (pinfunction "GND_21") (pintype "bidirectional"))
      (node (ref "IC2") (pin "22") (pinfunction "2B7_22") (pintype "bidirectional"))
      (node (ref "IC2") (pin "23") (pinfunction "2B8_23") (pintype "bidirectional"))
      (node (ref "IC2") (pin "24") (pinfunction "2DIR_24") (pintype "bidirectional"))
      (node (ref "IC2") (pin "25") (pinfunction "2OE/_25") (pintype "bidirectional"))
      (node (ref "IC2") (pin "28") (pinfunction "GND_28") (pintype "bidirectional"))
      (node (ref "IC2") (pin "34") (pinfunction "GND_34") (pintype "bidirectional"))
      (node (ref "IC2") (pin "39") (pinfunction "GND_39") (pintype "bidirectional"))
      (node (ref "IC2") (pin "4") (pinfunction "GND_4") (pintype "bidirectional"))
      (node (ref "IC2") (pin "45") (pinfunction "GND_45") (pintype "bidirectional"))
      (node (ref "IC20") (pin "3") (pinfunction "GND_3") (pintype "bidirectional"))
      (node (ref "IC26") (pin "GND") (pinfunction "COM_GND") (pintype "bidirectional"))
      (node (ref "IC29") (pin "6") (pinfunction "GND_6") (pintype "bidirectional"))
      (node (ref "IC29") (pin "GP") (pinfunction "GP_GP") (pintype "bidirectional"))
      (node (ref "IC3") (pin "12") (pinfunction "VSS1_12") (pintype "bidirectional"))
      (node (ref "IC3") (pin "34") (pinfunction "VSS2_34") (pintype "bidirectional"))
      (node (ref "IC31") (pin "8") (pinfunction "VSS_8") (pintype "bidirectional"))
      (node (ref "IC32") (pin "4") (pinfunction "GND_4") (pintype "bidirectional"))
      (node (ref "IC36") (pin "1") (pinfunction "VSS_1") (pintype "bidirectional"))
      (node (ref "IC37") (pin "1") (pinfunction "GND_1") (pintype "bidirectional"))
      (node (ref "IC37") (pin "17") (pinfunction "GND_17") (pintype "bidirectional"))
      (node (ref "IC37") (pin "18") (pinfunction "GND_18") (pintype "bidirectional"))
      (node (ref "IC37") (pin "3") (pinfunction "RTS/_3") (pintype "bidirectional"))
      (node (ref "IC37") (pin "5") (pinfunction "STANDBY_5") (pintype "bidirectional"))
      (node (ref "IC38") (pin "3") (pinfunction "GND_3") (pintype "bidirectional"))
      (node (ref "IC39") (pin "3") (pinfunction "GND_3") (pintype "bidirectional"))
      (node (ref "IC4") (pin "110") (pinfunction "VSS7_110") (pintype "bidirectional"))
      (node (ref "IC4") (pin "127") (pinfunction "VSS8_127") (pintype "bidirectional"))
      (node (ref "IC4") (pin "139") (pinfunction "VSS9_139") (pintype "bidirectional"))
      (node (ref "IC4") (pin "143") (pinfunction "XTAL3_143") (pintype "bidirectional"))
      (node (ref "IC4") (pin "18") (pinfunction "VSS1_18") (pintype "bidirectional"))
      (node (ref "IC4") (pin "45") (pinfunction "VSS2_45") (pintype "bidirectional"))
      (node (ref "IC4") (pin "55") (pinfunction "VSS3_55") (pintype "bidirectional"))
      (node (ref "IC4") (pin "71") (pinfunction "VSS4_71") (pintype "bidirectional"))
      (node (ref "IC4") (pin "83") (pinfunction "VSS5_83") (pintype "bidirectional"))
      (node (ref "IC4") (pin "94") (pinfunction "VSS6_94") (pintype "bidirectional"))
      (node (ref "IC40") (pin "1") (pinfunction "DIR_1") (pintype "bidirectional"))
      (node (ref "IC40") (pin "10") (pinfunction "GND_10") (pintype "bidirectional"))
      (node (ref "IC40") (pin "11") (pinfunction "B7_11") (pintype "bidirectional"))
      (node (ref "IC40") (pin "16") (pinfunction "B2_16") (pintype "bidirectional"))
      (node (ref "IC41") (pin "3") (pinfunction "GND_3") (pintype "bidirectional"))
      (node (ref "IC42") (pin "3") (pinfunction "GND_3") (pintype "bidirectional"))
      (node (ref "IC43") (pin "3") (pinfunction "GND_3") (pintype "bidirectional"))
      (node (ref "IC44") (pin "3") (pinfunction "GND_3") (pintype "bidirectional"))
      (node (ref "IC5") (pin "3") (pinfunction "GND_3") (pintype "bidirectional"))
      (node (ref "IC6") (pin "3") (pinfunction "GND_3") (pintype "bidirectional"))
      (node (ref "IC7") (pin "27") (pinfunction "VSS1_27") (pintype "bidirectional"))
      (node (ref "IC7") (pin "46") (pinfunction "VSS2_46") (pintype "bidirectional"))
      (node (ref "IC8") (pin "3") (pinfunction "GND_3") (pintype "bidirectional"))
      (node (ref "IC9") (pin "3") (pinfunction "GND_3") (pintype "bidirectional"))
      (node (ref "J1") (pin "1B") (pinfunction "1B_1B") (pintype "bidirectional"))
      (node (ref "J1") (pin "22B") (pinfunction "22B_22B") (pintype "bidirectional"))
      (node (ref "J17") (pin "1") (pinfunction "P$1_1") (pintype "bidirectional"))
      (node (ref "J17") (pin "21") (pinfunction "P$21_21") (pintype "bidirectional"))
      (node (ref "J17") (pin "40") (pinfunction "P$40_40") (pintype "bidirectional"))
      (node (ref "J18") (pin "1") (pinfunction "1_1") (pintype "bidirectional"))
      (node (ref "J2") (pin "4") (pinfunction "4_4") (pintype "bidirectional"))
      (node (ref "J3") (pin "8") (pinfunction "8_8") (pintype "bidirectional"))
      (node (ref "J4") (pin "1") (pinfunction "1_1") (pintype "bidirectional"))
      (node (ref "J6") (pin "15") (pinfunction "15_15") (pintype "bidirectional"))
      (node (ref "J7") (pin "1") (pinfunction "1_1") (pintype "passive"))
      (node (ref "J7") (pin "24") (pinfunction "24_24") (pintype "passive"))
      (node (ref "J7") (pin "25") (pinfunction "25_25") (pintype "passive"))
      (node (ref "J7") (pin "4") (pinfunction "4_4") (pintype "passive"))
      (node (ref "JP1") (pin "1") (pinfunction "1_1") (pintype "passive"))
      (node (ref "JP7") (pin "1") (pinfunction "1_1") (pintype "passive"))
      (node (ref "JP8") (pin "1") (pinfunction "1_1") (pintype "passive"))
      (node (ref "JPL1") (pin "1") (pinfunction "1_1") (pintype "passive"))
      (node (ref "PT2") (pin "1") (pinfunction "1_1") (pintype "passive"))
      (node (ref "R12") (pin "2") (pinfunction "2_2") (pintype "bidirectional"))
      (node (ref "R18") (pin "1") (pinfunction "1_1") (pintype "bidirectional"))
      (node (ref "R20") (pin "2") (pinfunction "2_2") (pintype "bidirectional"))
      (node (ref "R21") (pin "2") (pinfunction "2_2") (pintype "bidirectional"))
      (node (ref "R24") (pin "2") (pinfunction "2_2") (pintype "bidirectional"))
      (node (ref "R26") (pin "2") (pinfunction "2_2") (pintype "bidirectional"))
      (node (ref "R29") (pin "2") (pinfunction "2_2") (pintype "bidirectional"))
      (node (ref "R30") (pin "1") (pinfunction "1_1") (pintype "bidirectional"))
      (node (ref "R31") (pin "2") (pinfunction "2_2") (pintype "bidirectional"))
      (node (ref "R41") (pin "1") (pinfunction "1_1") (pintype "bidirectional"))
      (node (ref "R47") (pin "1") (pinfunction "1_1") (pintype "bidirectional"))
      (node (ref "R52") (pin "1") (pinfunction "1_1") (pintype "bidirectional"))
      (node (ref "R54") (pin "1") (pinfunction "1_1") (pintype "bidirectional"))
      (node (ref "R60") (pin "1") (pinfunction "1_1") (pintype "bidirectional"))
      (node (ref "R61") (pin "2") (pinfunction "2_2") (pintype "bidirectional"))
      (node (ref "R65") (pin "1") (pinfunction "1_1") (pintype "bidirectional"))
      (node (ref "R7") (pin "2") (pinfunction "2_2") (pintype "bidirectional"))
      (node (ref "R73") (pin "1") (pinfunction "1_1") (pintype "bidirectional"))
      (node (ref "R8") (pin "1") (pinfunction "1_1") (pintype "bidirectional"))
      (node (ref "R9") (pin "1") (pinfunction "1_1") (pintype "bidirectional"))
      (node (ref "RL1") (pin "6") (pinfunction "L_6") (pintype "passive"))
      (node (ref "RL1") (pin "8") (pinfunction "B1-_8") (pintype "passive"))
      (node (ref "RS1") (pin "3") (pinfunction "3_3") (pintype "bidirectional"))
      (node (ref "RS3") (pin "3") (pinfunction "3_3") (pintype "bidirectional"))
      (node (ref "RS4") (pin "4") (pinfunction "4_4") (pintype "bidirectional"))
      (node (ref "RS5") (pin "2") (pinfunction "2_2") (pintype "bidirectional"))
      (node (ref "RS5") (pin "3") (pinfunction "3_3") (pintype "bidirectional"))
      (node (ref "T1") (pin "S") (pinfunction "S_S") (pintype "passive"))
      (node (ref "T14") (pin "S") (pinfunction "SOURCE_S") (pintype "passive"))
      (node (ref "T2") (pin "S") (pinfunction "S_S") (pintype "passive"))
      (node (ref "T20") (pin "S") (pinfunction "SOURCE_S") (pintype "passive"))
      (node (ref "T4") (pin "S") (pinfunction "S_S") (pintype "passive"))
      (node (ref "T5") (pin "S") (pinfunction "S_S") (pintype "passive"))
      (node (ref "T6") (pin "S") (pinfunction "S_S") (pintype "passive"))
      (node (ref "T8") (pin "S") (pinfunction "S_S") (pintype "passive"))
      (node (ref "T9") (pin "S") (pinfunction "S_S") (pintype "passive"))
    )
    (net (code "110") (name "INHIB-STOP-INV") (class "Default")
      (node (ref "J1") (pin "2B") (pinfunction "2B_2B") (pintype "bidirectional"))
      (node (ref "L12") (pin "2") (pinfunction "2_2") (pintype "bidirectional"))
    )
    (net (code "111") (name "INT-PRES-MEAS") (class "Default")
      (node (ref "IC27") (pin "3") (pinfunction "VOUT_3") (pintype "bidirectional"))
      (node (ref "JP2") (pin "1") (pinfunction "1_1") (pintype "passive"))
    )
    (net (code "112") (name "INV-STOP") (class "Default")
      (node (ref "IC4") (pin "62") (pinfunction "P2.13-CC13IOIO-EX5IN_62") (pintype "bidirectional"))
      (node (ref "L15") (pin "2") (pinfunction "2_2") (pintype "bidirectional"))
    )
    (net (code "113") (name "IRQ-UART") (class "Default")
      (node (ref "IC1") (pin "23") (pinfunction "INTRPT_23") (pintype "output"))
      (node (ref "IC4") (pin "14") (pinfunction "P8.5-CC21IO_14") (pintype "bidirectional"))
    )
    (net (code "114") (name "KEY-1") (class "Default")
      (node (ref "C14") (pin "5") (pinfunction "5_5") (pintype "passive"))
      (node (ref "IC4") (pin "68") (pinfunction "P3.3-T3OUT_68") (pintype "bidirectional"))
      (node (ref "J1") (pin "19B") (pinfunction "19B_19B") (pintype "bidirectional"))
      (node (ref "RS1") (pin "8") (pinfunction "8_8") (pintype "bidirectional"))
    )
    (net (code "115") (name "KEY-2") (class "Default")
      (node (ref "C14") (pin "6") (pinfunction "6_6") (pintype "passive"))
      (node (ref "IC4") (pin "69") (pinfunction "P3.4-T3EUD_69") (pintype "bidirectional"))
      (node (ref "J1") (pin "17B") (pinfunction "17B_17B") (pintype "bidirectional"))
      (node (ref "RS1") (pin "7") (pinfunction "7_7") (pintype "bidirectional"))
    )
    (net (code "116") (name "LED-AL-O") (class "Default")
      (node (ref "IC4") (pin "25") (pinfunction "P7.6-CC30IO_25") (pintype "bidirectional"))
      (node (ref "R24") (pin "1") (pinfunction "1_1") (pintype "bidirectional"))
      (node (ref "T8") (pin "G") (pinfunction "G_G") (pintype "passive"))
    )
    (net (code "117") (name "LED-AL-R") (class "Default")
      (node (ref "IC4") (pin "26") (pinfunction "P7.7-CC31IO_26") (pintype "bidirectional"))
      (node (ref "R21") (pin "1") (pinfunction "1_1") (pintype "bidirectional"))
      (node (ref "T5") (pin "G") (pinfunction "G_G") (pintype "passive"))
    )
    (net (code "118") (name "LED-DRIVE-LINE1") (class "Default")
      (node (ref "C18") (pin "8") (pinfunction "8_8") (pintype "passive"))
      (node (ref "J3") (pin "7") (pinfunction "7_7") (pintype "bidirectional"))
      (node (ref "L41") (pin "1") (pinfunction "1_1") (pintype "bidirectional"))
    )
    (net (code "119") (name "LED-DRIVE-LINE2") (class "Default")
      (node (ref "C17") (pin "5") (pinfunction "5_5") (pintype "passive"))
      (node (ref "J3") (pin "6") (pinfunction "6_6") (pintype "bidirectional"))
      (node (ref "L40") (pin "1") (pinfunction "1_1") (pintype "bidirectional"))
    )
    (net (code "120") (name "LED-O2") (class "Default")
      (node (ref "IC14") (pin "3") (pinfunction "1Q2_3") (pintype "bidirectional"))
      (node (ref "R20") (pin "1") (pinfunction "1_1") (pintype "bidirectional"))
      (node (ref "T4") (pin "G") (pinfunction "G_G") (pintype "passive"))
    )
    (net (code "121") (name "LED-PRESENCE-DC") (class "Default")
      (node (ref "J1") (pin "5B") (pinfunction "5B_5B") (pintype "bidirectional"))
      (node (ref "L18") (pin "1") (pinfunction "1_1") (pintype "bidirectional"))
    )
    (net (code "122") (name "LED-VENTIL") (class "Default")
      (node (ref "IC14") (pin "2") (pinfunction "1Q1_2") (pintype "bidirectional"))
      (node (ref "R26") (pin "1") (pinfunction "1_1") (pintype "bidirectional"))
      (node (ref "T9") (pin "G") (pinfunction "G_G") (pintype "passive"))
    )
    (net (code "123") (name "LED_BAT") (class "Default")
      (node (ref "L48") (pin "2") (pinfunction "2_2") (pintype "bidirectional"))
      (node (ref "R12") (pin "1") (pinfunction "1_1") (pintype "bidirectional"))
      (node (ref "T2") (pin "G") (pinfunction "G_G") (pintype "passive"))
    )
    (net (code "124") (name "LED_PRESENCE_AC") (class "Default")
      (node (ref "IC40") (pin "15") (pinfunction "B3_15") (pintype "bidirectional"))
      (node (ref "L47") (pin "2") (pinfunction "2_2") (pintype "bidirectional"))
      (node (ref "R7") (pin "1") (pinfunction "1_1") (pintype "bidirectional"))
      (node (ref "T1") (pin "G") (pinfunction "G_G") (pintype "passive"))
    )
    (net (code "125") (name "MES-24V") (class "Default")
      (node (ref "C74") (pin "2") (pinfunction "2_2") (pintype "passive"))
      (node (ref "D5") (pin "1") (pinfunction "3_1") (pintype "bidirectional"))
      (node (ref "IC4") (pin "42") (pinfunction "P5.13-AN13-T5IN_42") (pintype "bidirectional"))
      (node (ref "R36") (pin "2") (pinfunction "2_2") (pintype "bidirectional"))
      (node (ref "R40") (pin "1") (pinfunction "1_1") (pintype "bidirectional"))
    )
    (net (code "126") (name "MES-I-VALVE") (class "Default")
      (node (ref "C39") (pin "1") (pinfunction "1_1") (pintype "passive"))
      (node (ref "C45") (pin "2") (pinfunction "2_2") (pintype "passive"))
      (node (ref "D3") (pin "5") (pinfunction "5_5") (pintype "bidirectional"))
      (node (ref "IC11") (pin "7") (pinfunction "OUT_7") (pintype "output"))
      (node (ref "IC4") (pin "40") (pinfunction "P5.11-AN11-T5EUD_40") (pintype "bidirectional"))
      (node (ref "R56") (pin "1") (pinfunction "1_1") (pintype "bidirectional"))
    )
    (net (code "127") (name "MES_Q_E") (class "Default")
      (node (ref "C66") (pin "2") (pinfunction "2_2") (pintype "passive"))
      (node (ref "D2") (pin "5") (pinfunction "5_5") (pintype "bidirectional"))
      (node (ref "IC4") (pin "34") (pinfunction "P5.7-AN7_34") (pintype "bidirectional"))
      (node (ref "R37") (pin "2") (pinfunction "2_2") (pintype "bidirectional"))
    )
    (net (code "128") (name "MRST-SPI-0_E") (class "Default")
      (node (ref "IC10") (pin "16") (pinfunction "SDO_16") (pintype "bidirectional"))
      (node (ref "IC27") (pin "4") (pinfunction "MISO_4") (pintype "bidirectional"))
      (node (ref "IC28") (pin "4") (pinfunction "MISO_4") (pintype "bidirectional"))
      (node (ref "IC30") (pin "4") (pinfunction "MISO_4") (pintype "bidirectional"))
      (node (ref "IC31") (pin "9") (pinfunction "SDO_9") (pintype "bidirectional"))
      (node (ref "IC32") (pin "2") (pinfunction "SO_2") (pintype "output"))
      (node (ref "IC34") (pin "4") (pinfunction "MISO_4") (pintype "bidirectional"))
      (node (ref "IC35") (pin "4") (pinfunction "MISO_4") (pintype "bidirectional"))
      (node (ref "IC4") (pin "75") (pinfunction "P3.8-MRST0_75") (pintype "bidirectional"))
      (node (ref "IC44") (pin "2") (pinfunction "B_2") (pintype "bidirectional"))
    )
    (net (code "129") (name "MRST-SPI-1") (class "Default")
      (node (ref "IC40") (pin "13") (pinfunction "B5_13") (pintype "bidirectional"))
      (node (ref "L52") (pin "1") (pinfunction "1_1") (pintype "bidirectional"))
    )
    (net (code "130") (name "MRST_SPI_0") (class "Default")
      (node (ref "IC40") (pin "12") (pinfunction "B6_12") (pintype "bidirectional"))
      (node (ref "L44") (pin "2") (pinfunction "2_2") (pintype "bidirectional"))
    )
    (net (code "131") (name "MRST_SPI_1_E") (class "Default")
      (node (ref "IC4") (pin "8") (pinfunction "P6.7-BREQ/-MRST1_8") (pintype "bidirectional"))
      (node (ref "IC40") (pin "7") (pinfunction "A5_7") (pintype "bidirectional"))
    )
    (net (code "132") (name "MTSR-SPI-0") (class "Default")
      (node (ref "IC10") (pin "15") (pinfunction "SDI_15") (pintype "bidirectional"))
      (node (ref "IC27") (pin "8") (pinfunction "MOSI_8") (pintype "bidirectional"))
      (node (ref "IC28") (pin "8") (pinfunction "MOSI_8") (pintype "bidirectional"))
      (node (ref "IC30") (pin "8") (pinfunction "MOSI_8") (pintype "bidirectional"))
      (node (ref "IC31") (pin "12") (pinfunction "SDI_12") (pintype "bidirectional"))
      (node (ref "IC32") (pin "5") (pinfunction "SI_5") (pintype "input"))
      (node (ref "IC34") (pin "8") (pinfunction "MOSI_8") (pintype "bidirectional"))
      (node (ref "IC35") (pin "8") (pinfunction "MOSI_8") (pintype "bidirectional"))
      (node (ref "IC4") (pin "76") (pinfunction "P3.9-MTSR0_76") (pintype "bidirectional"))
      (node (ref "L43") (pin "2") (pinfunction "2_2") (pintype "bidirectional"))
    )
    (net (code "133") (name "MTSR-SPI-1") (class "Default")
      (node (ref "IC4") (pin "7") (pinfunction "P6.6-HDLA/-MTSR1_7") (pintype "bidirectional"))
      (node (ref "L51") (pin "1") (pinfunction "1_1") (pintype "bidirectional"))
    )
    (net (code "134") (name "Net-(ANT-Pad2)") (class "Default")
      (node (ref "ANT") (pin "2") (pinfunction "2_2") (pintype "bidirectional"))
      (node (ref "IC37") (pin "20") (pinfunction "GNDRF_20") (pintype "bidirectional"))
    )
    (net (code "135") (name "Net-(ANT-Pad3)") (class "Default")
      (node (ref "ANT") (pin "3") (pinfunction "3_3") (pintype "bidirectional"))
      (node (ref "IC37") (pin "19") (pinfunction "GNDRF_19") (pintype "bidirectional"))
    )
    (net (code "136") (name "Net-(C3-Pad1)") (class "Default")
      (node (ref "C3") (pin "1") (pinfunction "1_1") (pintype "passive"))
      (node (ref "Q1") (pin "1") (pinfunction "1_1") (pintype "passive"))
      (node (ref "R1") (pin "1") (pinfunction "1_1") (pintype "bidirectional"))
    )
    (net (code "137") (name "Net-(C12-Pad1)") (class "Default")
      (node (ref "C12") (pin "1") (pinfunction "1_1") (pintype "passive"))
      (node (ref "J2") (pin "6") (pinfunction "6_6") (pintype "bidirectional"))
      (node (ref "L9") (pin "1") (pinfunction "1_1") (pintype "bidirectional"))
    )
    (net (code "138") (name "Net-(C13-Pad1)") (class "Default")
      (node (ref "C13") (pin "1") (pinfunction "1_1") (pintype "passive"))
      (node (ref "J18") (pin "7") (pinfunction "7_7") (pintype "bidirectional"))
      (node (ref "L12") (pin "1") (pinfunction "1_1") (pintype "bidirectional"))
    )
    (net (code "139") (name "Net-(C15-Pad1)") (class "Default")
      (node (ref "C15") (pin "1") (pinfunction "1_1") (pintype "passive"))
      (node (ref "Q2") (pin "2") (pinfunction "2_2") (pintype "passive"))
      (node (ref "R2") (pin "2") (pinfunction "2_2") (pintype "bidirectional"))
      (node (ref "R4") (pin "1") (pinfunction "1_1") (pintype "bidirectional"))
    )
    (net (code "140") (name "Net-(C18-Pad6)") (class "Default")
      (node (ref "C18") (pin "6") (pinfunction "6_6") (pintype "passive"))
      (node (ref "J3") (pin "12") (pinfunction "12_12") (pintype "bidirectional"))
      (node (ref "L42") (pin "1") (pinfunction "1_1") (pintype "bidirectional"))
    )
    (net (code "141") (name "Net-(C18-Pad7)") (class "Default")
      (node (ref "C18") (pin "7") (pinfunction "7_7") (pintype "passive"))
      (node (ref "J3") (pin "9") (pinfunction "9_9") (pintype "bidirectional"))
      (node (ref "L35") (pin "1") (pinfunction "1_1") (pintype "bidirectional"))
    )
    (net (code "142") (name "Net-(C38-Pad5)") (class "Default")
      (node (ref "C38") (pin "5") (pinfunction "5_5") (pintype "passive"))
      (node (ref "J2") (pin "5") (pinfunction "5_5") (pintype "bidirectional"))
      (node (ref "L10") (pin "1") (pinfunction "1_1") (pintype "bidirectional"))
    )
    (net (code "143") (name "Net-(C38-Pad6)") (class "Default")
      (node (ref "C38") (pin "6") (pinfunction "6_6") (pintype "passive"))
      (node (ref "J2") (pin "3") (pinfunction "3_3") (pintype "bidirectional"))
      (node (ref "L11") (pin "1") (pinfunction "1_1") (pintype "bidirectional"))
    )
    (net (code "144") (name "Net-(C38-Pad7)") (class "Default")
      (node (ref "C38") (pin "7") (pinfunction "7_7") (pintype "passive"))
      (node (ref "J2") (pin "2") (pinfunction "2_2") (pintype "bidirectional"))
      (node (ref "L19") (pin "1") (pinfunction "1_1") (pintype "bidirectional"))
    )
    (net (code "145") (name "Net-(C38-Pad8)") (class "Default")
      (node (ref "C38") (pin "8") (pinfunction "8_8") (pintype "passive"))
      (node (ref "J2") (pin "1") (pinfunction "1_1") (pintype "bidirectional"))
      (node (ref "L20") (pin "1") (pinfunction "1_1") (pintype "bidirectional"))
    )
    (net (code "146") (name "Net-(C41-Pad5)") (class "Default")
      (node (ref "C41") (pin "5") (pinfunction "5_5") (pintype "passive"))
      (node (ref "J7") (pin "15") (pinfunction "15_15") (pintype "passive"))
      (node (ref "L47") (pin "1") (pinfunction "1_1") (pintype "bidirectional"))
    )
    (net (code "147") (name "Net-(C41-Pad6)") (class "Default")
      (node (ref "C41") (pin "6") (pinfunction "6_6") (pintype "passive"))
      (node (ref "J7") (pin "11") (pinfunction "11_11") (pintype "passive"))
      (node (ref "L45") (pin "1") (pinfunction "1_1") (pintype "bidirectional"))
    )
    (net (code "148") (name "Net-(C41-Pad7)") (class "Default")
      (node (ref "C41") (pin "7") (pinfunction "7_7") (pintype "passive"))
      (node (ref "J7") (pin "9") (pinfunction "9_9") (pintype "passive"))
      (node (ref "L44") (pin "1") (pinfunction "1_1") (pintype "bidirectional"))
    )
    (net (code "149") (name "Net-(C41-Pad8)") (class "Default")
      (node (ref "C41") (pin "8") (pinfunction "8_8") (pintype "passive"))
      (node (ref "J7") (pin "7") (pinfunction "7_7") (pintype "passive"))
      (node (ref "L43") (pin "1") (pinfunction "1_1") (pintype "bidirectional"))
    )
    (net (code "150") (name "Net-(C52-Pad5)") (class "Default")
      (node (ref "C52") (pin "5") (pinfunction "5_5") (pintype "passive"))
      (node (ref "J7") (pin "12") (pinfunction "12_12") (pintype "passive"))
      (node (ref "L3") (pin "2") (pinfunction "2_2") (pintype "bidirectional"))
    )
    (net (code "151") (name "Net-(C52-Pad6)") (class "Default")
      (node (ref "C52") (pin "6") (pinfunction "6_6") (pintype "passive"))
      (node (ref "J7") (pin "10") (pinfunction "10_10") (pintype "passive"))
      (node (ref "L4") (pin "2") (pinfunction "2_2") (pintype "bidirectional"))
    )
    (net (code "152") (name "Net-(C52-Pad7)") (class "Default")
      (node (ref "C52") (pin "7") (pinfunction "7_7") (pintype "passive"))
      (node (ref "J7") (pin "8") (pinfunction "8_8") (pintype "passive"))
      (node (ref "L5") (pin "2") (pinfunction "2_2") (pintype "bidirectional"))
    )
    (net (code "153") (name "Net-(C52-Pad8)") (class "Default")
      (node (ref "C52") (pin "8") (pinfunction "8_8") (pintype "passive"))
      (node (ref "J7") (pin "6") (pinfunction "6_6") (pintype "passive"))
      (node (ref "L6") (pin "2") (pinfunction "2_2") (pintype "bidirectional"))
    )
    (net (code "154") (name "Net-(C55-Pad5)") (class "Default")
      (node (ref "C55") (pin "5") (pinfunction "5_5") (pintype "passive"))
      (node (ref "J7") (pin "23") (pinfunction "23_23") (pintype "passive"))
      (node (ref "L61") (pin "1") (pinfunction "1_1") (pintype "bidirectional"))
    )
    (net (code "155") (name "Net-(C55-Pad6)") (class "Default")
      (node (ref "C55") (pin "6") (pinfunction "6_6") (pintype "passive"))
      (node (ref "J7") (pin "21") (pinfunction "21_21") (pintype "passive"))
      (node (ref "L50") (pin "1") (pinfunction "1_1") (pintype "bidirectional"))
    )
    (net (code "156") (name "Net-(C55-Pad7)") (class "Default")
      (node (ref "C55") (pin "7") (pinfunction "7_7") (pintype "passive"))
      (node (ref "J7") (pin "19") (pinfunction "19_19") (pintype "passive"))
      (node (ref "L49") (pin "1") (pinfunction "1_1") (pintype "bidirectional"))
    )
    (net (code "157") (name "Net-(C55-Pad8)") (class "Default")
      (node (ref "C55") (pin "8") (pinfunction "8_8") (pintype "passive"))
      (node (ref "J7") (pin "17") (pinfunction "17_17") (pintype "passive"))
      (node (ref "L48") (pin "1") (pinfunction "1_1") (pintype "bidirectional"))
    )
    (net (code "158") (name "Net-(C58-Pad5)") (class "Default")
      (node (ref "C58") (pin "5") (pinfunction "5_5") (pintype "passive"))
      (node (ref "J7") (pin "20") (pinfunction "20_20") (pintype "passive"))
      (node (ref "L16") (pin "2") (pinfunction "2_2") (pintype "bidirectional"))
    )
    (net (code "159") (name "Net-(C58-Pad6)") (class "Default")
      (node (ref "C58") (pin "6") (pinfunction "6_6") (pintype "passive"))
      (node (ref "J7") (pin "18") (pinfunction "18_18") (pintype "passive"))
      (node (ref "L52") (pin "2") (pinfunction "2_2") (pintype "bidirectional"))
    )
    (net (code "160") (name "Net-(C58-Pad7)") (class "Default")
      (node (ref "C58") (pin "7") (pinfunction "7_7") (pintype "passive"))
      (node (ref "J7") (pin "16") (pinfunction "16_16") (pintype "passive"))
      (node (ref "L18") (pin "2") (pinfunction "2_2") (pintype "bidirectional"))
    )
    (net (code "161") (name "Net-(C58-Pad8)") (class "Default")
      (node (ref "C58") (pin "8") (pinfunction "8_8") (pintype "passive"))
      (node (ref "J7") (pin "14") (pinfunction "14_14") (pintype "passive"))
      (node (ref "L1") (pin "2") (pinfunction "2_2") (pintype "bidirectional"))
    )
    (net (code "162") (name "Net-(C75-Pad+)") (class "Default")
      (node (ref "C75") (pin "+") (pinfunction "+_+") (pintype "passive"))
      (node (ref "J2") (pin "7") (pinfunction "7_7") (pintype "bidirectional"))
      (node (ref "L7") (pin "1") (pinfunction "1_1") (pintype "bidirectional"))
    )
    (net (code "163") (name "Net-(C86-Pad2)") (class "Default")
      (node (ref "C86") (pin "2") (pinfunction "2_2") (pintype "passive"))
      (node (ref "J5") (pin "2") (pinfunction "2_2") (pintype "bidirectional"))
      (node (ref "L37") (pin "1") (pinfunction "1_1") (pintype "bidirectional"))
    )
    (net (code "164") (name "Net-(C99-Pad1)") (class "Default")
      (node (ref "C99") (pin "1") (pinfunction "1_1") (pintype "passive"))
      (node (ref "J11") (pin "2") (pinfunction "2_2") (pintype "bidirectional"))
      (node (ref "L21") (pin "1") (pinfunction "1_1") (pintype "bidirectional"))
    )
    (net (code "165") (name "Net-(C100-Pad5)") (class "Default")
      (node (ref "C100") (pin "5") (pinfunction "5_5") (pintype "passive"))
      (node (ref "J18") (pin "6") (pinfunction "6_6") (pintype "bidirectional"))
      (node (ref "L13") (pin "1") (pinfunction "1_1") (pintype "bidirectional"))
    )
    (net (code "166") (name "Net-(C100-Pad6)") (class "Default")
      (node (ref "C100") (pin "6") (pinfunction "6_6") (pintype "passive"))
      (node (ref "J18") (pin "5") (pinfunction "5_5") (pintype "bidirectional"))
      (node (ref "L14") (pin "1") (pinfunction "1_1") (pintype "bidirectional"))
    )
    (net (code "167") (name "Net-(C100-Pad7)") (class "Default")
      (node (ref "C100") (pin "7") (pinfunction "7_7") (pintype "passive"))
      (node (ref "J18") (pin "4") (pinfunction "4_4") (pintype "bidirectional"))
      (node (ref "L15") (pin "1") (pinfunction "1_1") (pintype "bidirectional"))
    )
    (net (code "168") (name "Net-(C100-Pad8)") (class "Default")
      (node (ref "C100") (pin "8") (pinfunction "8_8") (pintype "passive"))
      (node (ref "J18") (pin "3") (pinfunction "3_3") (pintype "bidirectional"))
      (node (ref "L17") (pin "1") (pinfunction "1_1") (pintype "bidirectional"))
    )
    (net (code "169") (name "Net-(C111-Pad5)") (class "Default")
      (node (ref "C111") (pin "5") (pinfunction "5_5") (pintype "passive"))
      (node (ref "J7") (pin "13") (pinfunction "13_13") (pintype "passive"))
      (node (ref "L46") (pin "1") (pinfunction "1_1") (pintype "bidirectional"))
    )
    (net (code "170") (name "Net-(C111-Pad6)") (class "Default")
      (node (ref "C111") (pin "6") (pinfunction "6_6") (pintype "passive"))
      (node (ref "J7") (pin "5") (pinfunction "5_5") (pintype "passive"))
      (node (ref "L53") (pin "1") (pinfunction "1_1") (pintype "bidirectional"))
    )
    (net (code "171") (name "Net-(C111-Pad7)") (class "Default")
      (node (ref "C111") (pin "7") (pinfunction "7_7") (pintype "passive"))
      (node (ref "J7") (pin "3") (pinfunction "3_3") (pintype "passive"))
      (node (ref "L8") (pin "1") (pinfunction "1_1") (pintype "bidirectional"))
    )
    (net (code "172") (name "Net-(C111-Pad8)") (class "Default")
      (node (ref "C111") (pin "8") (pinfunction "8_8") (pintype "passive"))
      (node (ref "J7") (pin "22") (pinfunction "22_22") (pintype "passive"))
      (node (ref "L51") (pin "2") (pinfunction "2_2") (pintype "bidirectional"))
    )
    (net (code "173") (name "Net-(C115-Pad2)") (class "Default")
      (node (ref "C115") (pin "2") (pinfunction "2_2") (pintype "passive"))
      (node (ref "J18") (pin "2") (pinfunction "2_2") (pintype "bidirectional"))
      (node (ref "L22") (pin "1") (pinfunction "1_1") (pintype "bidirectional"))
    )
    (net (code "174") (name "Net-(C121-Pad1)") (class "Default")
      (node (ref "C121") (pin "1") (pinfunction "1_1") (pintype "passive"))
      (node (ref "J19") (pin "2") (pinfunction "2_2") (pintype "bidirectional"))
      (node (ref "L23") (pin "1") (pinfunction "1_1") (pintype "bidirectional"))
    )
    (net (code "175") (name "Net-(C122-Pad2)") (class "Default")
      (node (ref "C122") (pin "2") (pinfunction "2_2") (pintype "passive"))
      (node (ref "J19") (pin "1") (pinfunction "1_1") (pintype "bidirectional"))
      (node (ref "L24") (pin "1") (pinfunction "1_1") (pintype "bidirectional"))
    )
    (net (code "176") (name "Net-(C123-Pad1)") (class "Default")
      (node (ref "C123") (pin "1") (pinfunction "1_1") (pintype "passive"))
      (node (ref "J21") (pin "2") (pinfunction "2_2") (pintype "bidirectional"))
      (node (ref "L25") (pin "1") (pinfunction "1_1") (pintype "bidirectional"))
    )
    (net (code "177") (name "Net-(C124-Pad2)") (class "Default")
      (node (ref "C124") (pin "2") (pinfunction "2_2") (pintype "passive"))
      (node (ref "J21") (pin "1") (pinfunction "1_1") (pintype "bidirectional"))
      (node (ref "L26") (pin "1") (pinfunction "1_1") (pintype "bidirectional"))
    )
    (net (code "178") (name "Net-(C126-Pad2)") (class "Default")
      (node (ref "C126") (pin "2") (pinfunction "2_2") (pintype "passive"))
      (node (ref "J20") (pin "3") (pinfunction "3_3") (pintype "bidirectional"))
      (node (ref "L28") (pin "1") (pinfunction "1_1") (pintype "bidirectional"))
    )
    (net (code "179") (name "Net-(C127-Pad1)") (class "Default")
      (node (ref "C127") (pin "1") (pinfunction "1_1") (pintype "passive"))
      (node (ref "J20") (pin "4") (pinfunction "4_4") (pintype "bidirectional"))
      (node (ref "L27") (pin "1") (pinfunction "1_1") (pintype "bidirectional"))
    )
    (net (code "180") (name "Net-(D5-1)") (class "Default")
      (node (ref "C36") (pin "1") (pinfunction "1_1") (pintype "passive"))
      (node (ref "D5") (pin "3") (pinfunction "1_3") (pintype "bidirectional"))
      (node (ref "IC4") (pin "41") (pinfunction "P5.12-AN12-T6IN_41") (pintype "bidirectional"))
      (node (ref "R14") (pin "2") (pinfunction "2_2") (pintype "bidirectional"))
      (node (ref "R15") (pin "2") (pinfunction "2_2") (pintype "bidirectional"))
    )
    (net (code "181") (name "Net-(D8-K)") (class "Default")
      (node (ref "D8") (pin "3") (pinfunction "K_3") (pintype "passive"))
      (node (ref "IC41") (pin "2") (pinfunction "A_2") (pintype "input"))
      (node (ref "R72") (pin "2") (pinfunction "2_2") (pintype "bidirectional"))
    )
    (net (code "182") (name "Net-(D9-K)") (class "Default")
      (node (ref "C112") (pin "1") (pinfunction "1_1") (pintype "passive"))
      (node (ref "D9") (pin "3") (pinfunction "K_3") (pintype "passive"))
      (node (ref "IC42") (pin "1") (pinfunction "B_1") (pintype "input"))
      (node (ref "IC42") (pin "2") (pinfunction "A_2") (pintype "input"))
      (node (ref "R61") (pin "1") (pinfunction "1_1") (pintype "bidirectional"))
    )
    (net (code "183") (name "Net-(D10-A)") (class "Default")
      (node (ref "D10") (pin "1") (pinfunction "A_1") (pintype "passive"))
      (node (ref "IC42") (pin "4") (pinfunction "Y_4") (pintype "open_collector"))
      (node (ref "IC43") (pin "2") (pinfunction "A_2") (pintype "input"))
      (node (ref "R46") (pin "2") (pinfunction "2_2") (pintype "bidirectional"))
    )
    (net (code "184") (name "Net-(D10-K)") (class "Default")
      (node (ref "C114") (pin "2") (pinfunction "2_2") (pintype "passive"))
      (node (ref "D10") (pin "3") (pinfunction "K_3") (pintype "passive"))
      (node (ref "R46") (pin "1") (pinfunction "1_1") (pintype "bidirectional"))
      (node (ref "R60") (pin "2") (pinfunction "2_2") (pintype "bidirectional"))
      (node (ref "T6") (pin "G") (pinfunction "G_G") (pintype "passive"))
    )
    (net (code "185") (name "Net-(D11-K)") (class "Default")
      (node (ref "C97") (pin "1") (pinfunction "1_1") (pintype "passive"))
      (node (ref "D11") (pin "3") (pinfunction "K_3") (pintype "passive"))
      (node (ref "IC29") (pin "8") (pinfunction "PH_8") (pintype "bidirectional"))
      (node (ref "L2") (pin "2") (pinfunction "2_2") (pintype "bidirectional"))
    )
    (net (code "186") (name "Net-(D12-A)") (class "Default")
      (node (ref "BUZ1") (pin "+") (pinfunction "+_+") (pintype "passive"))
      (node (ref "D12") (pin "1") (pinfunction "A_1") (pintype "passive"))
    )
    (net (code "187") (name "Net-(D13-A)") (class "Default")
      (node (ref "D13") (pin "1") (pinfunction "A_1") (pintype "passive"))
      (node (ref "T19") (pin "D") (pinfunction "D_D") (pintype "passive"))
    )
    (net (code "188") (name "Net-(IC1-BAUDOUT{slash})") (class "Default")
      (node (ref "IC1") (pin "54") (pinfunction "RCLK_54") (pintype "input"))
      (node (ref "IC1") (pin "64") (pinfunction "BAUDOUT/_64") (pintype "output"))
    )
    (net (code "189") (name "Net-(IC1-CTS{slash})") (class "Default")
      (node (ref "IC1") (pin "33") (pinfunction "CTS/_33") (pintype "input"))
      (node (ref "RS8") (pin "4") (pinfunction "4_4") (pintype "bidirectional"))
    )
    (net (code "190") (name "Net-(IC1-DCD{slash})") (class "Default")
      (node (ref "IC1") (pin "36") (pinfunction "DCD/_36") (pintype "input"))
      (node (ref "RS8") (pin "2") (pinfunction "2_2") (pintype "bidirectional"))
    )
    (net (code "191") (name "Net-(IC1-DSR{slash})") (class "Default")
      (node (ref "IC1") (pin "35") (pinfunction "DSR/_35") (pintype "input"))
      (node (ref "RS8") (pin "3") (pinfunction "3_3") (pintype "bidirectional"))
    )
    (net (code "192") (name "Net-(IC1-RI{slash})") (class "Default")
      (node (ref "IC1") (pin "38") (pinfunction "RI/_38") (pintype "input"))
      (node (ref "RS8") (pin "1") (pinfunction "1_1") (pintype "bidirectional"))
    )
    (net (code "193") (name "Net-(IC1-SIN)") (class "Default")
      (node (ref "IC1") (pin "55") (pinfunction "SIN_55") (pintype "input"))
      (node (ref "IC9") (pin "4") (pinfunction "Y_4") (pintype "open_collector"))
      (node (ref "R5") (pin "1") (pinfunction "1_1") (pintype "bidirectional"))
    )
    (net (code "194") (name "Net-(IC1-SOUT)") (class "Default")
      (node (ref "IC1") (pin "58") (pinfunction "SOUT_58") (pintype "output"))
      (node (ref "IC8") (pin "2") (pinfunction "A_2") (pintype "input"))
    )
    (net (code "195") (name "Net-(IC1-XIN)") (class "Default")
      (node (ref "C16") (pin "2") (pinfunction "2_2") (pintype "passive"))
      (node (ref "IC1") (pin "1") (pinfunction "XIN_1") (pintype "input"))
      (node (ref "Q2") (pin "1") (pinfunction "1_1") (pintype "passive"))
      (node (ref "R4") (pin "2") (pinfunction "2_2") (pintype "bidirectional"))
    )
    (net (code "196") (name "Net-(IC1-XOUT)") (class "Default")
      (node (ref "IC1") (pin "2") (pinfunction "XOUT_2") (pintype "output"))
      (node (ref "R2") (pin "1") (pinfunction "1_1") (pintype "bidirectional"))
    )
    (net (code "197") (name "Net-(IC2-2B1)") (class "Default")
      (node (ref "IC2") (pin "13") (pinfunction "2B1_13") (pintype "bidirectional"))
      (node (ref "IC5") (pin "4") (pinfunction "Y_4") (pintype "open_collector"))
    )
    (net (code "198") (name "Net-(IC4-P4.4-A20-CAN2_RXD-SCL)") (class "Default")
      (node (ref "IC4") (pin "89") (pinfunction "P4.4-A20-CAN2_RXD-SCL_89") (pintype "bidirectional"))
      (node (ref "PST3") (pin "1") (pinfunction "P$1_1") (pintype "bidirectional"))
    )
    (net (code "199") (name "Net-(IC4-P4.5-A21-CAN1_RXD-CAN2_RXD)") (class "Default")
      (node (ref "IC4") (pin "90") (pinfunction "P4.5-A21-CAN1_RXD-CAN2_RXD_90") (pintype "bidirectional"))
      (node (ref "PST4") (pin "1") (pinfunction "P$1_1") (pintype "bidirectional"))
    )
    (net (code "200") (name "Net-(IC4-P4.6-A22-CAN1_TXD-CAN2_TXD)") (class "Default")
      (node (ref "IC4") (pin "91") (pinfunction "P4.6-A22-CAN1_TXD-CAN2_TXD_91") (pintype "bidirectional"))
      (node (ref "PST6") (pin "1") (pinfunction "P$1_1") (pintype "bidirectional"))
    )
    (net (code "201") (name "Net-(IC4-P7.4-CC28IO)") (class "Default")
      (node (ref "IC4") (pin "23") (pinfunction "P7.4-CC28IO_23") (pintype "bidirectional"))
      (node (ref "R10") (pin "2") (pinfunction "2_2") (pintype "bidirectional"))
    )
    (net (code "202") (name "Net-(IC4-P8.2-XPOUT2-CC18IO)") (class "Default")
      (node (ref "IC4") (pin "11") (pinfunction "P8.2-XPOUT2-CC18IO_11") (pintype "bidirectional"))
      (node (ref "JP8") (pin "2") (pinfunction "2_2") (pintype "passive"))
      (node (ref "RS6") (pin "4") (pinfunction "4_4") (pintype "bidirectional"))
    )
    (net (code "203") (name "Net-(IC4-P8.3-XPOUT3-CC19IO)") (class "Default")
      (node (ref "IC4") (pin "12") (pinfunction "P8.3-XPOUT3-CC19IO_12") (pintype "bidirectional"))
      (node (ref "JP7") (pin "2") (pinfunction "2_2") (pintype "passive"))
      (node (ref "RS6") (pin "3") (pinfunction "3_3") (pintype "bidirectional"))
    )
    (net (code "204") (name "Net-(IC4-RPD)") (class "Default")
      (node (ref "C8") (pin "+") (pinfunction "+_+") (pintype "passive"))
      (node (ref "IC4") (pin "84") (pinfunction "RPD_84") (pintype "bidirectional"))
      (node (ref "R3") (pin "1") (pinfunction "1_1") (pintype "bidirectional"))
    )
    (net (code "205") (name "Net-(IC4-RSTOUT{slash})") (class "Default")
      (node (ref "IC4") (pin "141") (pinfunction "RSTOUT/_141") (pintype "output"))
      (node (ref "PST1") (pin "1") (pinfunction "P$1_1") (pintype "bidirectional"))
    )
    (net (code "206") (name "Net-(IC4-V18)") (class "Default")
      (node (ref "C6") (pin "1") (pinfunction "1_1") (pintype "passive"))
      (node (ref "IC4") (pin "56") (pinfunction "V18_56") (pintype "bidirectional"))
    )
    (net (code "207") (name "Net-(IC4-VAREF)") (class "Default")
      (node (ref "C7") (pin "+") (pinfunction "+_+") (pintype "passive"))
      (node (ref "C9") (pin "2") (pinfunction "2_2") (pintype "passive"))
      (node (ref "IC4") (pin "37") (pinfunction "VAREF_37") (pintype "bidirectional"))
      (node (ref "R45") (pin "1") (pinfunction "1_1") (pintype "bidirectional"))
    )
    (net (code "208") (name "Net-(IC4-XTAL1)") (class "Default")
      (node (ref "C1") (pin "1") (pinfunction "1_1") (pintype "passive"))
      (node (ref "IC4") (pin "138") (pinfunction "XTAL1_138") (pintype "input"))
      (node (ref "Q1") (pin "2") (pinfunction "2_2") (pintype "passive"))
    )
    (net (code "209") (name "Net-(IC4-XTAL2)") (class "Default")
      (node (ref "IC4") (pin "137") (pinfunction "XTAL2_137") (pintype "output"))
      (node (ref "R1") (pin "2") (pinfunction "2_2") (pintype "bidirectional"))
    )
    (net (code "210") (name "Net-(IC6-A)") (class "Default")
      (node (ref "IC6") (pin "2") (pinfunction "A_2") (pintype "input"))
      (node (ref "J6") (pin "11") (pinfunction "11_11") (pintype "bidirectional"))
    )
    (net (code "211") (name "Net-(IC6-VCC)") (class "Default")
      (node (ref "IC6") (pin "5") (pinfunction "VCC_5") (pintype "bidirectional"))
      (node (ref "T16") (pin "D") (pinfunction "D_D") (pintype "passive"))
    )
    (net (code "212") (name "Net-(IC10-XTAL1)") (class "Default")
      (node (ref "IC10") (pin "3") (pinfunction "XTAL1_3") (pintype "bidirectional"))
      (node (ref "Q5") (pin "4") (pinfunction "2_4") (pintype "passive"))
    )
    (net (code "213") (name "Net-(IC10-XTAL2)") (class "Default")
      (node (ref "IC10") (pin "5") (pinfunction "XTAL2_5") (pintype "bidirectional"))
      (node (ref "Q5") (pin "1") (pinfunction "1_1") (pintype "passive"))
    )
    (net (code "214") (name "Net-(IC11A--)") (class "Default")
      (node (ref "C54") (pin "1") (pinfunction "1_1") (pintype "passive"))
      (node (ref "IC11") (pin "2") (pinfunction "-_2") (pintype "input"))
      (node (ref "R57") (pin "2") (pinfunction "2_2") (pintype "bidirectional"))
      (node (ref "R58") (pin "1") (pinfunction "1_1") (pintype "bidirectional"))
    )
    (net (code "215") (name "Net-(IC11B-+)") (class "Default")
      (node (ref "C43") (pin "2") (pinfunction "2_2") (pintype "passive"))
      (node (ref "IC11") (pin "5") (pinfunction "+_5") (pintype "input"))
      (node (ref "R53") (pin "2") (pinfunction "2_2") (pintype "bidirectional"))
      (node (ref "R55") (pin "2") (pinfunction "2_2") (pintype "bidirectional"))
    )
    (net (code "216") (name "Net-(IC11B--)") (class "Default")
      (node (ref "C39") (pin "2") (pinfunction "2_2") (pintype "passive"))
      (node (ref "IC11") (pin "6") (pinfunction "-_6") (pintype "input"))
      (node (ref "R54") (pin "2") (pinfunction "2_2") (pintype "bidirectional"))
      (node (ref "R56") (pin "2") (pinfunction "2_2") (pintype "bidirectional"))
    )
    (net (code "217") (name "Net-(IC13-ALE)") (class "Default")
      (node (ref "IC13") (pin "17") (pinfunction "ALE_17") (pintype "bidirectional"))
      (node (ref "IC2") (pin "32") (pinfunction "2A4_32") (pintype "bidirectional"))
    )
    (net (code "218") (name "Net-(IC13-CE1{slash})") (class "Default")
      (node (ref "IC13") (pin "9") (pinfunction "CE1/_9") (pintype "bidirectional"))
      (node (ref "IC2") (pin "36") (pinfunction "2A1_36") (pintype "bidirectional"))
      (node (ref "IC2") (pin "48") (pinfunction "1OE/_48") (pintype "bidirectional"))
    )
    (net (code "219") (name "Net-(IC13-CLE)") (class "Default")
      (node (ref "IC13") (pin "16") (pinfunction "CLE_16") (pintype "bidirectional"))
      (node (ref "IC2") (pin "30") (pinfunction "2A5_30") (pintype "bidirectional"))
    )
    (net (code "220") (name "Net-(IC13-IO0)") (class "Default")
      (node (ref "IC13") (pin "29") (pinfunction "IO0_29") (pintype "bidirectional"))
      (node (ref "IC2") (pin "47") (pinfunction "1A1_47") (pintype "bidirectional"))
    )
    (net (code "221") (name "Net-(IC13-IO1)") (class "Default")
      (node (ref "IC13") (pin "30") (pinfunction "IO1_30") (pintype "bidirectional"))
      (node (ref "IC2") (pin "46") (pinfunction "1A2_46") (pintype "bidirectional"))
    )
    (net (code "222") (name "Net-(IC13-IO2)") (class "Default")
      (node (ref "IC13") (pin "31") (pinfunction "IO2_31") (pintype "bidirectional"))
      (node (ref "IC2") (pin "44") (pinfunction "1A3_44") (pintype "bidirectional"))
    )
    (net (code "223") (name "Net-(IC13-IO3)") (class "Default")
      (node (ref "IC13") (pin "32") (pinfunction "IO3_32") (pintype "bidirectional"))
      (node (ref "IC2") (pin "43") (pinfunction "1A4_43") (pintype "bidirectional"))
    )
    (net (code "224") (name "Net-(IC13-IO4)") (class "Default")
      (node (ref "IC13") (pin "41") (pinfunction "IO4_41") (pintype "bidirectional"))
      (node (ref "IC2") (pin "41") (pinfunction "1A5_41") (pintype "bidirectional"))
    )
    (net (code "225") (name "Net-(IC13-IO5)") (class "Default")
      (node (ref "IC13") (pin "42") (pinfunction "IO5_42") (pintype "bidirectional"))
      (node (ref "IC2") (pin "40") (pinfunction "1A6_40") (pintype "bidirectional"))
    )
    (net (code "226") (name "Net-(IC13-IO6)") (class "Default")
      (node (ref "IC13") (pin "43") (pinfunction "IO6_43") (pintype "bidirectional"))
      (node (ref "IC2") (pin "38") (pinfunction "1A7_38") (pintype "bidirectional"))
    )
    (net (code "227") (name "Net-(IC13-IO7)") (class "Default")
      (node (ref "IC13") (pin "44") (pinfunction "IO7_44") (pintype "bidirectional"))
      (node (ref "IC2") (pin "37") (pinfunction "1A8_37") (pintype "bidirectional"))
    )
    (net (code "228") (name "Net-(IC13-RE{slash})") (class "Default")
      (node (ref "IC13") (pin "8") (pinfunction "RE/_8") (pintype "bidirectional"))
      (node (ref "IC2") (pin "35") (pinfunction "2A2_35") (pintype "bidirectional"))
    )
    (net (code "229") (name "Net-(IC13-WE{slash})") (class "Default")
      (node (ref "IC13") (pin "18") (pinfunction "WE/_18") (pintype "bidirectional"))
      (node (ref "IC2") (pin "1") (pinfunction "1DIR_1") (pintype "bidirectional"))
      (node (ref "IC2") (pin "33") (pinfunction "2A3_33") (pintype "bidirectional"))
    )
    (net (code "230") (name "Net-(IC14-1CLK)") (class "Default")
      (node (ref "IC14") (pin "25") (pinfunction "2CLK_25") (pintype "bidirectional"))
      (node (ref "IC14") (pin "48") (pinfunction "1CLK_48") (pintype "bidirectional"))
      (node (ref "IC38") (pin "4") (pinfunction "Y_4") (pintype "open_collector"))
    )
    (net (code "231") (name "Net-(IC15-OUT)") (class "Default")
      (node (ref "C61") (pin "2") (pinfunction "2_2") (pintype "passive"))
      (node (ref "IC15") (pin "1") (pinfunction "OUT_1") (pintype "output"))
      (node (ref "R33") (pin "1") (pinfunction "1_1") (pintype "bidirectional"))
    )
    (net (code "232") (name "Net-(IC16-VOUT)") (class "Default")
      (node (ref "C64") (pin "2") (pinfunction "2_2") (pintype "passive"))
      (node (ref "IC16") (pin "2") (pinfunction "VOUT_2") (pintype "bidirectional"))
      (node (ref "JP2") (pin "2") (pinfunction "2_2") (pintype "passive"))
      (node (ref "R34") (pin "1") (pinfunction "1_1") (pintype "bidirectional"))
    )
    (net (code "233") (name "Net-(IC17-OUT)") (class "Default")
      (node (ref "C68") (pin "2") (pinfunction "2_2") (pintype "passive"))
      (node (ref "IC17") (pin "1") (pinfunction "OUT_1") (pintype "output"))
      (node (ref "R37") (pin "1") (pinfunction "1_1") (pintype "bidirectional"))
    )
    (net (code "234") (name "Net-(IC18-VOUT)") (class "Default")
      (node (ref "C71") (pin "2") (pinfunction "2_2") (pintype "passive"))
      (node (ref "IC18") (pin "2") (pinfunction "VOUT_2") (pintype "bidirectional"))
      (node (ref "JP3") (pin "2") (pinfunction "2_2") (pintype "passive"))
      (node (ref "R38") (pin "1") (pinfunction "1_1") (pintype "bidirectional"))
    )
    (net (code "235") (name "Net-(IC19-VOUT)") (class "Default")
      (node (ref "C73") (pin "2") (pinfunction "2_2") (pintype "passive"))
      (node (ref "IC19") (pin "2") (pinfunction "VOUT_2") (pintype "bidirectional"))
      (node (ref "R39") (pin "1") (pinfunction "1_1") (pintype "bidirectional"))
    )
    (net (code "236") (name "Net-(IC20-A)") (class "Default")
      (node (ref "IC20") (pin "2") (pinfunction "A_2") (pintype "input"))
      (node (ref "L35") (pin "2") (pinfunction "2_2") (pintype "bidirectional"))
    )
    (net (code "237") (name "Net-(IC20-VCC)") (class "Default")
      (node (ref "C87") (pin "2") (pinfunction "2_2") (pintype "passive"))
      (node (ref "IC20") (pin "5") (pinfunction "VCC_5") (pintype "bidirectional"))
      (node (ref "L42") (pin "2") (pinfunction "2_2") (pintype "bidirectional"))
      (node (ref "R47") (pin "2") (pinfunction "2_2") (pintype "bidirectional"))
      (node (ref "T16") (pin "G") (pinfunction "G_G") (pintype "passive"))
    )
    (net (code "238") (name "Net-(IC21-IN)") (class "Default")
      (node (ref "IC21") (pin "2") (pinfunction "IN_2") (pintype "bidirectional"))
      (node (ref "R35") (pin "2") (pinfunction "2_2") (pintype "bidirectional"))
      (node (ref "T11") (pin "1") (pinfunction "B_1") (pintype "passive"))
    )
    (net (code "239") (name "Net-(IC22-VOUT)") (class "Default")
      (node (ref "C104") (pin "2") (pinfunction "2_2") (pintype "passive"))
      (node (ref "IC22") (pin "2") (pinfunction "VOUT_2") (pintype "bidirectional"))
      (node (ref "JP4") (pin "2") (pinfunction "2_2") (pintype "passive"))
      (node (ref "R42") (pin "1") (pinfunction "1_1") (pintype "bidirectional"))
    )
    (net (code "240") (name "Net-(IC23-IN)") (class "Default")
      (node (ref "IC23") (pin "2") (pinfunction "IN_2") (pintype "bidirectional"))
      (node (ref "R44") (pin "2") (pinfunction "2_2") (pintype "bidirectional"))
      (node (ref "T12") (pin "1") (pinfunction "B_1") (pintype "passive"))
    )
    (net (code "241") (name "Net-(IC25-VCC)") (class "Default")
      (node (ref "IC25") (pin "3") (pinfunction "VCC_3") (pintype "bidirectional"))
      (node (ref "R66") (pin "2") (pinfunction "2_2") (pintype "bidirectional"))
      (node (ref "R67") (pin "2") (pinfunction "2_2") (pintype "bidirectional"))
    )
    (net (code "242") (name "Net-(IC29-BOOT)") (class "Default")
      (node (ref "C97") (pin "2") (pinfunction "2_2") (pintype "passive"))
      (node (ref "IC29") (pin "1") (pinfunction "BOOT_1") (pintype "bidirectional"))
    )
    (net (code "243") (name "Net-(IC29-VIN)") (class "Default")
      (node (ref "C105") (pin "2") (pinfunction "2_2") (pintype "passive"))
      (node (ref "C117") (pin "+") (pinfunction "+_+") (pintype "passive"))
      (node (ref "C88") (pin "+") (pinfunction "+_+") (pintype "passive"))
      (node (ref "D7") (pin "K") (pinfunction "K_K") (pintype "passive"))
      (node (ref "IC29") (pin "7") (pinfunction "VIN_7") (pintype "bidirectional"))
    )
    (net (code "244") (name "Net-(IC29-VSENSE)") (class "Default")
      (node (ref "IC29") (pin "4") (pinfunction "VSENSE_4") (pintype "bidirectional"))
      (node (ref "R71") (pin "2") (pinfunction "2_2") (pintype "bidirectional"))
      (node (ref "R73") (pin "2") (pinfunction "2_2") (pintype "bidirectional"))
    )
    (net (code "245") (name "Net-(IC31-XI)") (class "Default")
      (node (ref "IC31") (pin "1") (pinfunction "XI_1") (pintype "bidirectional"))
      (node (ref "Q3") (pin "4") (pinfunction "2_4") (pintype "passive"))
    )
    (net (code "246") (name "Net-(IC31-XO)") (class "Default")
      (node (ref "IC31") (pin "2") (pinfunction "XO_2") (pintype "bidirectional"))
      (node (ref "Q3") (pin "1") (pinfunction "1_1") (pintype "passive"))
    )
    (net (code "247") (name "Net-(IC33-VOUT)") (class "Default")
      (node (ref "C96") (pin "2") (pinfunction "2_2") (pintype "passive"))
      (node (ref "IC33") (pin "2") (pinfunction "VOUT_2") (pintype "bidirectional"))
      (node (ref "R51") (pin "1") (pinfunction "1_1") (pintype "bidirectional"))
    )
    (net (code "248") (name "Net-(IC37-RESET{slash})") (class "Default")
      (node (ref "C89") (pin "+") (pinfunction "+_+") (pintype "passive"))
      (node (ref "C98") (pin "1") (pinfunction "1_1") (pintype "passive"))
      (node (ref "IC37") (pin "10") (pinfunction "RESET/_10") (pintype "bidirectional"))
      (node (ref "IC37") (pin "2") (pinfunction "VDD_2") (pintype "bidirectional"))
      (node (ref "T17") (pin "D") (pinfunction "D_D") (pintype "passive"))
    )
    (net (code "249") (name "Net-(IC37-RFINOUT)") (class "Default")
      (node (ref "ANT") (pin "1") (pinfunction "1_1") (pintype "bidirectional"))
      (node (ref "IC37") (pin "21") (pinfunction "RFINOUT_21") (pintype "bidirectional"))
    )
    (net (code "250") (name "Net-(IC38-A)") (class "Default")
      (node (ref "IC38") (pin "2") (pinfunction "A_2") (pintype "input"))
      (node (ref "IC39") (pin "4") (pinfunction "Y_4") (pintype "open_collector"))
    )
    (net (code "251") (name "Net-(IC40-A6)") (class "Default")
      (node (ref "IC40") (pin "8") (pinfunction "A6_8") (pintype "bidirectional"))
      (node (ref "IC44") (pin "1") (pinfunction "A_1") (pintype "bidirectional"))
    )
    (net (code "252") (name "Net-(IC40-OE{slash})") (class "Default")
      (node (ref "IC40") (pin "19") (pinfunction "OE/_19") (pintype "bidirectional"))
      (node (ref "IC41") (pin "4") (pinfunction "Y_4") (pintype "open_collector"))
    )
    (net (code "253") (name "Net-(IC43-Y)") (class "Default")
      (node (ref "C112") (pin "2") (pinfunction "2_2") (pintype "passive"))
      (node (ref "IC43") (pin "4") (pinfunction "Y_4") (pintype "open_collector"))
    )
    (net (code "254") (name "Net-(J1-Pad4B)") (class "Default")
      (node (ref "J1") (pin "4B") (pinfunction "4B_4B") (pintype "bidirectional"))
      (node (ref "R31") (pin "1") (pinfunction "1_1") (pintype "bidirectional"))
    )
    (net (code "255") (name "Net-(J1-Pad6B)") (class "Default")
      (node (ref "J1") (pin "6B") (pinfunction "6B_6B") (pintype "bidirectional"))
      (node (ref "R22") (pin "1") (pinfunction "1_1") (pintype "bidirectional"))
    )
    (net (code "256") (name "Net-(J1-Pad9B)") (class "Default")
      (node (ref "J1") (pin "9B") (pinfunction "9B_9B") (pintype "bidirectional"))
      (node (ref "R27") (pin "1") (pinfunction "1_1") (pintype "bidirectional"))
    )
    (net (code "257") (name "Net-(J1-Pad10B)") (class "Default")
      (node (ref "J1") (pin "10B") (pinfunction "10B_10B") (pintype "bidirectional"))
      (node (ref "R13") (pin "1") (pinfunction "1_1") (pintype "bidirectional"))
    )
    (net (code "258") (name "Net-(J1-Pad12B)") (class "Default")
      (node (ref "J1") (pin "12B") (pinfunction "12B_12B") (pintype "bidirectional"))
      (node (ref "R16") (pin "1") (pinfunction "1_1") (pintype "bidirectional"))
    )
    (net (code "259") (name "Net-(J1-Pad13B)") (class "Default")
      (node (ref "J1") (pin "13B") (pinfunction "13B_13B") (pintype "bidirectional"))
      (node (ref "R25") (pin "1") (pinfunction "1_1") (pintype "bidirectional"))
    )
    (net (code "260") (name "Net-(J1-Pad15B)") (class "Default")
      (node (ref "J1") (pin "15B") (pinfunction "15B_15B") (pintype "bidirectional"))
      (node (ref "R23") (pin "1") (pinfunction "1_1") (pintype "bidirectional"))
    )
    (net (code "261") (name "Net-(J6-Pad2)") (class "Default")
      (node (ref "J6") (pin "2") (pinfunction "2_2") (pintype "bidirectional"))
      (node (ref "L36") (pin "2") (pinfunction "2_2") (pintype "bidirectional"))
    )
    (net (code "262") (name "Net-(J6-Pad4)") (class "Default")
      (node (ref "J6") (pin "4") (pinfunction "4_4") (pintype "bidirectional"))
      (node (ref "L38") (pin "2") (pinfunction "2_2") (pintype "bidirectional"))
    )
    (net (code "263") (name "Net-(J6-Pad5)") (class "Default")
      (node (ref "J6") (pin "5") (pinfunction "5_5") (pintype "bidirectional"))
      (node (ref "L39") (pin "2") (pinfunction "2_2") (pintype "bidirectional"))
    )
    (net (code "264") (name "Net-(J6-Pad6)") (class "Default")
      (node (ref "J6") (pin "6") (pinfunction "6_6") (pintype "bidirectional"))
      (node (ref "L40") (pin "2") (pinfunction "2_2") (pintype "bidirectional"))
    )
    (net (code "265") (name "Net-(J6-Pad7)") (class "Default")
      (node (ref "J6") (pin "7") (pinfunction "7_7") (pintype "bidirectional"))
      (node (ref "L41") (pin "2") (pinfunction "2_2") (pintype "bidirectional"))
    )
    (net (code "266") (name "Net-(J6-Pad9)") (class "Default")
      (node (ref "J6") (pin "9") (pinfunction "9_9") (pintype "bidirectional"))
      (node (ref "R30") (pin "2") (pinfunction "2_2") (pintype "bidirectional"))
    )
    (net (code "267") (name "Net-(L14-Pad2)") (class "Default")
      (node (ref "L14") (pin "2") (pinfunction "2_2") (pintype "bidirectional"))
      (node (ref "R69") (pin "1") (pinfunction "1_1") (pintype "bidirectional"))
    )
    (net (code "268") (name "Net-(L28-Pad2)") (class "Default")
      (node (ref "L28") (pin "2") (pinfunction "2_2") (pintype "bidirectional"))
      (node (ref "R49") (pin "1") (pinfunction "1_1") (pintype "bidirectional"))
    )
    (net (code "269") (name "Net-(R13-Pad2)") (class "Default")
      (node (ref "R13") (pin "2") (pinfunction "2_2") (pintype "bidirectional"))
      (node (ref "T5") (pin "D") (pinfunction "D_D") (pintype "passive"))
    )
    (net (code "270") (name "Net-(R16-Pad2)") (class "Default")
      (node (ref "R16") (pin "2") (pinfunction "2_2") (pintype "bidirectional"))
      (node (ref "T9") (pin "D") (pinfunction "D_D") (pintype "passive"))
    )
    (net (code "271") (name "Net-(R22-Pad2)") (class "Default")
      (node (ref "R22") (pin "2") (pinfunction "2_2") (pintype "bidirectional"))
      (node (ref "T1") (pin "D") (pinfunction "D_D") (pintype "passive"))
    )
    (net (code "272") (name "Net-(R23-Pad2)") (class "Default")
      (node (ref "R23") (pin "2") (pinfunction "2_2") (pintype "bidirectional"))
      (node (ref "T2") (pin "D") (pinfunction "D_D") (pintype "passive"))
    )
    (net (code "273") (name "Net-(R25-Pad2)") (class "Default")
      (node (ref "R25") (pin "2") (pinfunction "2_2") (pintype "bidirectional"))
      (node (ref "T4") (pin "D") (pinfunction "D_D") (pintype "passive"))
    )
    (net (code "274") (name "Net-(R27-Pad2)") (class "Default")
      (node (ref "R27") (pin "2") (pinfunction "2_2") (pintype "bidirectional"))
      (node (ref "T8") (pin "D") (pinfunction "D_D") (pintype "passive"))
    )
    (net (code "275") (name "Net-(RL1B-L)") (class "Default")
      (node (ref "L20") (pin "2") (pinfunction "2_2") (pintype "bidirectional"))
      (node (ref "RL1") (pin "3") (pinfunction "L_3") (pintype "passive"))
    )
    (net (code "276") (name "Net-(RL1B-R)") (class "Default")
      (node (ref "L19") (pin "2") (pinfunction "2_2") (pintype "bidirectional"))
      (node (ref "RL1") (pin "2") (pinfunction "R_2") (pintype "passive"))
    )
    (net (code "277") (name "Net-(RL1B-T)") (class "Default")
      (node (ref "L11") (pin "2") (pinfunction "2_2") (pintype "bidirectional"))
      (node (ref "RL1") (pin "4") (pinfunction "T_4") (pintype "passive"))
    )
    (net (code "278") (name "Net-(RS3-Pad1)") (class "Default")
      (node (ref "RS3") (pin "1") (pinfunction "1_1") (pintype "bidirectional"))
      (node (ref "T6") (pin "D") (pinfunction "D_D") (pintype "passive"))
    )
    (net (code "279") (name "Net-(T10-B)") (class "Default")
      (node (ref "R41") (pin "2") (pinfunction "2_2") (pintype "bidirectional"))
      (node (ref "T10") (pin "1") (pinfunction "B_1") (pintype "passive"))
    )
    (net (code "280") (name "Net-(T10-C)") (class "Default")
      (node (ref "C47") (pin "2") (pinfunction "2_2") (pintype "passive"))
      (node (ref "JP9") (pin "2") (pinfunction "2_2") (pintype "passive"))
      (node (ref "L30") (pin "1") (pinfunction "1_1") (pintype "bidirectional"))
      (node (ref "T10") (pin "2") (pinfunction "C_2") (pintype "passive"))
      (node (ref "T10") (pin "4") (pinfunction "C2_4") (pintype "passive"))
    )
    (net (code "281") (name "Net-(T10-E)") (class "Default")
      (node (ref "FU2") (pin "2") (pinfunction "2_2") (pintype "bidirectional"))
      (node (ref "T10") (pin "3") (pinfunction "E_3") (pintype "passive"))
    )
    (net (code "282") (name "Net-(T14-DRAIN)") (class "Default")
      (node (ref "BUZ1") (pin "-") (pinfunction "-_-") (pintype "passive"))
      (node (ref "T14") (pin "D") (pinfunction "DRAIN_D") (pintype "passive"))
    )
    (net (code "283") (name "Net-(T14-GATE)") (class "Default")
      (node (ref "D14") (pin "3") (pinfunction "3_3") (pintype "passive"))
      (node (ref "R65") (pin "2") (pinfunction "2_2") (pintype "bidirectional"))
      (node (ref "T14") (pin "G") (pinfunction "GATE_G") (pintype "passive"))
    )
    (net (code "284") (name "Net-(T21-SOURCE)") (class "Default")
      (node (ref "R52") (pin "2") (pinfunction "2_2") (pintype "bidirectional"))
      (node (ref "R53") (pin "1") (pinfunction "1_1") (pintype "bidirectional"))
      (node (ref "T21") (pin "S") (pinfunction "SOURCE_S") (pintype "passive"))
    )
    (net (code "285") (name "O2-VALVE") (class "Default")
      (node (ref "D15") (pin "A") (pinfunction "A_A") (pintype "passive"))
      (node (ref "L25") (pin "2") (pinfunction "2_2") (pintype "bidirectional"))
      (node (ref "T20") (pin "D") (pinfunction "DRAIN_D") (pintype "passive"))
    )
    (net (code "286") (name "PFI") (class "Default")
      (node (ref "C49") (pin "2") (pinfunction "2_2") (pintype "passive"))
      (node (ref "D2") (pin "3") (pinfunction "1_3") (pintype "bidirectional"))
      (node (ref "IC12") (pin "4") (pinfunction "PFI_4") (pintype "bidirectional"))
      (node (ref "IC4") (pin "31") (pinfunction "P5.4-AN4_31") (pintype "bidirectional"))
      (node (ref "R17") (pin "1") (pinfunction "1_1") (pintype "bidirectional"))
      (node (ref "R18") (pin "2") (pinfunction "2_2") (pintype "bidirectional"))
      (node (ref "R19") (pin "1") (pinfunction "1_1") (pintype "bidirectional"))
    )
    (net (code "287") (name "PHOTO-DIODE-BIAS") (class "Default")
      (node (ref "C17") (pin "7") (pinfunction "7_7") (pintype "passive"))
      (node (ref "J3") (pin "4") (pinfunction "4_4") (pintype "bidirectional"))
      (node (ref "L38") (pin "1") (pinfunction "1_1") (pintype "bidirectional"))
    )
    (net (code "288") (name "PHOTO-DIODE-SIGNAL") (class "Default")
      (node (ref "C17") (pin "8") (pinfunction "8_8") (pintype "passive"))
      (node (ref "J3") (pin "2") (pinfunction "2_2") (pintype "bidirectional"))
      (node (ref "L36") (pin "1") (pinfunction "1_1") (pintype "bidirectional"))
    )
    (net (code "289") (name "POWER-FAIL") (class "Default")
      (node (ref "IC12") (pin "5") (pinfunction "PFO_5") (pintype "bidirectional"))
      (node (ref "IC4") (pin "142") (pinfunction "NMI/_142") (pintype "input"))
      (node (ref "R19") (pin "2") (pinfunction "2_2") (pintype "bidirectional"))
      (node (ref "R28") (pin "1") (pinfunction "1_1") (pintype "bidirectional"))
    )
    (net (code "290") (name "PRES-ABS") (class "Default")
      (node (ref "C95") (pin "2") (pinfunction "2_2") (pintype "passive"))
      (node (ref "D3") (pin "1") (pinfunction "3_1") (pintype "bidirectional"))
      (node (ref "IC4") (pin "36") (pinfunction "P5.9-AN9_36") (pintype "bidirectional"))
      (node (ref "R51") (pin "2") (pinfunction "2_2") (pintype "bidirectional"))
    )
    (net (code "291") (name "PRES-INT") (class "Default")
      (node (ref "C63") (pin "2") (pinfunction "2_2") (pintype "passive"))
      (node (ref "D1") (pin "3") (pinfunction "1_3") (pintype "bidirectional"))
      (node (ref "IC4") (pin "27") (pinfunction "P5.0-AN0_27") (pintype "bidirectional"))
      (node (ref "R34") (pin "2") (pinfunction "2_2") (pintype "bidirectional"))
    )
    (net (code "292") (name "PRES-O2") (class "Default")
      (node (ref "C72") (pin "2") (pinfunction "2_2") (pintype "passive"))
      (node (ref "D1") (pin "5") (pinfunction "5_5") (pintype "bidirectional"))
      (node (ref "IC4") (pin "30") (pinfunction "P5.3-AN3_30") (pintype "bidirectional"))
      (node (ref "R39") (pin "2") (pinfunction "2_2") (pintype "bidirectional"))
    )
    (net (code "293") (name "PRES-PROX") (class "Default")
      (node (ref "C103") (pin "2") (pinfunction "2_2") (pintype "passive"))
      (node (ref "D3") (pin "3") (pinfunction "1_3") (pintype "bidirectional"))
      (node (ref "IC4") (pin "35") (pinfunction "P5.8-AN8_35") (pintype "bidirectional"))
      (node (ref "R42") (pin "2") (pinfunction "2_2") (pintype "bidirectional"))
    )
    (net (code "294") (name "PROX-PRES-MEAS") (class "Default")
      (node (ref "IC30") (pin "3") (pinfunction "VOUT_3") (pintype "bidirectional"))
      (node (ref "JP4") (pin "1") (pinfunction "1_1") (pintype "passive"))
    )
    (net (code "295") (name "PWM-BUZ") (class "Default")
      (node (ref "IC4") (pin "22") (pinfunction "P7.3-POUT3_22") (pintype "bidirectional"))
      (node (ref "L17") (pin "2") (pinfunction "2_2") (pintype "bidirectional"))
      (node (ref "R10") (pin "1") (pinfunction "1_1") (pintype "bidirectional"))
    )
    (net (code "296") (name "P_VALVE") (class "Default")
      (node (ref "C70") (pin "2") (pinfunction "2_2") (pintype "passive"))
      (node (ref "D2") (pin "4") (pinfunction "4_4") (pintype "bidirectional"))
      (node (ref "IC4") (pin "33") (pinfunction "P5.6-AN6_33") (pintype "bidirectional"))
      (node (ref "R38") (pin "2") (pinfunction "2_2") (pintype "bidirectional"))
    )
    (net (code "297") (name "Q-O2-MEAS") (class "Default")
      (node (ref "C130") (pin "2") (pinfunction "2_2") (pintype "passive"))
      (node (ref "D3") (pin "4") (pinfunction "4_4") (pintype "bidirectional"))
      (node (ref "IC4") (pin "39") (pinfunction "P5.10-AN10-T6EUD_39") (pintype "bidirectional"))
      (node (ref "R49") (pin "2") (pinfunction "2_2") (pintype "bidirectional"))
    )
    (net (code "298") (name "QI-MEAS") (class "Default")
      (node (ref "C60") (pin "2") (pinfunction "2_2") (pintype "passive"))
      (node (ref "D1") (pin "1") (pinfunction "3_1") (pintype "bidirectional"))
      (node (ref "IC4") (pin "28") (pinfunction "P5.1-AN1_28") (pintype "bidirectional"))
      (node (ref "R33") (pin "2") (pinfunction "2_2") (pintype "bidirectional"))
    )
    (net (code "299") (name "RAP-ALAR") (class "Default")
      (node (ref "IC4") (pin "63") (pinfunction "P2.14-CC14IOIO-EX6IN_63") (pintype "bidirectional"))
      (node (ref "R68") (pin "1") (pinfunction "1_1") (pintype "bidirectional"))
      (node (ref "T19") (pin "G") (pinfunction "G_G") (pintype "passive"))
    )
    (net (code "300") (name "RD{slash}") (class "Default")
      (node (ref "IC1") (pin "9") (pinfunction "RD1/_9") (pintype "input"))
      (node (ref "IC2") (pin "14") (pinfunction "2B2_14") (pintype "bidirectional"))
      (node (ref "IC3") (pin "41") (pinfunction "OE/_41") (pintype "bidirectional"))
      (node (ref "IC4") (pin "95") (pinfunction "RD/_95") (pintype "output"))
      (node (ref "IC7") (pin "28") (pinfunction "OE/_28") (pintype "input"))
      (node (ref "J17") (pin "16") (pinfunction "P$16_16") (pintype "bidirectional"))
    )
    (net (code "301") (name "RESET") (class "Default")
      (node (ref "D14") (pin "1") (pinfunction "1_1") (pintype "passive"))
      (node (ref "IC1") (pin "32") (pinfunction "MR_32") (pintype "input"))
      (node (ref "R29") (pin "1") (pinfunction "1_1") (pintype "bidirectional"))
      (node (ref "T3") (pin "D") (pinfunction "D_D") (pintype "passive"))
    )
    (net (code "302") (name "RESET_USB") (class "Default")
      (node (ref "IC4") (pin "70") (pinfunction "P3.5-T4IN_70") (pintype "bidirectional"))
      (node (ref "L45") (pin "2") (pinfunction "2_2") (pintype "bidirectional"))
      (node (ref "RS1") (pin "6") (pinfunction "6_6") (pintype "bidirectional"))
    )
    (net (code "303") (name "RESET{slash}") (class "Default")
      (node (ref "C50") (pin "2") (pinfunction "2_2") (pintype "passive"))
      (node (ref "IC12") (pin "7") (pinfunction "RESET_7") (pintype "bidirectional"))
      (node (ref "IC4") (pin "140") (pinfunction "RSTIN/_140") (pintype "input"))
      (node (ref "IC7") (pin "12") (pinfunction "RESET/_12") (pintype "input"))
      (node (ref "T3") (pin "G") (pinfunction "G_G") (pintype "passive"))
    )
    (net (code "304") (name "RF") (class "Default")
      (node (ref "IC4") (pin "74") (pinfunction "P3.7-T2IN_74") (pintype "bidirectional"))
      (node (ref "R48") (pin "2") (pinfunction "2_2") (pintype "bidirectional"))
      (node (ref "T17") (pin "G") (pinfunction "G_G") (pintype "passive"))
    )
    (net (code "305") (name "RTS_UART_ST") (class "Default")
      (node (ref "IC43") (pin "1") (pinfunction "B_1") (pintype "input"))
      (node (ref "L50") (pin "2") (pinfunction "2_2") (pintype "bidirectional"))
    )
    (net (code "306") (name "RX-AL-RP") (class "Default")
      (node (ref "IC37") (pin "8") (pinfunction "TXD_8") (pintype "bidirectional"))
      (node (ref "IC9") (pin "2") (pinfunction "A_2") (pintype "input"))
      (node (ref "L10") (pin "2") (pinfunction "2_2") (pintype "bidirectional"))
    )
    (net (code "307") (name "RX-UART-ST") (class "Default")
      (node (ref "IC40") (pin "17") (pinfunction "B1_17") (pintype "bidirectional"))
      (node (ref "L16") (pin "1") (pinfunction "1_1") (pintype "bidirectional"))
    )
    (net (code "308") (name "RXD1") (class "Default")
      (node (ref "IC20") (pin "4") (pinfunction "Y_4") (pintype "open_collector"))
      (node (ref "IC4") (pin "15") (pinfunction "P8.6-RXD1-CC22IO_15") (pintype "bidirectional"))
      (node (ref "IC6") (pin "4") (pinfunction "Y_4") (pintype "open_collector"))
      (node (ref "R32") (pin "1") (pinfunction "1_1") (pintype "bidirectional"))
    )
    (net (code "309") (name "RX_UART_ST_E") (class "Default")
      (node (ref "IC4") (pin "78") (pinfunction "P3.11-RXD0_78") (pintype "bidirectional"))
      (node (ref "IC40") (pin "3") (pinfunction "A1_3") (pintype "bidirectional"))
    )
    (net (code "310") (name "SCLK-SPI-0") (class "Default")
      (node (ref "IC10") (pin "14") (pinfunction "SCLK_14") (pintype "bidirectional"))
      (node (ref "IC27") (pin "5") (pinfunction "CLK_5") (pintype "bidirectional"))
      (node (ref "IC28") (pin "5") (pinfunction "CLK_5") (pintype "bidirectional"))
      (node (ref "IC30") (pin "5") (pinfunction "CLK_5") (pintype "bidirectional"))
      (node (ref "IC31") (pin "10") (pinfunction "SCL_10") (pintype "bidirectional"))
      (node (ref "IC32") (pin "6") (pinfunction "SCK_6") (pintype "input"))
      (node (ref "IC34") (pin "5") (pinfunction "CLK_5") (pintype "bidirectional"))
      (node (ref "IC35") (pin "5") (pinfunction "CLK_5") (pintype "bidirectional"))
      (node (ref "IC4") (pin "80") (pinfunction "P3.13-SCLK0_80") (pintype "bidirectional"))
      (node (ref "L6") (pin "1") (pinfunction "1_1") (pintype "bidirectional"))
    )
    (net (code "311") (name "SCLK_SPI_1") (class "Default")
      (node (ref "IC4") (pin "6") (pinfunction "P6.5-HOLD/-SCLK1_6") (pintype "bidirectional"))
      (node (ref "L53") (pin "2") (pinfunction "2_2") (pintype "bidirectional"))
    )
    (net (code "312") (name "SEC-BUZ") (class "Default")
      (node (ref "D14") (pin "2") (pinfunction "2_2") (pintype "bidirectional"))
      (node (ref "IC4") (pin "24") (pinfunction "P7.5-CC29IO_24") (pintype "bidirectional"))
    )
    (net (code "313") (name "SENSOR-TYPE-LINE") (class "Default")
      (node (ref "C17") (pin "6") (pinfunction "6_6") (pintype "passive"))
      (node (ref "J3") (pin "5") (pinfunction "5_5") (pintype "bidirectional"))
      (node (ref "L39") (pin "1") (pinfunction "1_1") (pintype "bidirectional"))
    )
    (net (code "314") (name "SIGNAL-SHIELD") (class "Default")
      (node (ref "J3") (pin "3") (pinfunction "3_3") (pintype "bidirectional"))
      (node (ref "J6") (pin "3") (pinfunction "3_3") (pintype "bidirectional"))
    )
    (net (code "315") (name "SPEED-MEASURE") (class "Default")
      (node (ref "C101") (pin "2") (pinfunction "2_2") (pintype "passive"))
      (node (ref "J4") (pin "6") (pinfunction "6_6") (pintype "bidirectional"))
      (node (ref "L34") (pin "1") (pinfunction "1_1") (pintype "bidirectional"))
    )
    (net (code "316") (name "SPEED-SETPOINT") (class "Default")
      (node (ref "C56") (pin "5") (pinfunction "5_5") (pintype "passive"))
      (node (ref "J4") (pin "5") (pinfunction "5_5") (pintype "bidirectional"))
      (node (ref "L33") (pin "1") (pinfunction "1_1") (pintype "bidirectional"))
    )
    (net (code "317") (name "SPEED_MEASURE") (class "Default")
      (node (ref "IC4") (pin "47") (pinfunction "P2.0-CC0IO_47") (pintype "bidirectional"))
      (node (ref "L34") (pin "2") (pinfunction "2_2") (pintype "bidirectional"))
    )
    (net (code "318") (name "SUPPLY-AL-RP") (class "Default")
      (node (ref "IC8") (pin "5") (pinfunction "VCC_5") (pintype "bidirectional"))
      (node (ref "IC9") (pin "5") (pinfunction "VCC_5") (pintype "bidirectional"))
      (node (ref "JP5") (pin "1") (pinfunction "1_1") (pintype "passive"))
      (node (ref "JP6") (pin "1") (pinfunction "1_1") (pintype "passive"))
      (node (ref "L7") (pin "2") (pinfunction "2_2") (pintype "bidirectional"))
      (node (ref "R6") (pin "2") (pinfunction "2_2") (pintype "bidirectional"))
    )
    (net (code "319") (name "SUPPLY-BUZ") (class "Default")
      (node (ref "D13") (pin "3") (pinfunction "K_3") (pintype "passive"))
      (node (ref "D6") (pin "K") (pinfunction "K_K") (pintype "passive"))
      (node (ref "L13") (pin "2") (pinfunction "2_2") (pintype "bidirectional"))
      (node (ref "RL1") (pin "1") (pinfunction "B2+_1") (pintype "passive"))
    )
    (net (code "320") (name "TEST-RAP-ALARM") (class "Default")
      (node (ref "IC4") (pin "61") (pinfunction "P2.12-CC12IOIO-EX4IN_61") (pintype "bidirectional"))
      (node (ref "RL1") (pin "5") (pinfunction "T_5") (pintype "passive"))
      (node (ref "RS7") (pin "6") (pinfunction "6_6") (pintype "bidirectional"))
    )
    (net (code "321") (name "TESTBUZ") (class "Default")
      (node (ref "C51") (pin "1") (pinfunction "1_1") (pintype "passive"))
      (node (ref "C93") (pin "2") (pinfunction "2_2") (pintype "passive"))
      (node (ref "D1") (pin "4") (pinfunction "4_4") (pintype "bidirectional"))
      (node (ref "IC4") (pin "29") (pinfunction "P5.2-AN2_29") (pintype "bidirectional"))
      (node (ref "R62") (pin "2") (pinfunction "2_2") (pintype "bidirectional"))
      (node (ref "R69") (pin "2") (pinfunction "2_2") (pintype "bidirectional"))
      (node (ref "R70") (pin "2") (pinfunction "2_2") (pintype "bidirectional"))
    )
    (net (code "322") (name "TURBINE-TEMP") (class "Default")
      (node (ref "C11") (pin "2") (pinfunction "2_2") (pintype "passive"))
      (node (ref "D5") (pin "5") (pinfunction "5_5") (pintype "bidirectional"))
      (node (ref "IC4") (pin "44") (pinfunction "P5.15-AN15-T2EUD_44") (pintype "bidirectional"))
      (node (ref "J4") (pin "10") (pinfunction "10_10") (pintype "bidirectional"))
      (node (ref "R11") (pin "1") (pinfunction "1_1") (pintype "bidirectional"))
    )
    (net (code "323") (name "TX-AL-RP") (class "Default")
      (node (ref "IC37") (pin "7") (pinfunction "RXD_7") (pintype "bidirectional"))
      (node (ref "IC8") (pin "4") (pinfunction "Y_4") (pintype "open_collector"))
      (node (ref "L9") (pin "2") (pinfunction "2_2") (pintype "bidirectional"))
      (node (ref "R6") (pin "1") (pinfunction "1_1") (pintype "bidirectional"))
    )
    (net (code "324") (name "TX_UART_ST") (class "Default")
      (node (ref "IC40") (pin "2") (pinfunction "A0_2") (pintype "bidirectional"))
      (node (ref "L49") (pin "2") (pinfunction "2_2") (pintype "bidirectional"))
    )
    (net (code "325") (name "TX_UART_ST_E") (class "Default")
      (node (ref "IC4") (pin "77") (pinfunction "P3.10-TXD0_77") (pintype "bidirectional"))
      (node (ref "IC40") (pin "18") (pinfunction "B0_18") (pintype "bidirectional"))
    )
    (net (code "326") (name "USB-BUSY") (class "Default")
      (node (ref "IC40") (pin "14") (pinfunction "B4_14") (pintype "bidirectional"))
      (node (ref "L3") (pin "1") (pinfunction "1_1") (pintype "bidirectional"))
    )
    (net (code "327") (name "USB_BUSY_E") (class "Default")
      (node (ref "IC4") (pin "59") (pinfunction "P2.10-CC10IOIO-EX2IN_59") (pintype "bidirectional"))
      (node (ref "IC40") (pin "6") (pinfunction "A4_6") (pintype "bidirectional"))
    )
    (net (code "328") (name "V-BATTERY") (class "Default")
      (node (ref "G1") (pin "+") (pinfunction "+_+") (pintype "bidirectional"))
      (node (ref "G1") (pin "PLUS") (pinfunction "PLUS_PLUS") (pintype "bidirectional"))
      (node (ref "IC10") (pin "2") (pinfunction "VBAT_2") (pintype "bidirectional"))
      (node (ref "IC31") (pin "7") (pinfunction "VBAT_7") (pintype "bidirectional"))
    )
    (net (code "329") (name "VALVE-PRES-MEAS") (class "Default")
      (node (ref "IC28") (pin "3") (pinfunction "VOUT_3") (pintype "bidirectional"))
      (node (ref "JP3") (pin "1") (pinfunction "1_1") (pintype "passive"))
    )
    (net (code "330") (name "VBAT") (class "Default")
      (node (ref "L1") (pin "1") (pinfunction "1_1") (pintype "bidirectional"))
      (node (ref "R14") (pin "1") (pinfunction "1_1") (pintype "bidirectional"))
    )
    (net (code "331") (name "WDOG") (class "Default")
      (node (ref "IC12") (pin "6") (pinfunction "WDI_6") (pintype "bidirectional"))
      (node (ref "IC4") (pin "51") (pinfunction "P2.4-CC4IO_51") (pintype "bidirectional"))
    )
    (net (code "332") (name "WR{slash}") (class "Default")
      (node (ref "IC1") (pin "4") (pinfunction "WR1/_4") (pintype "input"))
      (node (ref "IC2") (pin "16") (pinfunction "2B3_16") (pintype "bidirectional"))
      (node (ref "IC3") (pin "17") (pinfunction "WE/_17") (pintype "bidirectional"))
      (node (ref "IC39") (pin "2") (pinfunction "A_2") (pintype "input"))
      (node (ref "IC4") (pin "96") (pinfunction "WR/-WRL/_96") (pintype "output"))
      (node (ref "IC7") (pin "11") (pinfunction "WE/_11") (pintype "input"))
      (node (ref "J17") (pin "19") (pinfunction "P$19_19") (pintype "bidirectional"))
    )
    (net (code "333") (name "unconnected-(C14-Pad7)") (class "Default")
      (node (ref "C14") (pin "7") (pinfunction "7_7") (pintype "passive"))
    )
    (net (code "334") (name "unconnected-(C18-Pad5)") (class "Default")
      (node (ref "C18") (pin "5") (pinfunction "5_5") (pintype "passive"))
    )
    (net (code "335") (name "unconnected-(IC1-DDIS-Pad12)") (class "Default")
      (node (ref "IC1") (pin "12") (pinfunction "DDIS_12") (pintype "output"))
    )
    (net (code "336") (name "unconnected-(IC1-DTR{slash}-Pad28)") (class "Default")
      (node (ref "IC1") (pin "28") (pinfunction "DTR/_28") (pintype "output"))
    )
    (net (code "337") (name "unconnected-(IC1-NC1-Pad60)") (class "Default")
      (node (ref "IC1") (pin "60") (pinfunction "NC1_60") (pintype "no_connect"))
    )
    (net (code "338") (name "unconnected-(IC1-NC2-Pad19)") (class "Default")
      (node (ref "IC1") (pin "19") (pinfunction "NC2_19") (pintype "no_connect"))
    )
    (net (code "339") (name "unconnected-(IC1-NC3-Pad44)") (class "Default")
      (node (ref "IC1") (pin "44") (pinfunction "NC3_44") (pintype "no_connect"))
    )
    (net (code "340") (name "unconnected-(IC1-NC4-Pad47)") (class "Default")
      (node (ref "IC1") (pin "47") (pinfunction "NC4_47") (pintype "no_connect"))
    )
    (net (code "341") (name "unconnected-(IC1-NC5-Pad49)") (class "Default")
      (node (ref "IC1") (pin "49") (pinfunction "NC5_49") (pintype "no_connect"))
    )
    (net (code "342") (name "unconnected-(IC1-NC6-Pad53)") (class "Default")
      (node (ref "IC1") (pin "53") (pinfunction "NC6_53") (pintype "no_connect"))
    )
    (net (code "343") (name "unconnected-(IC1-NC7-Pad27)") (class "Default")
      (node (ref "IC1") (pin "27") (pinfunction "NC7_27") (pintype "no_connect"))
    )
    (net (code "344") (name "unconnected-(IC1-NC8-Pad29)") (class "Default")
      (node (ref "IC1") (pin "29") (pinfunction "NC8_29") (pintype "no_connect"))
    )
    (net (code "345") (name "unconnected-(IC1-NC9-Pad31)") (class "Default")
      (node (ref "IC1") (pin "31") (pinfunction "NC9_31") (pintype "no_connect"))
    )
    (net (code "346") (name "unconnected-(IC1-NC10-Pad34)") (class "Default")
      (node (ref "IC1") (pin "34") (pinfunction "NC10_34") (pintype "no_connect"))
    )
    (net (code "347") (name "unconnected-(IC1-NC11-Pad37)") (class "Default")
      (node (ref "IC1") (pin "37") (pinfunction "NC11_37") (pintype "no_connect"))
    )
    (net (code "348") (name "unconnected-(IC1-NC12-Pad39)") (class "Default")
      (node (ref "IC1") (pin "39") (pinfunction "NC12_39") (pintype "no_connect"))
    )
    (net (code "349") (name "unconnected-(IC1-NC13-Pad56)") (class "Default")
      (node (ref "IC1") (pin "56") (pinfunction "NC13_56") (pintype "no_connect"))
    )
    (net (code "350") (name "unconnected-(IC1-NC14-Pad57)") (class "Default")
      (node (ref "IC1") (pin "57") (pinfunction "NC14_57") (pintype "no_connect"))
    )
    (net (code "351") (name "unconnected-(IC1-NC15-Pad14)") (class "Default")
      (node (ref "IC1") (pin "14") (pinfunction "NC15_14") (pintype "no_connect"))
    )
    (net (code "352") (name "unconnected-(IC1-NC16-Pad3)") (class "Default")
      (node (ref "IC1") (pin "3") (pinfunction "NC16_3") (pintype "no_connect"))
    )
    (net (code "353") (name "unconnected-(IC1-NC17-Pad5)") (class "Default")
      (node (ref "IC1") (pin "5") (pinfunction "NC17_5") (pintype "no_connect"))
    )
    (net (code "354") (name "unconnected-(IC1-NC18-Pad7)") (class "Default")
      (node (ref "IC1") (pin "7") (pinfunction "NC18_7") (pintype "no_connect"))
    )
    (net (code "355") (name "unconnected-(IC1-NC19-Pad11)") (class "Default")
      (node (ref "IC1") (pin "11") (pinfunction "NC19_11") (pintype "no_connect"))
    )
    (net (code "356") (name "unconnected-(IC1-NC20-Pad22)") (class "Default")
      (node (ref "IC1") (pin "22") (pinfunction "NC20_22") (pintype "no_connect"))
    )
    (net (code "357") (name "unconnected-(IC1-NC21-Pad41)") (class "Default")
      (node (ref "IC1") (pin "41") (pinfunction "NC21_41") (pintype "no_connect"))
    )
    (net (code "358") (name "unconnected-(IC1-NC22-Pad63)") (class "Default")
      (node (ref "IC1") (pin "63") (pinfunction "NC22_63") (pintype "no_connect"))
    )
    (net (code "359") (name "unconnected-(IC1-NC23-Pad24)") (class "Default")
      (node (ref "IC1") (pin "24") (pinfunction "NC23_24") (pintype "no_connect"))
    )
    (net (code "360") (name "unconnected-(IC1-NC24-Pad16)") (class "Default")
      (node (ref "IC1") (pin "16") (pinfunction "NC24_16") (pintype "no_connect"))
    )
    (net (code "361") (name "unconnected-(IC1-OUT1{slash}-Pad30)") (class "Default")
      (node (ref "IC1") (pin "30") (pinfunction "OUT1/_30") (pintype "output"))
    )
    (net (code "362") (name "unconnected-(IC1-OUT2{slash}-Pad25)") (class "Default")
      (node (ref "IC1") (pin "25") (pinfunction "OUT2/_25") (pintype "output"))
    )
    (net (code "363") (name "unconnected-(IC1-RTS{slash}-Pad26)") (class "Default")
      (node (ref "IC1") (pin "26") (pinfunction "RTS/_26") (pintype "output"))
    )
    (net (code "364") (name "unconnected-(IC1-RXRDY{slash}-Pad21)") (class "Default")
      (node (ref "IC1") (pin "21") (pinfunction "RXRDY/_21") (pintype "output"))
    )
    (net (code "365") (name "unconnected-(IC1-TXRDY{slash}-Pad13)") (class "Default")
      (node (ref "IC1") (pin "13") (pinfunction "TXRDY/_13") (pintype "output"))
    )
    (net (code "366") (name "unconnected-(IC2-2A6-Pad29)") (class "Default")
      (node (ref "IC2") (pin "29") (pinfunction "2A6_29") (pintype "bidirectional"))
    )
    (net (code "367") (name "unconnected-(IC2-2A7-Pad27)") (class "Default")
      (node (ref "IC2") (pin "27") (pinfunction "2A7_27") (pintype "bidirectional"))
    )
    (net (code "368") (name "unconnected-(IC2-2A8-Pad26)") (class "Default")
      (node (ref "IC2") (pin "26") (pinfunction "2A8_26") (pintype "bidirectional"))
    )
    (net (code "369") (name "unconnected-(IC3-NC-Pad28)") (class "Default")
      (node (ref "IC3") (pin "28") (pinfunction "NC_28") (pintype "no_connect"))
    )
    (net (code "370") (name "unconnected-(IC4-ALE-Pad98)") (class "Default")
      (node (ref "IC4") (pin "98") (pinfunction "ALE_98") (pintype "output"))
    )
    (net (code "371") (name "unconnected-(IC4-P8.1-XPOUT1-CC17IO-Pad10)") (class "Default")
      (node (ref "IC4") (pin "10") (pinfunction "P8.1-XPOUT1-CC17IO_10") (pintype "bidirectional"))
    )
    (net (code "372") (name "unconnected-(IC4-P8.4-CC20IO-Pad13)") (class "Default")
      (node (ref "IC4") (pin "13") (pinfunction "P8.4-CC20IO_13") (pintype "bidirectional"))
    )
    (net (code "373") (name "unconnected-(IC4-P8.7-TXD1-CC23IO-Pad16)") (class "Default")
      (node (ref "IC4") (pin "16") (pinfunction "P8.7-TXD1-CC23IO_16") (pintype "bidirectional"))
    )
    (net (code "374") (name "unconnected-(IC6-NC-Pad1)") (class "Default")
      (node (ref "IC6") (pin "1") (pinfunction "NC_1") (pintype "no_connect"))
    )
    (net (code "375") (name "unconnected-(IC7-NC1-Pad9)") (class "Default")
      (node (ref "IC7") (pin "9") (pinfunction "NC1_9") (pintype "no_connect"))
    )
    (net (code "376") (name "unconnected-(IC7-NC2-Pad10)") (class "Default")
      (node (ref "IC7") (pin "10") (pinfunction "NC2_10") (pintype "no_connect"))
    )
    (net (code "377") (name "unconnected-(IC7-NC3-Pad13)") (class "Default")
      (node (ref "IC7") (pin "13") (pinfunction "NC3_13") (pintype "no_connect"))
    )
    (net (code "378") (name "unconnected-(IC7-NC4-Pad14)") (class "Default")
      (node (ref "IC7") (pin "14") (pinfunction "NC4_14") (pintype "no_connect"))
    )
    (net (code "379") (name "unconnected-(IC8-NC-Pad1)") (class "Default")
      (node (ref "IC8") (pin "1") (pinfunction "NC_1") (pintype "no_connect"))
    )
    (net (code "380") (name "unconnected-(IC9-NC-Pad1)") (class "Default")
      (node (ref "IC9") (pin "1") (pinfunction "NC_1") (pintype "no_connect"))
    )
    (net (code "381") (name "unconnected-(IC10-INT0{slash}-Pad7)") (class "Default")
      (node (ref "IC10") (pin "7") (pinfunction "INT0/_7") (pintype "bidirectional"))
    )
    (net (code "382") (name "unconnected-(IC10-INT1{slash}-Pad9)") (class "Default")
      (node (ref "IC10") (pin "9") (pinfunction "INT1/_9") (pintype "bidirectional"))
    )
    (net (code "383") (name "unconnected-(IC10-NC1-Pad4)") (class "Default")
      (node (ref "IC10") (pin "4") (pinfunction "NC1_4") (pintype "no_connect"))
    )
    (net (code "384") (name "unconnected-(IC10-NC2-Pad6)") (class "Default")
      (node (ref "IC10") (pin "6") (pinfunction "NC2_6") (pintype "no_connect"))
    )
    (net (code "385") (name "unconnected-(IC10-NC3-Pad8)") (class "Default")
      (node (ref "IC10") (pin "8") (pinfunction "NC3_8") (pintype "no_connect"))
    )
    (net (code "386") (name "unconnected-(IC10-NC4-Pad13)") (class "Default")
      (node (ref "IC10") (pin "13") (pinfunction "NC4_13") (pintype "no_connect"))
    )
    (net (code "387") (name "unconnected-(IC10-NC5-Pad19)") (class "Default")
      (node (ref "IC10") (pin "19") (pinfunction "NC5_19") (pintype "no_connect"))
    )
    (net (code "388") (name "unconnected-(IC10-PF{slash}-Pad18)") (class "Default")
      (node (ref "IC10") (pin "18") (pinfunction "PF/_18") (pintype "bidirectional"))
    )
    (net (code "389") (name "unconnected-(IC10-VCC2-Pad1)") (class "Default")
      (node (ref "IC10") (pin "1") (pinfunction "VCC2_1") (pintype "bidirectional"))
    )
    (net (code "390") (name "unconnected-(IC12-VBATT-Pad8)") (class "Default")
      (node (ref "IC12") (pin "8") (pinfunction "VBATT_8") (pintype "bidirectional"))
    )
    (net (code "391") (name "unconnected-(IC12-VOUT-Pad1)") (class "Default")
      (node (ref "IC12") (pin "1") (pinfunction "VOUT_1") (pintype "bidirectional"))
    )
    (net (code "392") (name "unconnected-(IC13-R-B2{slash}-Pad6)") (class "Default")
      (node (ref "IC13") (pin "6") (pinfunction "R-B2/_6") (pintype "bidirectional"))
    )
    (net (code "393") (name "unconnected-(IC13-R-B3{slash}-Pad5)") (class "Default")
      (node (ref "IC13") (pin "5") (pinfunction "R-B3/_5") (pintype "bidirectional"))
    )
    (net (code "394") (name "unconnected-(IC13-R-B4{slash}-Pad4)") (class "Default")
      (node (ref "IC13") (pin "4") (pinfunction "R-B4/_4") (pintype "bidirectional"))
    )
    (net (code "395") (name "unconnected-(IC14-1Q3-Pad5)") (class "Default")
      (node (ref "IC14") (pin "5") (pinfunction "1Q3_5") (pintype "bidirectional"))
    )
    (net (code "396") (name "unconnected-(IC14-2Q7-Pad22)") (class "Default")
      (node (ref "IC14") (pin "22") (pinfunction "2Q7_22") (pintype "bidirectional"))
    )
    (net (code "397") (name "unconnected-(IC14-2Q8-Pad23)") (class "Default")
      (node (ref "IC14") (pin "23") (pinfunction "2Q8_23") (pintype "bidirectional"))
    )
    (net (code "398") (name "unconnected-(IC20-NC-Pad1)") (class "Default")
      (node (ref "IC20") (pin "1") (pinfunction "NC_1") (pintype "no_connect"))
    )
    (net (code "399") (name "unconnected-(IC27-I{slash}C-Pad7)") (class "Default")
      (node (ref "IC27") (pin "7") (pinfunction "I/C_7") (pintype "bidirectional"))
    )
    (net (code "400") (name "unconnected-(IC28-I{slash}C-Pad7)") (class "Default")
      (node (ref "IC28") (pin "7") (pinfunction "I/C_7") (pintype "bidirectional"))
    )
    (net (code "401") (name "unconnected-(IC29-ENA-Pad5)") (class "Default")
      (node (ref "IC29") (pin "5") (pinfunction "ENA_5") (pintype "bidirectional"))
    )
    (net (code "402") (name "unconnected-(IC29-NC-Pad2)") (class "Default")
      (node (ref "IC29") (pin "2") (pinfunction "NC_2") (pintype "bidirectional"))
    )
    (net (code "403") (name "unconnected-(IC29-NC-Pad3)") (class "Default")
      (node (ref "IC29") (pin "3") (pinfunction "NC_3") (pintype "bidirectional"))
    )
    (net (code "404") (name "unconnected-(IC30-I{slash}C-Pad7)") (class "Default")
      (node (ref "IC30") (pin "7") (pinfunction "I/C_7") (pintype "bidirectional"))
    )
    (net (code "405") (name "unconnected-(IC31-IRQ{slash}-Pad14)") (class "Default")
      (node (ref "IC31") (pin "14") (pinfunction "IRQ/_14") (pintype "bidirectional"))
    )
    (net (code "406") (name "unconnected-(IC31-RSTIN1{slash}-Pad5)") (class "Default")
      (node (ref "IC31") (pin "5") (pinfunction "RSTIN1/_5") (pintype "bidirectional"))
    )
    (net (code "407") (name "unconnected-(IC31-RSTIN2{slash}-Pad6)") (class "Default")
      (node (ref "IC31") (pin "6") (pinfunction "RSTIN2/_6") (pintype "bidirectional"))
    )
    (net (code "408") (name "unconnected-(IC31-RST{slash}-Pad3)") (class "Default")
      (node (ref "IC31") (pin "3") (pinfunction "RST/_3") (pintype "bidirectional"))
    )
    (net (code "409") (name "unconnected-(IC31-SQW-Pad11)") (class "Default")
      (node (ref "IC31") (pin "11") (pinfunction "SQW_11") (pintype "bidirectional"))
    )
    (net (code "410") (name "unconnected-(IC31-THS-Pad13)") (class "Default")
      (node (ref "IC31") (pin "13") (pinfunction "THS_13") (pintype "bidirectional"))
    )
    (net (code "411") (name "unconnected-(IC31-WDI-Pad4)") (class "Default")
      (node (ref "IC31") (pin "4") (pinfunction "WDI_4") (pintype "bidirectional"))
    )
    (net (code "412") (name "unconnected-(IC34-I{slash}C-Pad7)") (class "Default")
      (node (ref "IC34") (pin "7") (pinfunction "I/C_7") (pintype "bidirectional"))
    )
    (net (code "413") (name "unconnected-(IC34-VOUT-Pad3)") (class "Default")
      (node (ref "IC34") (pin "3") (pinfunction "VOUT_3") (pintype "bidirectional"))
    )
    (net (code "414") (name "unconnected-(IC35-I{slash}C-Pad7)") (class "Default")
      (node (ref "IC35") (pin "7") (pinfunction "I/C_7") (pintype "bidirectional"))
    )
    (net (code "415") (name "unconnected-(IC35-VOUT-Pad3)") (class "Default")
      (node (ref "IC35") (pin "3") (pinfunction "VOUT_3") (pintype "bidirectional"))
    )
    (net (code "416") (name "unconnected-(IC37-CTS{slash}-Pad4)") (class "Default")
      (node (ref "IC37") (pin "4") (pinfunction "CTS/_4") (pintype "bidirectional"))
    )
    (net (code "417") (name "unconnected-(IC37-GNDRF-Pad23)") (class "Default")
      (node (ref "IC37") (pin "23") (pinfunction "GNDRF_23") (pintype "bidirectional"))
    )
    (net (code "418") (name "unconnected-(IC37-GNDRF-Pad24)") (class "Default")
      (node (ref "IC37") (pin "24") (pinfunction "GNDRF_24") (pintype "bidirectional"))
    )
    (net (code "419") (name "unconnected-(IC37-IO1-Pad16)") (class "Default")
      (node (ref "IC37") (pin "16") (pinfunction "IO1_16") (pintype "bidirectional"))
    )
    (net (code "420") (name "unconnected-(IC37-IO2-Pad13)") (class "Default")
      (node (ref "IC37") (pin "13") (pinfunction "IO2_13") (pintype "bidirectional"))
    )
    (net (code "421") (name "unconnected-(IC37-IO3-Pad14)") (class "Default")
      (node (ref "IC37") (pin "14") (pinfunction "IO3_14") (pintype "bidirectional"))
    )
    (net (code "422") (name "unconnected-(IC37-IO4-Pad11)") (class "Default")
      (node (ref "IC37") (pin "11") (pinfunction "IO4_11") (pintype "bidirectional"))
    )
    (net (code "423") (name "unconnected-(IC37-IO5-Pad12)") (class "Default")
      (node (ref "IC37") (pin "12") (pinfunction "IO5_12") (pintype "bidirectional"))
    )
    (net (code "424") (name "unconnected-(IC37-IO6-Pad9)") (class "Default")
      (node (ref "IC37") (pin "9") (pinfunction "IO6_9") (pintype "bidirectional"))
    )
    (net (code "425") (name "unconnected-(IC37-IO7-Pad6)") (class "Default")
      (node (ref "IC37") (pin "6") (pinfunction "IO7_6") (pintype "bidirectional"))
    )
    (net (code "426") (name "unconnected-(IC37-IO8-Pad15)") (class "Default")
      (node (ref "IC37") (pin "15") (pinfunction "IO8_15") (pintype "bidirectional"))
    )
    (net (code "427") (name "unconnected-(IC37-RFINPOUT-Pad22)") (class "Default")
      (node (ref "IC37") (pin "22") (pinfunction "RFINPOUT_22") (pintype "bidirectional"))
    )
    (net (code "428") (name "unconnected-(IC39-NC-Pad1)") (class "Default")
      (node (ref "IC39") (pin "1") (pinfunction "NC_1") (pintype "no_connect"))
    )
    (net (code "429") (name "unconnected-(IC40-A2-Pad4)") (class "Default")
      (node (ref "IC40") (pin "4") (pinfunction "A2_4") (pintype "bidirectional"))
    )
    (net (code "430") (name "unconnected-(IC40-A7-Pad9)") (class "Default")
      (node (ref "IC40") (pin "9") (pinfunction "A7_9") (pintype "bidirectional"))
    )
    (net (code "431") (name "unconnected-(IC41-NC-Pad1)") (class "Default")
      (node (ref "IC41") (pin "1") (pinfunction "NC_1") (pintype "no_connect"))
    )
    (net (code "432") (name "unconnected-(J1-Pad1)") (class "Default")
      (node (ref "J1") (pin "1") (pinfunction "1_1") (pintype "bidirectional"))
    )
    (net (code "433") (name "unconnected-(J1-Pad2)") (class "Default")
      (node (ref "J1") (pin "2") (pinfunction "2_2") (pintype "bidirectional"))
    )
    (net (code "434") (name "unconnected-(J1-Pad3)") (class "Default")
      (node (ref "J1") (pin "3") (pinfunction "3_3") (pintype "bidirectional"))
    )
    (net (code "435") (name "unconnected-(J1-Pad4)") (class "Default")
      (node (ref "J1") (pin "4") (pinfunction "4_4") (pintype "bidirectional"))
    )
    (net (code "436") (name "unconnected-(J1-Pad5)") (class "Default")
      (node (ref "J1") (pin "5") (pinfunction "5_5") (pintype "bidirectional"))
    )
    (net (code "437") (name "unconnected-(J1-Pad6)") (class "Default")
      (node (ref "J1") (pin "6") (pinfunction "6_6") (pintype "bidirectional"))
    )
    (net (code "438") (name "unconnected-(J1-Pad7)") (class "Default")
      (node (ref "J1") (pin "7") (pinfunction "7_7") (pintype "bidirectional"))
    )
    (net (code "439") (name "unconnected-(J1-Pad8)") (class "Default")
      (node (ref "J1") (pin "8") (pinfunction "8_8") (pintype "bidirectional"))
    )
    (net (code "440") (name "unconnected-(J1-Pad9)") (class "Default")
      (node (ref "J1") (pin "9") (pinfunction "9_9") (pintype "bidirectional"))
    )
    (net (code "441") (name "unconnected-(J1-Pad10)") (class "Default")
      (node (ref "J1") (pin "10") (pinfunction "10_10") (pintype "bidirectional"))
    )
    (net (code "442") (name "unconnected-(J1-Pad11)") (class "Default")
      (node (ref "J1") (pin "11") (pinfunction "11_11") (pintype "bidirectional"))
    )
    (net (code "443") (name "unconnected-(J1-Pad12)") (class "Default")
      (node (ref "J1") (pin "12") (pinfunction "12_12") (pintype "bidirectional"))
    )
    (net (code "444") (name "unconnected-(J1-Pad13)") (class "Default")
      (node (ref "J1") (pin "13") (pinfunction "13_13") (pintype "bidirectional"))
    )
    (net (code "445") (name "unconnected-(J1-Pad14)") (class "Default")
      (node (ref "J1") (pin "14") (pinfunction "14_14") (pintype "bidirectional"))
    )
    (net (code "446") (name "unconnected-(J1-Pad15)") (class "Default")
      (node (ref "J1") (pin "15") (pinfunction "15_15") (pintype "bidirectional"))
    )
    (net (code "447") (name "unconnected-(J1-Pad16)") (class "Default")
      (node (ref "J1") (pin "16") (pinfunction "16_16") (pintype "bidirectional"))
    )
    (net (code "448") (name "unconnected-(J1-Pad16B)") (class "Default")
      (node (ref "J1") (pin "16B") (pinfunction "16B_16B") (pintype "bidirectional"))
    )
    (net (code "449") (name "unconnected-(J1-Pad17)") (class "Default")
      (node (ref "J1") (pin "17") (pinfunction "17_17") (pintype "bidirectional"))
    )
    (net (code "450") (name "unconnected-(J1-Pad18)") (class "Default")
      (node (ref "J1") (pin "18") (pinfunction "18_18") (pintype "bidirectional"))
    )
    (net (code "451") (name "unconnected-(J1-Pad19)") (class "Default")
      (node (ref "J1") (pin "19") (pinfunction "19_19") (pintype "bidirectional"))
    )
    (net (code "452") (name "unconnected-(J1-Pad20)") (class "Default")
      (node (ref "J1") (pin "20") (pinfunction "20_20") (pintype "bidirectional"))
    )
    (net (code "453") (name "unconnected-(J1-Pad21)") (class "Default")
      (node (ref "J1") (pin "21") (pinfunction "21_21") (pintype "bidirectional"))
    )
    (net (code "454") (name "unconnected-(J1-Pad22)") (class "Default")
      (node (ref "J1") (pin "22") (pinfunction "22_22") (pintype "bidirectional"))
    )
    (net (code "455") (name "unconnected-(J2-Pad8)") (class "Default")
      (node (ref "J2") (pin "8") (pinfunction "8_8") (pintype "bidirectional"))
    )
    (net (code "456") (name "unconnected-(J4-Pad7)") (class "Default")
      (node (ref "J4") (pin "7") (pinfunction "7_7") (pintype "bidirectional"))
    )
    (net (code "457") (name "unconnected-(J4-Pad8)") (class "Default")
      (node (ref "J4") (pin "8") (pinfunction "8_8") (pintype "bidirectional"))
    )
    (net (code "458") (name "unconnected-(J6-Pad8)") (class "Default")
      (node (ref "J6") (pin "8") (pinfunction "8_8") (pintype "bidirectional"))
    )
    (net (code "459") (name "unconnected-(J6-Pad10)") (class "Default")
      (node (ref "J6") (pin "10") (pinfunction "10_10") (pintype "bidirectional"))
    )
    (net (code "460") (name "unconnected-(J6-Pad12)") (class "Default")
      (node (ref "J6") (pin "12") (pinfunction "12_12") (pintype "bidirectional"))
    )
    (net (code "461") (name "unconnected-(J6-Pad13)") (class "Default")
      (node (ref "J6") (pin "13") (pinfunction "13_13") (pintype "bidirectional"))
    )
    (net (code "462") (name "unconnected-(J6-Pad14)") (class "Default")
      (node (ref "J6") (pin "14") (pinfunction "14_14") (pintype "bidirectional"))
    )
    (net (code "463") (name "unconnected-(J11-Pad3)") (class "Default")
      (node (ref "J11") (pin "3") (pinfunction "3_3") (pintype "bidirectional"))
    )
    (net (code "464") (name "unconnected-(J17-P$3-Pad3)") (class "Default")
      (node (ref "J17") (pin "3") (pinfunction "P$3_3") (pintype "bidirectional"))
    )
    (net (code "465") (name "unconnected-(J17-P$4-Pad4)") (class "Default")
      (node (ref "J17") (pin "4") (pinfunction "P$4_4") (pintype "bidirectional"))
    )
    (net (code "466") (name "unconnected-(J17-P$24-Pad24)") (class "Default")
      (node (ref "J17") (pin "24") (pinfunction "P$24_24") (pintype "bidirectional"))
    )
    (net (code "467") (name "unconnected-(J17-P$25-Pad25)") (class "Default")
      (node (ref "J17") (pin "25") (pinfunction "P$25_25") (pintype "bidirectional"))
    )
    (net (code "468") (name "unconnected-(J17-P$26-Pad26)") (class "Default")
      (node (ref "J17") (pin "26") (pinfunction "P$26_26") (pintype "bidirectional"))
    )
    (net (code "469") (name "unconnected-(J17-P$27-Pad27)") (class "Default")
      (node (ref "J17") (pin "27") (pinfunction "P$27_27") (pintype "bidirectional"))
    )
    (net (code "470") (name "unconnected-(J17-P$28-Pad28)") (class "Default")
      (node (ref "J17") (pin "28") (pinfunction "P$28_28") (pintype "bidirectional"))
    )
    (net (code "471") (name "unconnected-(J17-P$29-Pad29)") (class "Default")
      (node (ref "J17") (pin "29") (pinfunction "P$29_29") (pintype "bidirectional"))
    )
    (net (code "472") (name "unconnected-(J17-P$30-Pad30)") (class "Default")
      (node (ref "J17") (pin "30") (pinfunction "P$30_30") (pintype "bidirectional"))
    )
    (net (code "473") (name "unconnected-(J17-P$31-Pad31)") (class "Default")
      (node (ref "J17") (pin "31") (pinfunction "P$31_31") (pintype "bidirectional"))
    )
    (net (code "474") (name "unconnected-(J17-P$32-Pad32)") (class "Default")
      (node (ref "J17") (pin "32") (pinfunction "P$32_32") (pintype "bidirectional"))
    )
    (net (code "475") (name "unconnected-(J17-P$33-Pad33)") (class "Default")
      (node (ref "J17") (pin "33") (pinfunction "P$33_33") (pintype "bidirectional"))
    )
    (net (code "476") (name "unconnected-(J17-P$34-Pad34)") (class "Default")
      (node (ref "J17") (pin "34") (pinfunction "P$34_34") (pintype "bidirectional"))
    )
    (net (code "477") (name "unconnected-(J17-P$35-Pad35)") (class "Default")
      (node (ref "J17") (pin "35") (pinfunction "P$35_35") (pintype "bidirectional"))
    )
    (net (code "478") (name "unconnected-(J17-P$36-Pad36)") (class "Default")
      (node (ref "J17") (pin "36") (pinfunction "P$36_36") (pintype "bidirectional"))
    )
    (net (code "479") (name "unconnected-(J17-P$37-Pad37)") (class "Default")
      (node (ref "J17") (pin "37") (pinfunction "P$37_37") (pintype "bidirectional"))
    )
    (net (code "480") (name "unconnected-(J17-P$38-Pad38)") (class "Default")
      (node (ref "J17") (pin "38") (pinfunction "P$38_38") (pintype "bidirectional"))
    )
    (net (code "481") (name "unconnected-(RL1C-R-Pad7)") (class "Default")
      (node (ref "RL1") (pin "7") (pinfunction "R_7") (pintype "passive"))
    )
    (net (code "482") (name "unconnected-(RS6-Pad1)") (class "Default")
      (node (ref "RS6") (pin "1") (pinfunction "1_1") (pintype "bidirectional"))
    )
    (net (code "483") (name "unconnected-(RS6-Pad2)") (class "Default")
      (node (ref "RS6") (pin "2") (pinfunction "2_2") (pintype "bidirectional"))
    )
    (net (code "484") (name "unconnected-(RS7-Pad5)") (class "Default")
      (node (ref "RS7") (pin "5") (pinfunction "5_5") (pintype "bidirectional"))
    )
  )
)
